# FIRSTPRINT.net
KiCad netlist of a schematic drawn in EAGLE
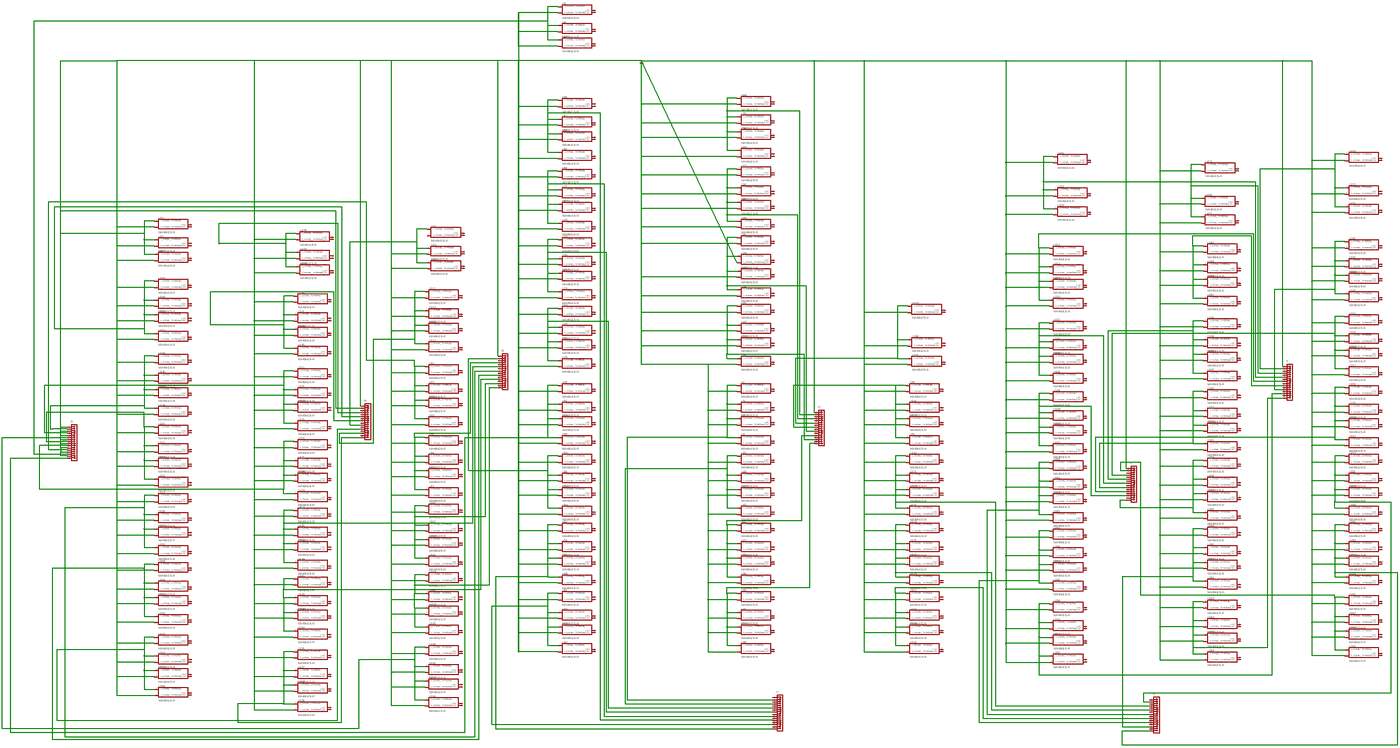
[diagram p0: schematic, sheet 1, overview]
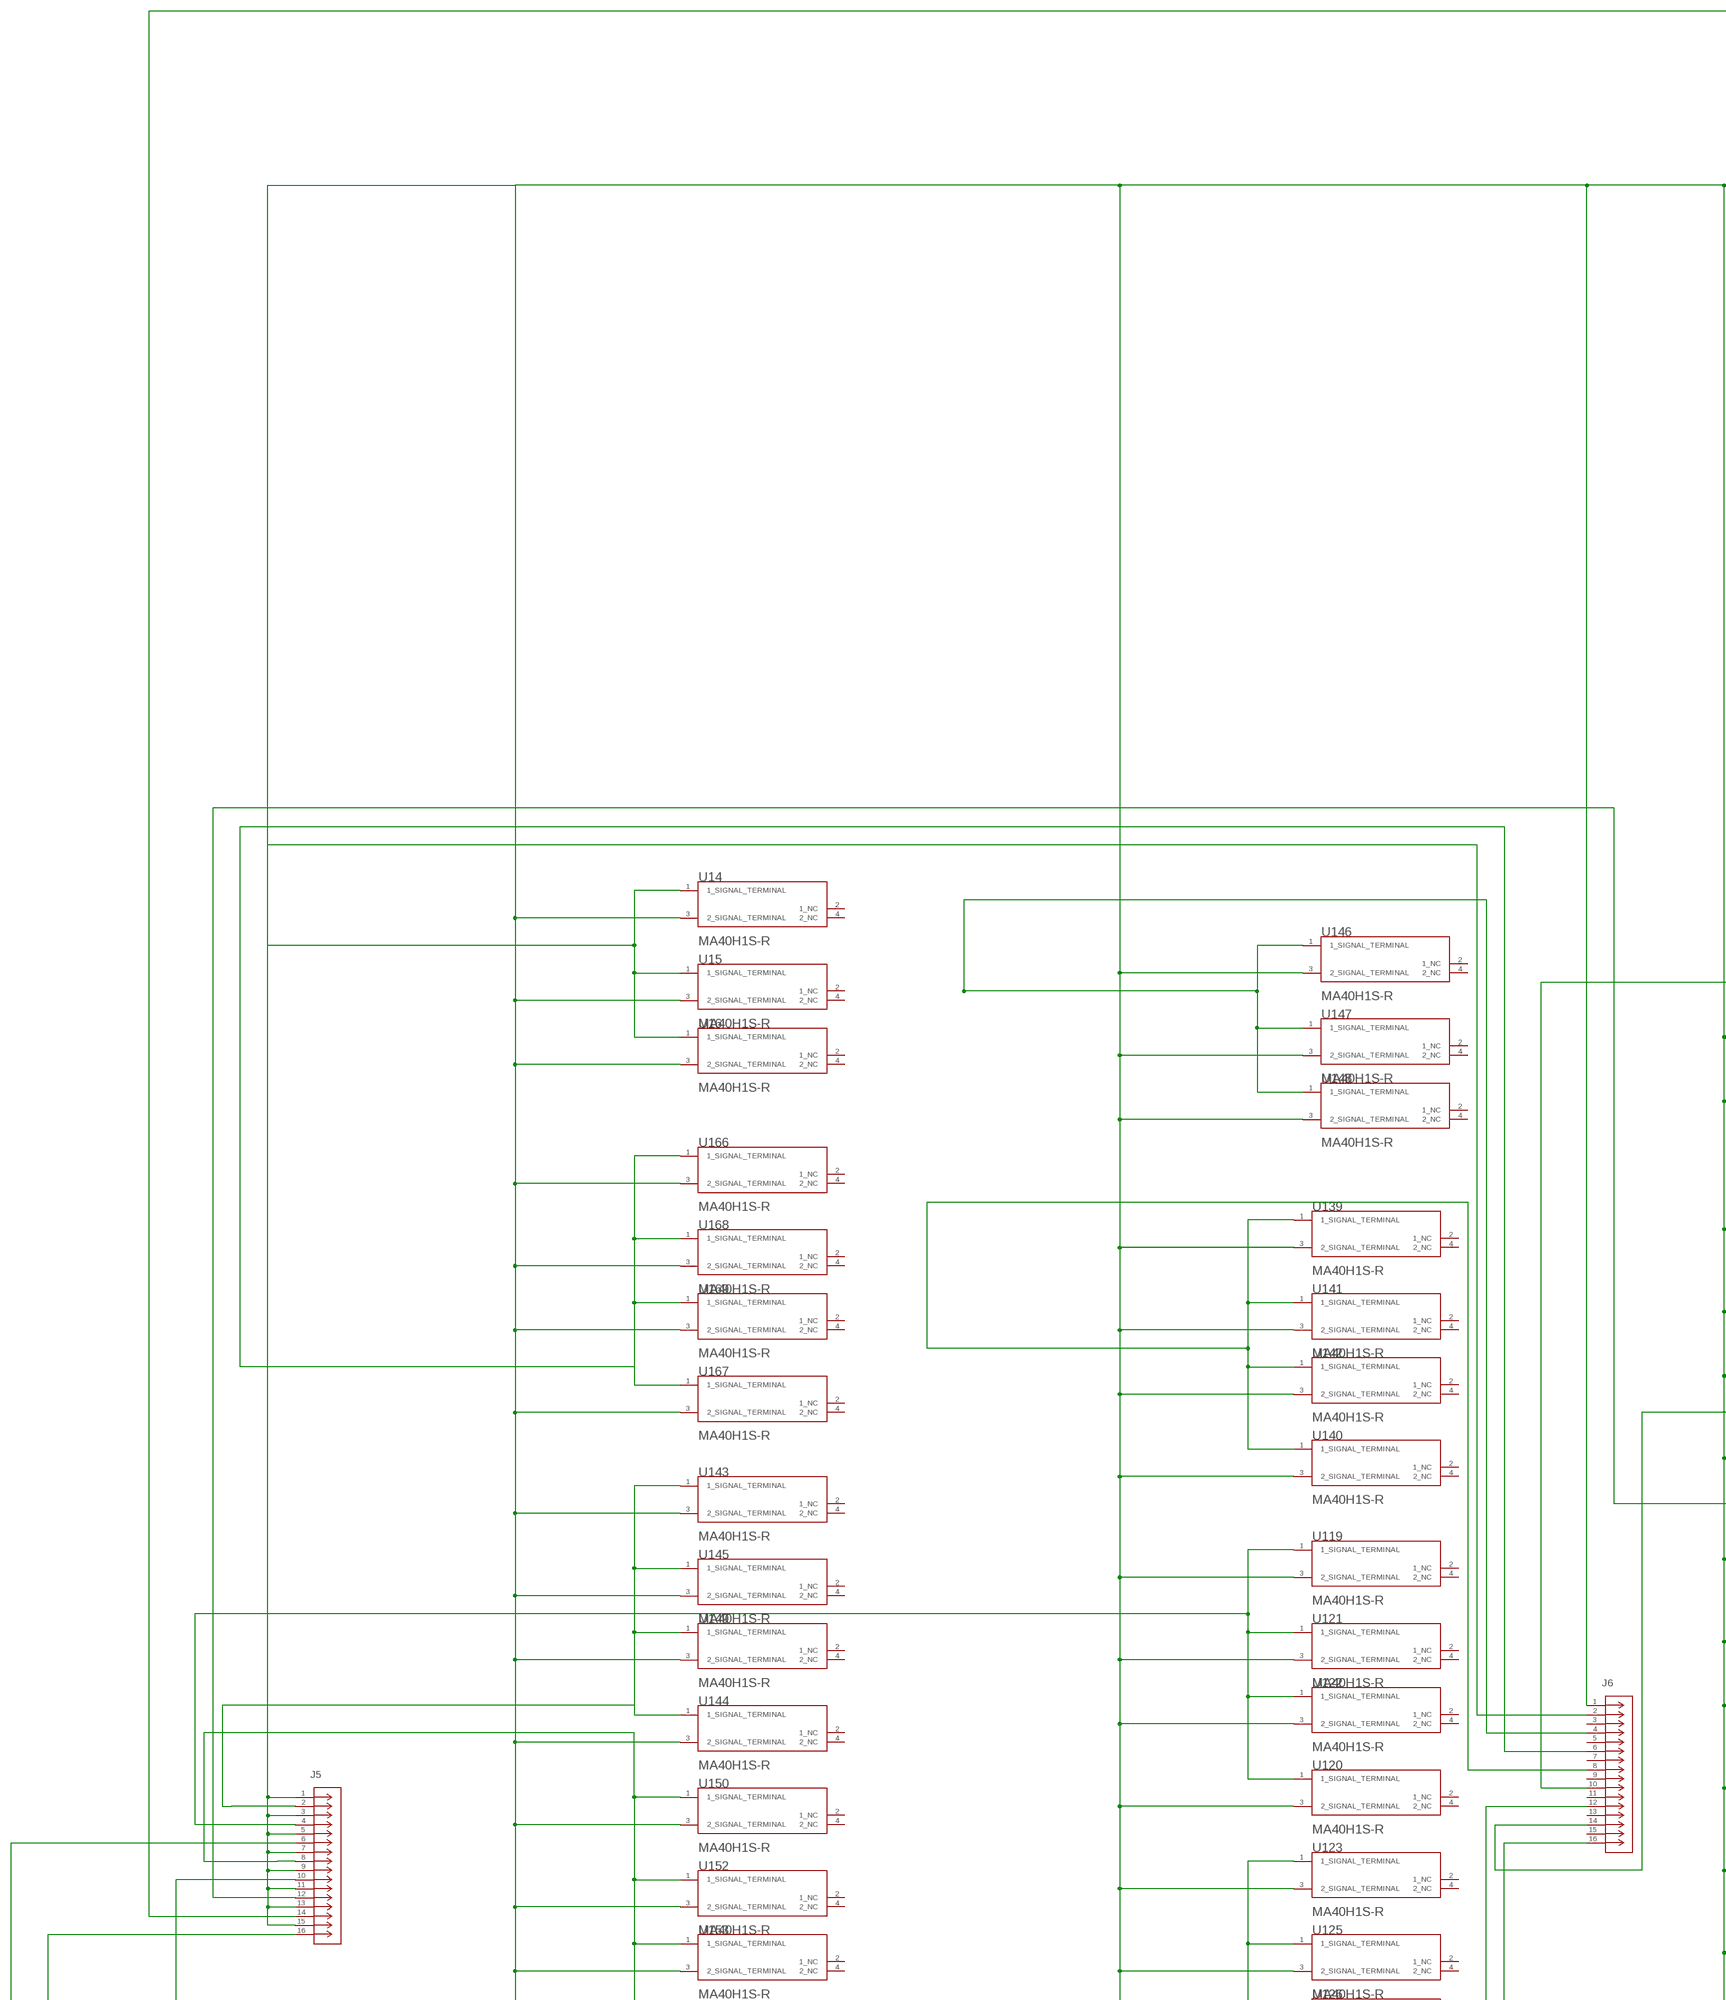
[diagram p1: schematic, sheet 1, part 1 of 8]
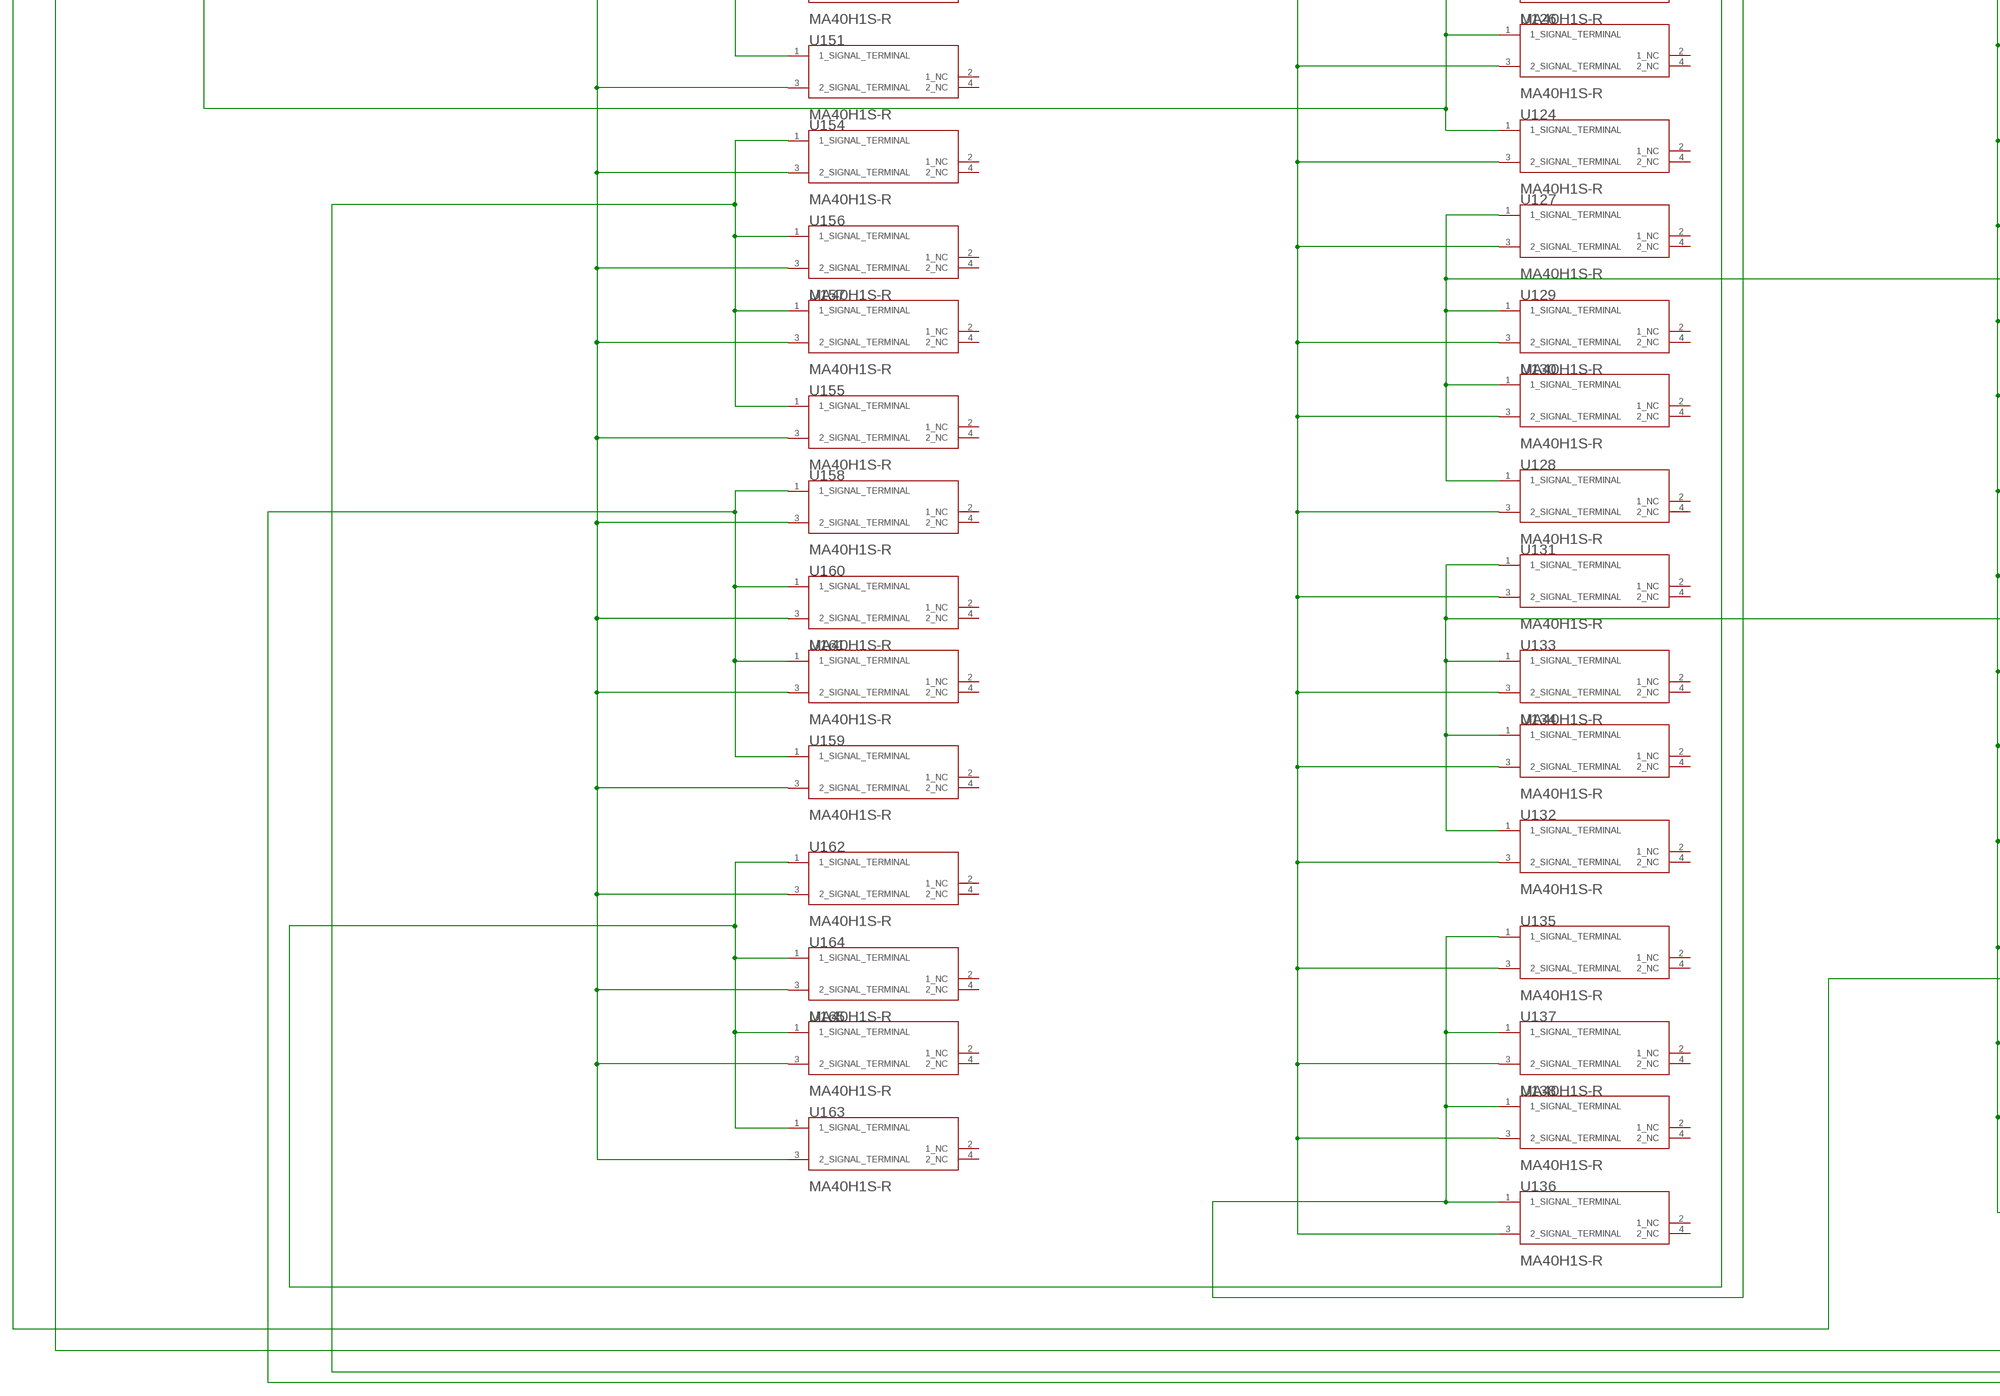
[diagram p2: schematic, sheet 1, part 2 of 8]
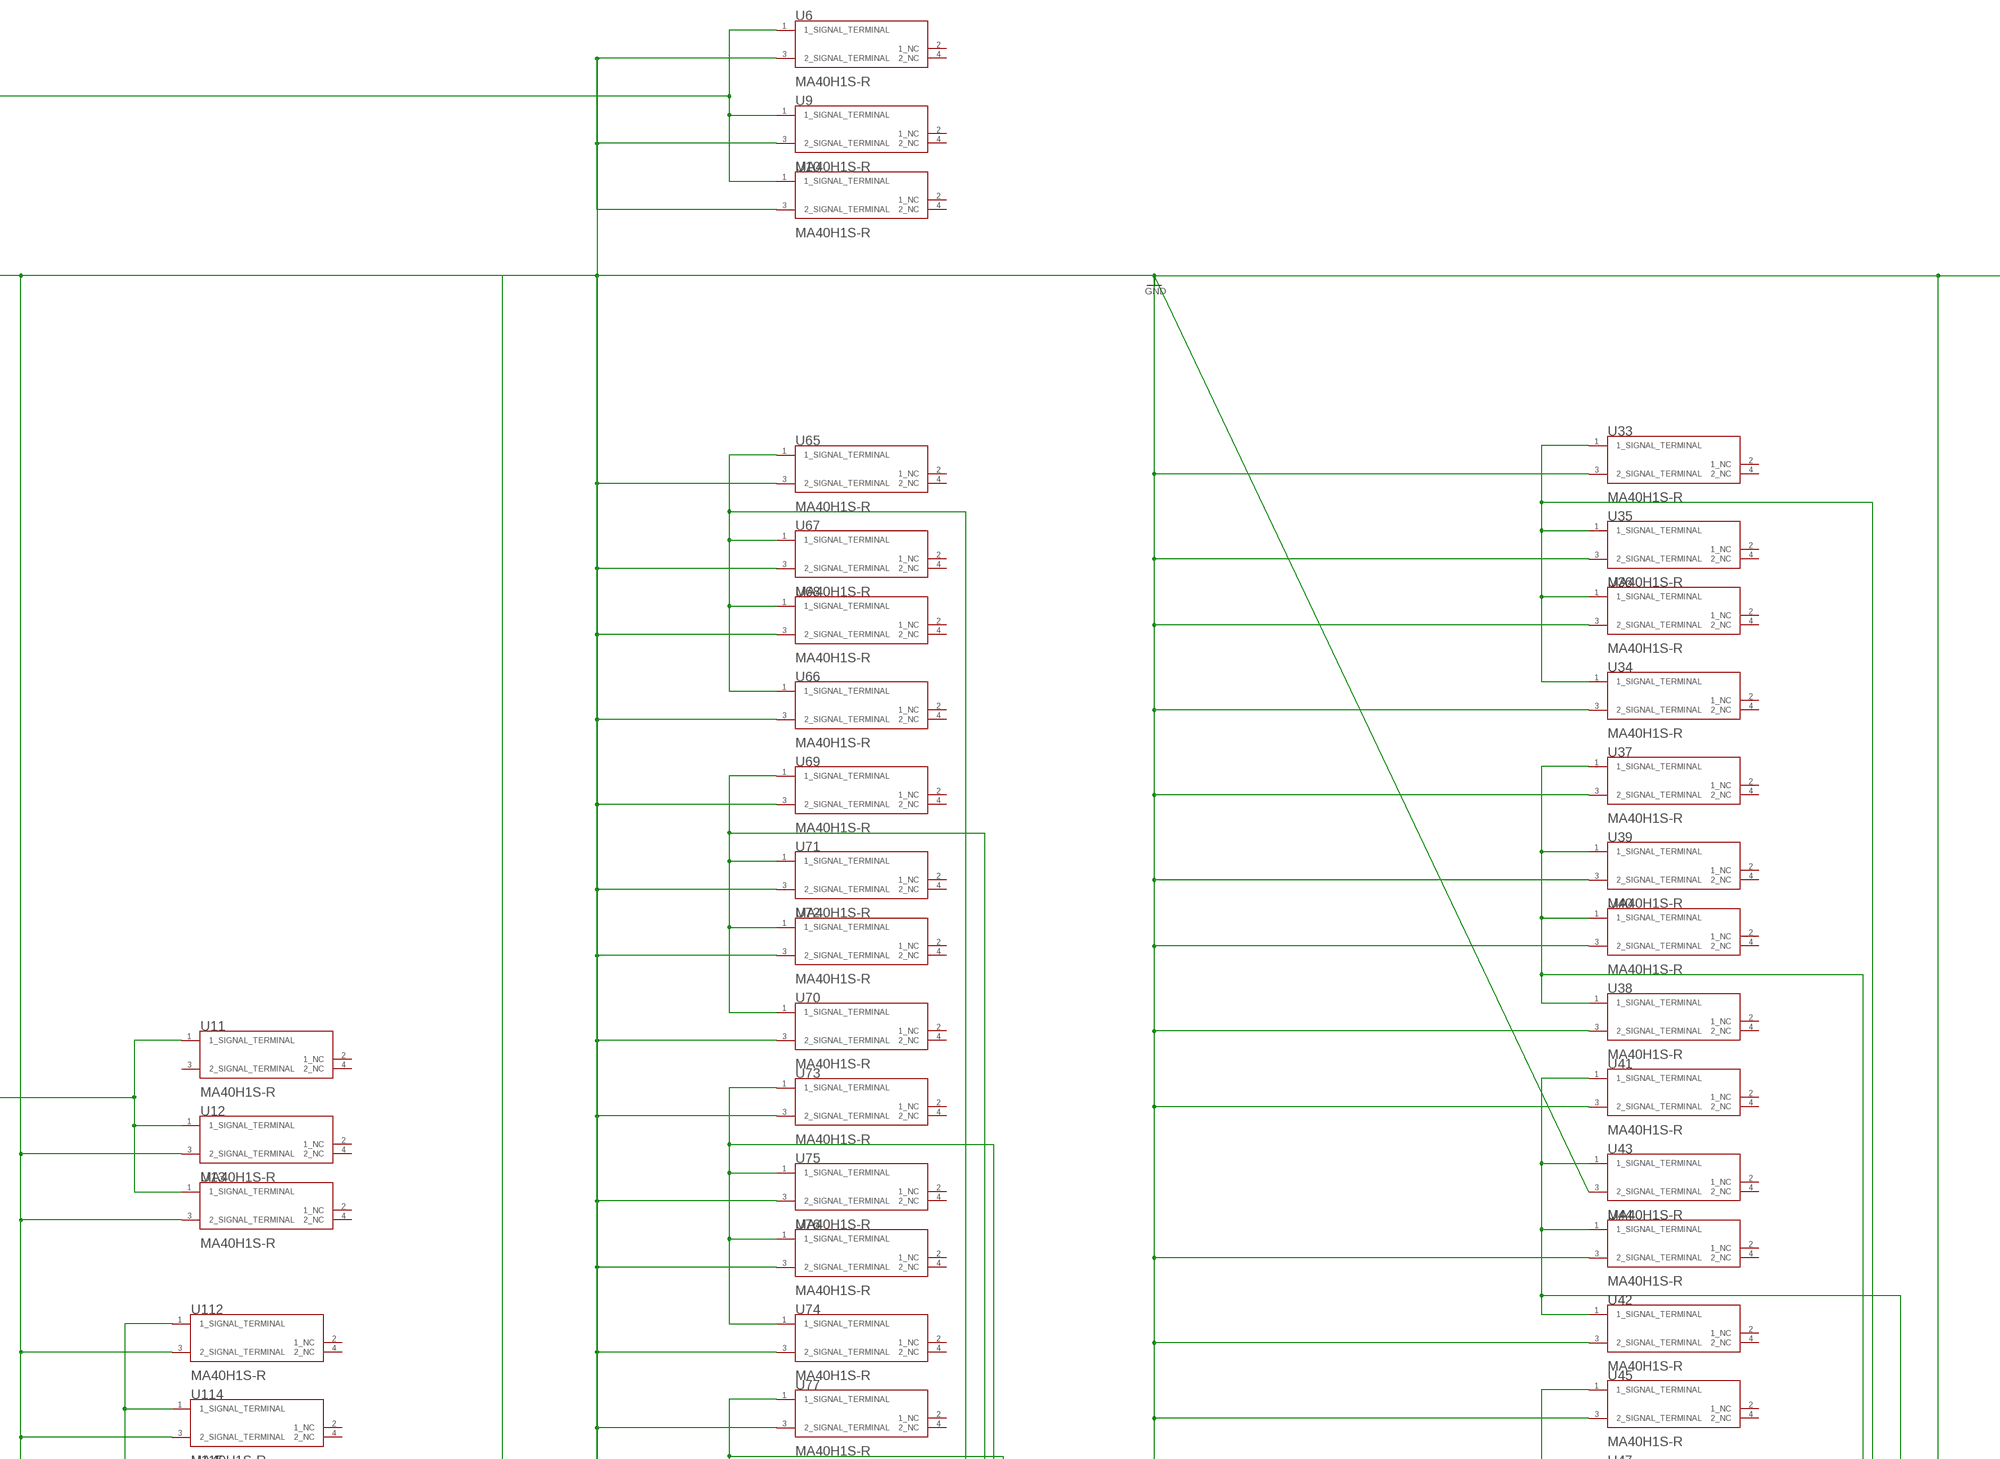
[diagram p3: schematic, sheet 1, part 3 of 8]
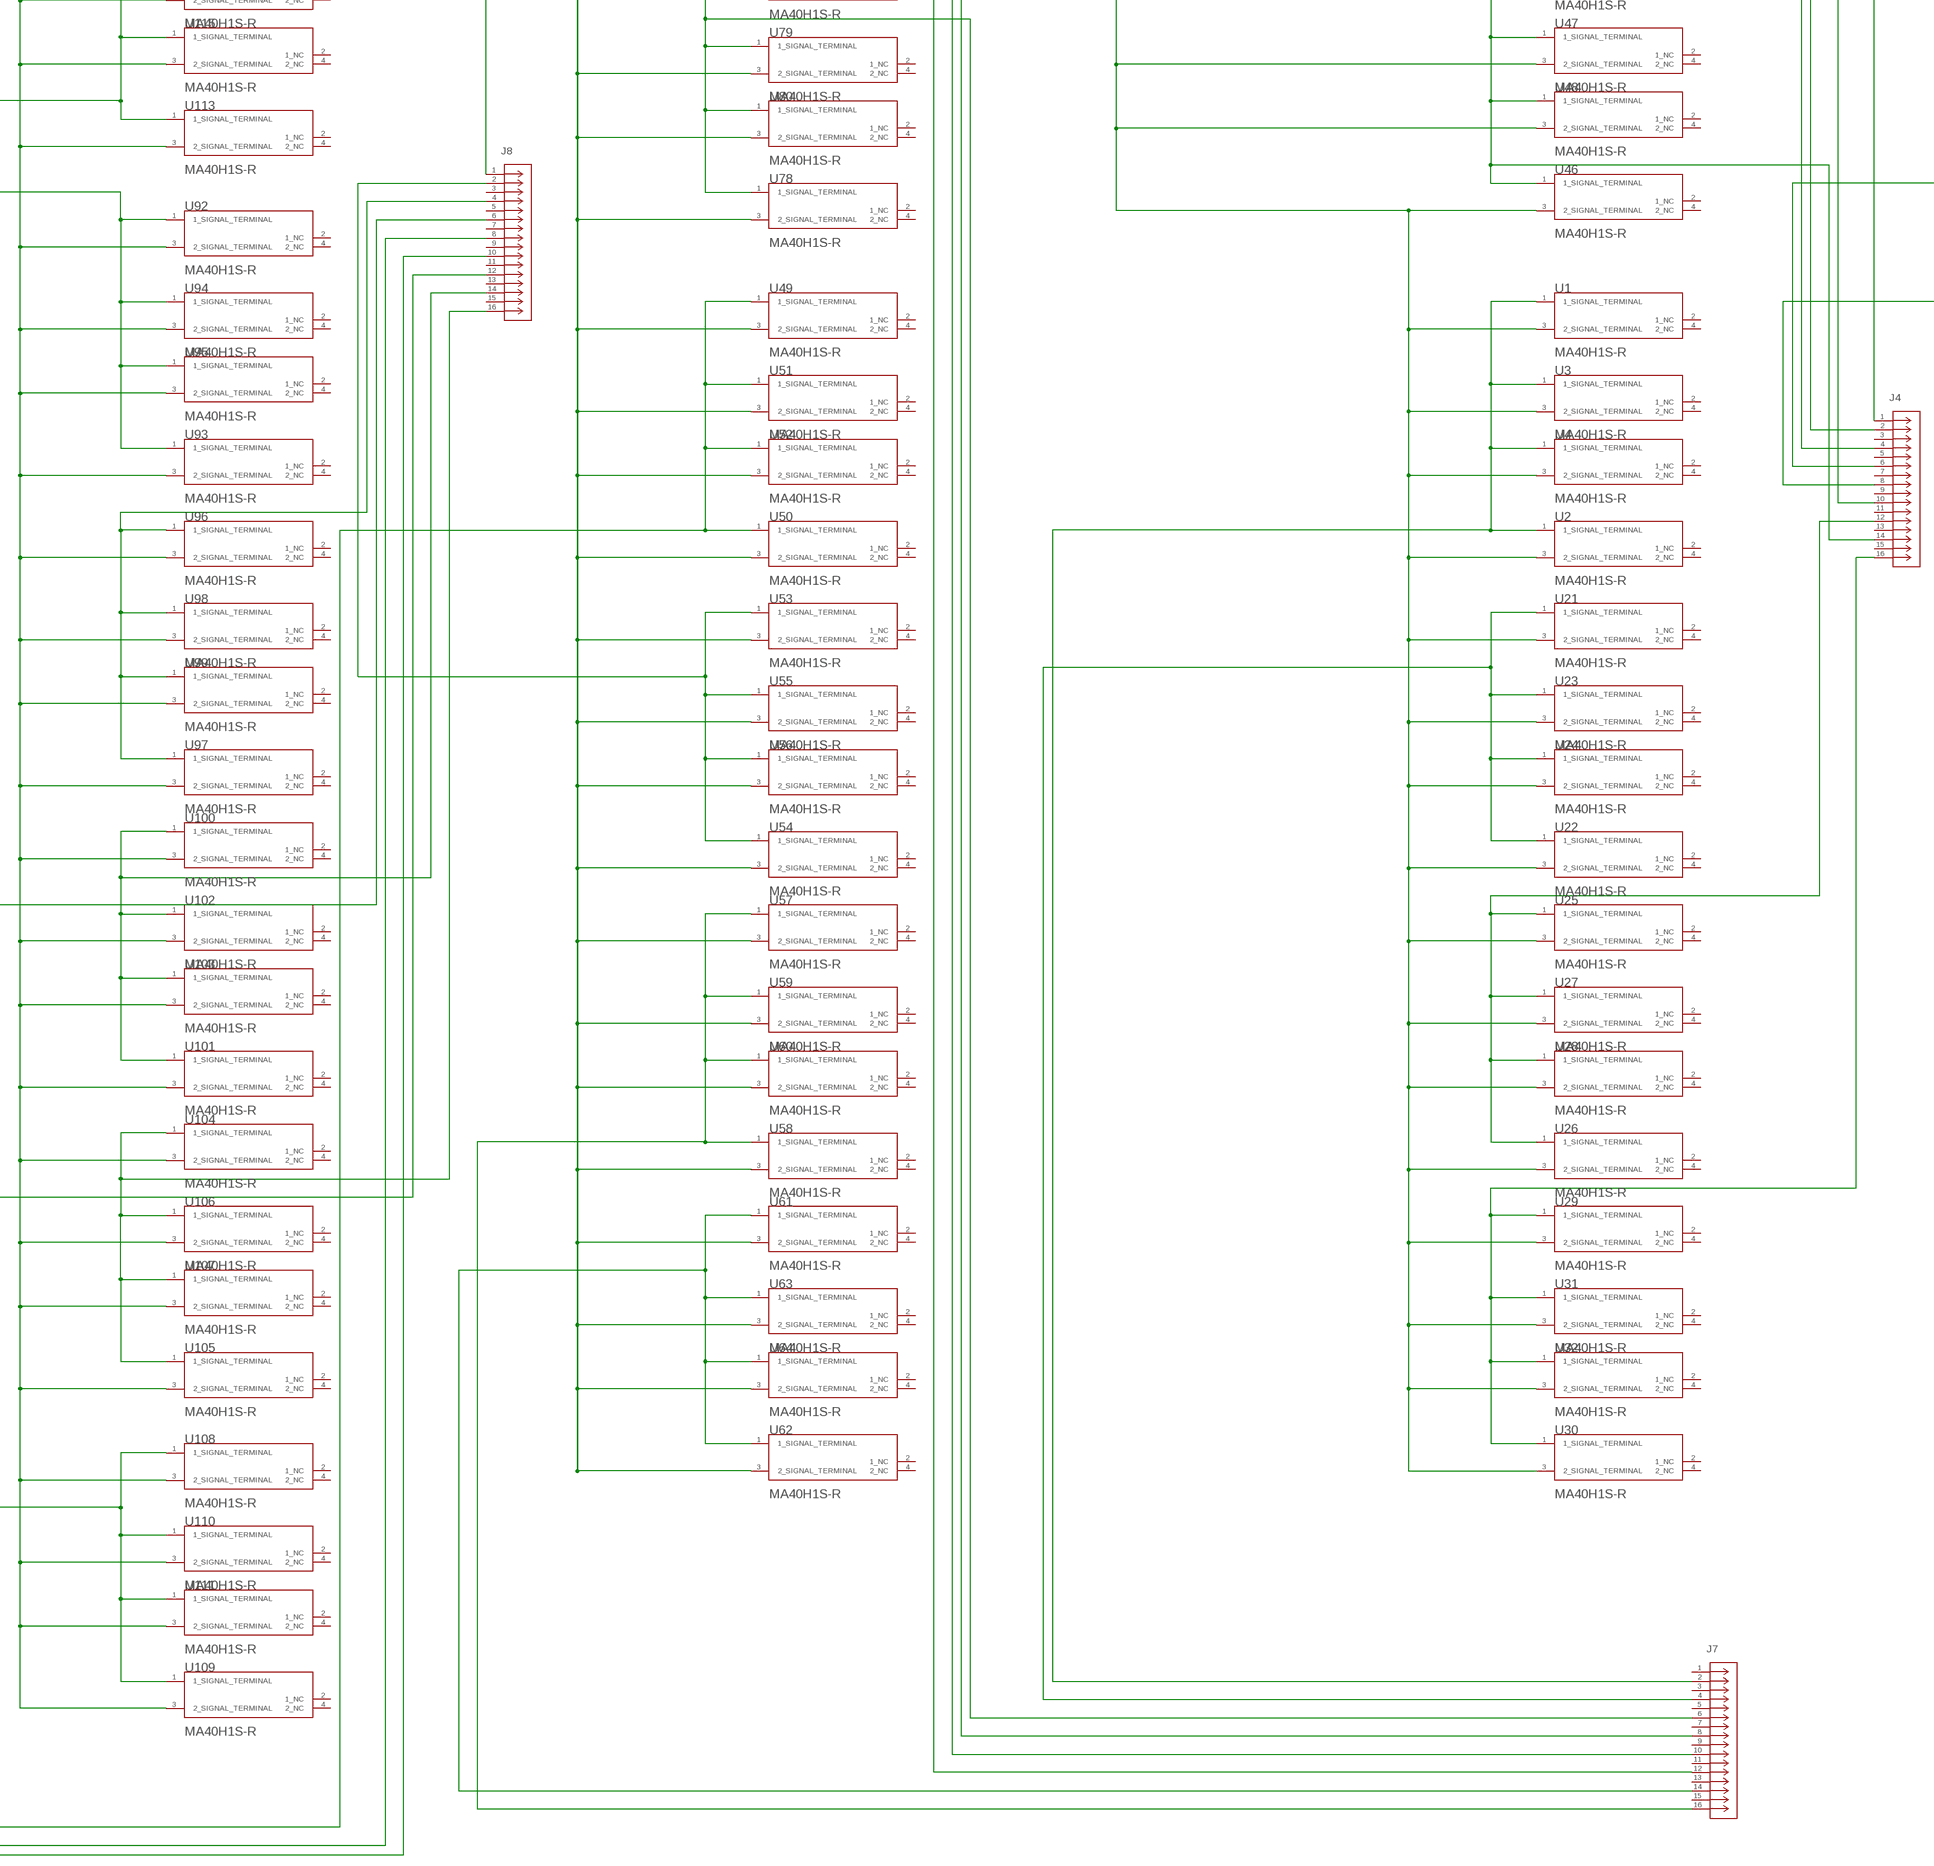
[diagram p4: schematic, sheet 1, part 4 of 8]
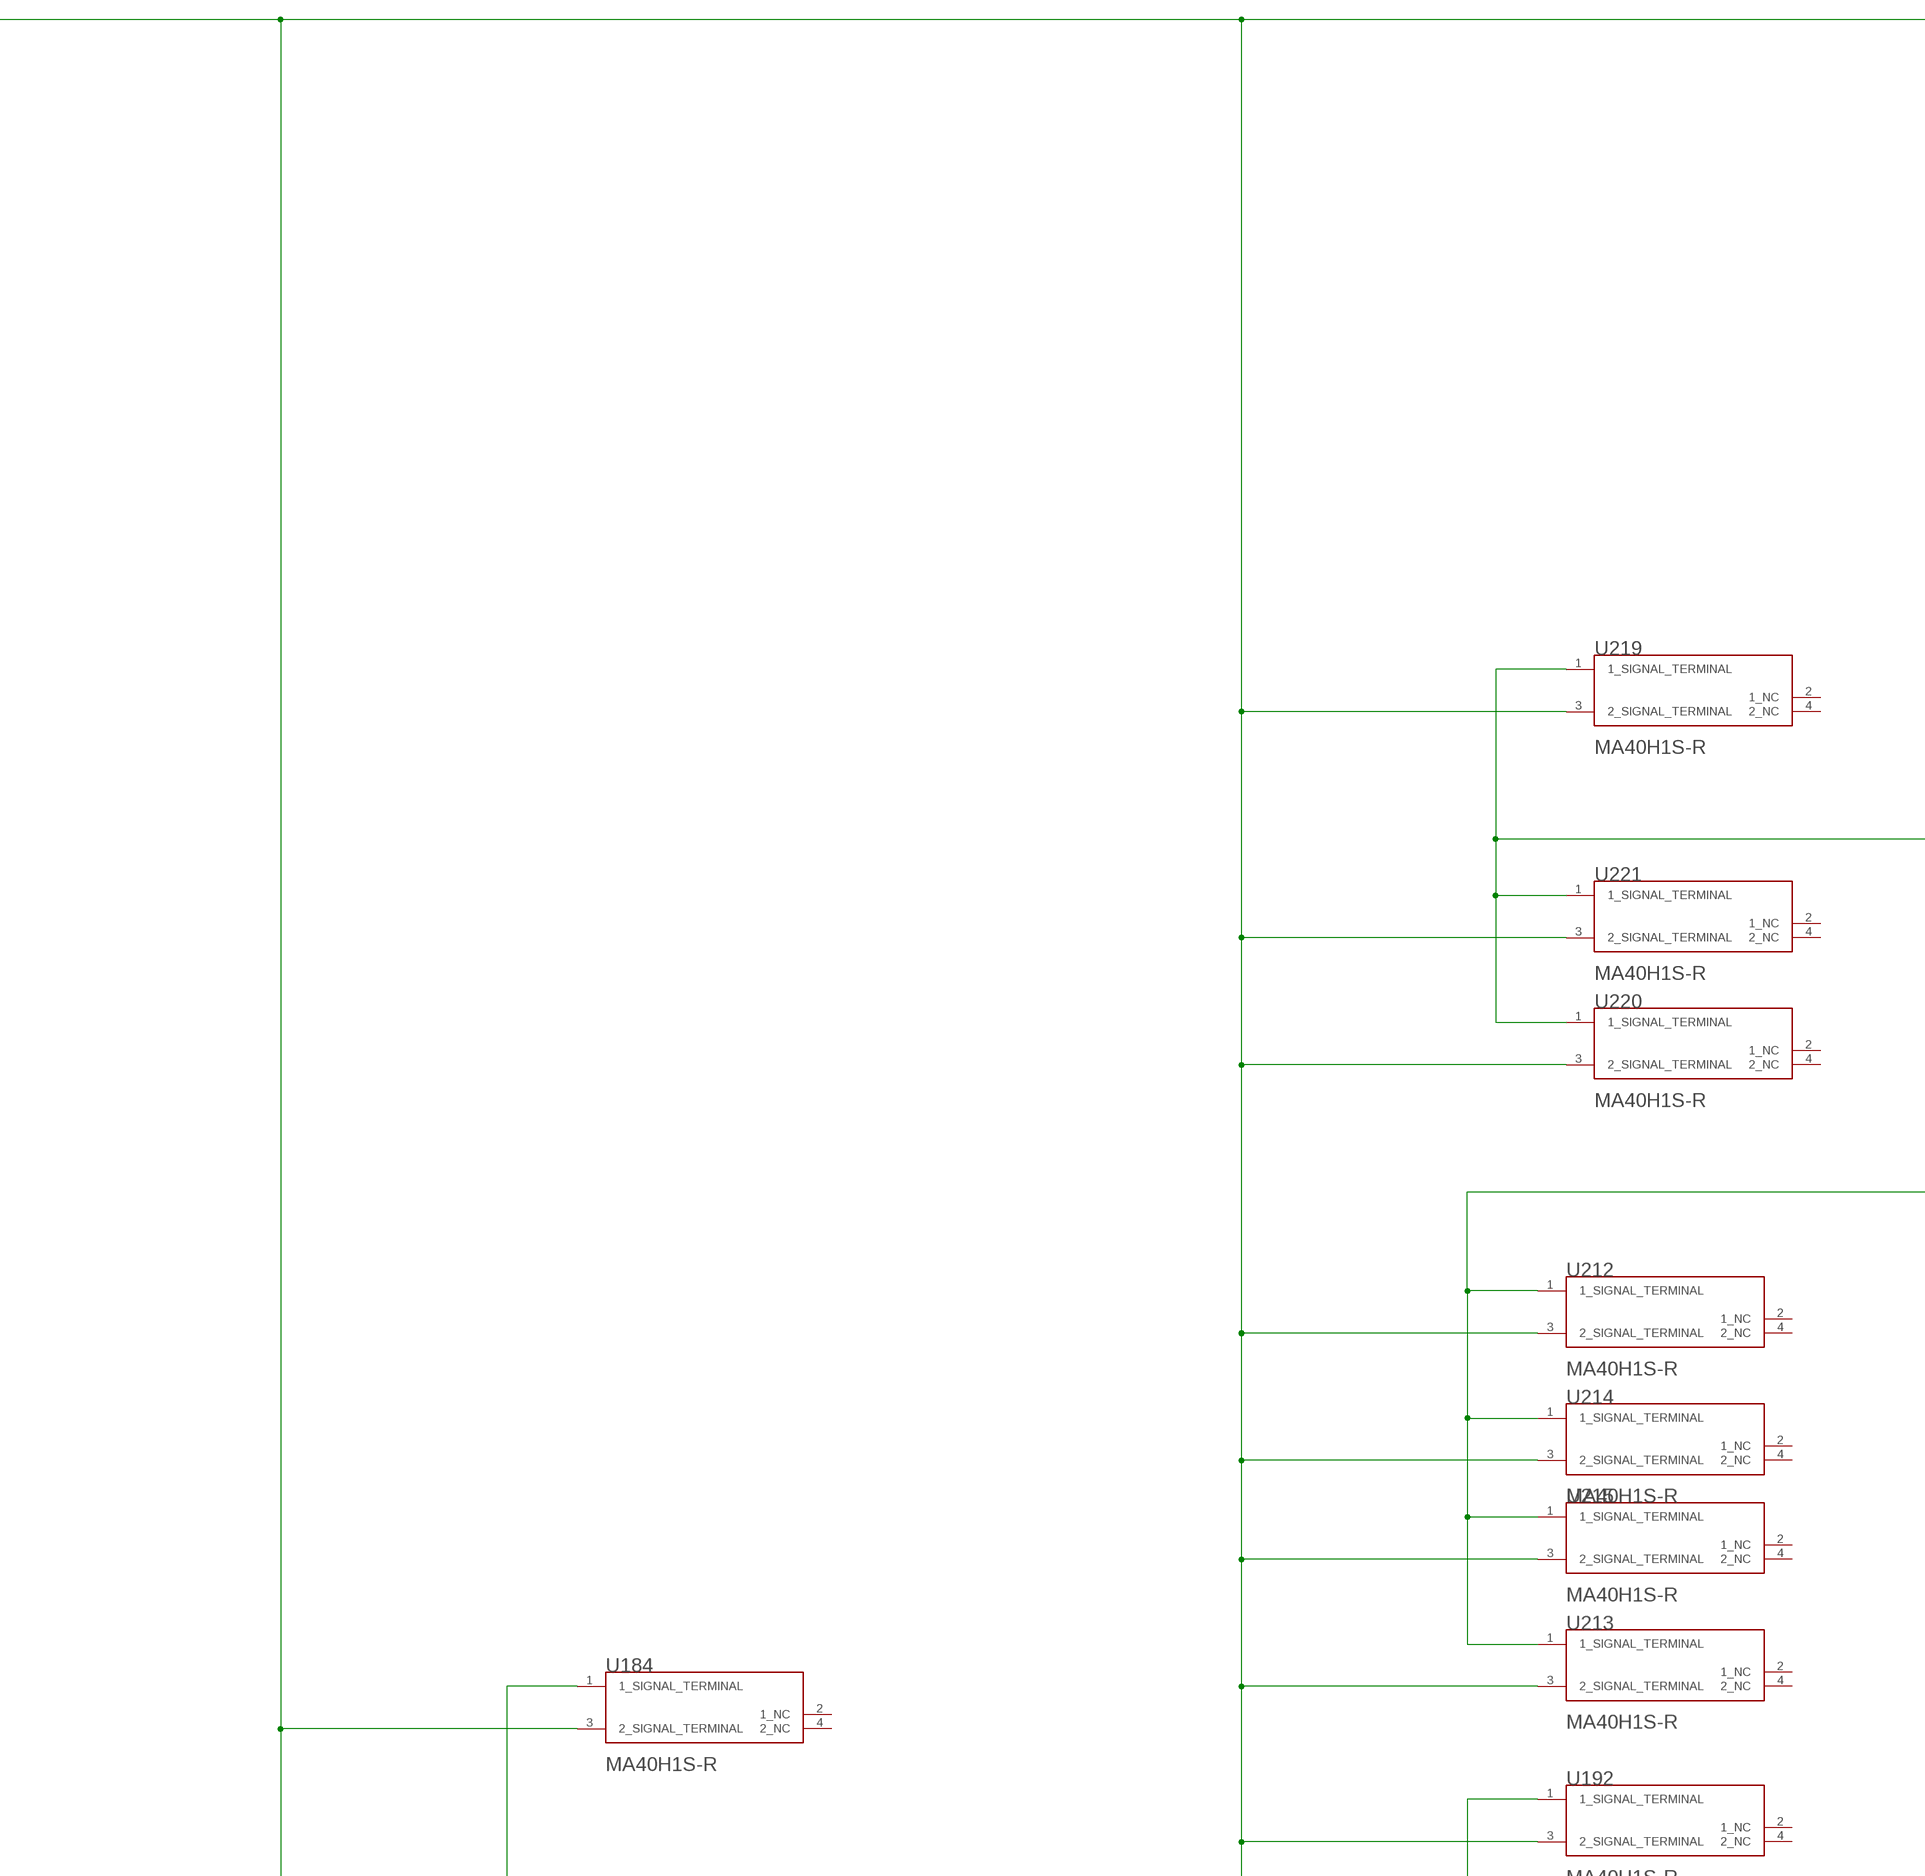
[diagram p5: schematic, sheet 1, part 5 of 8]
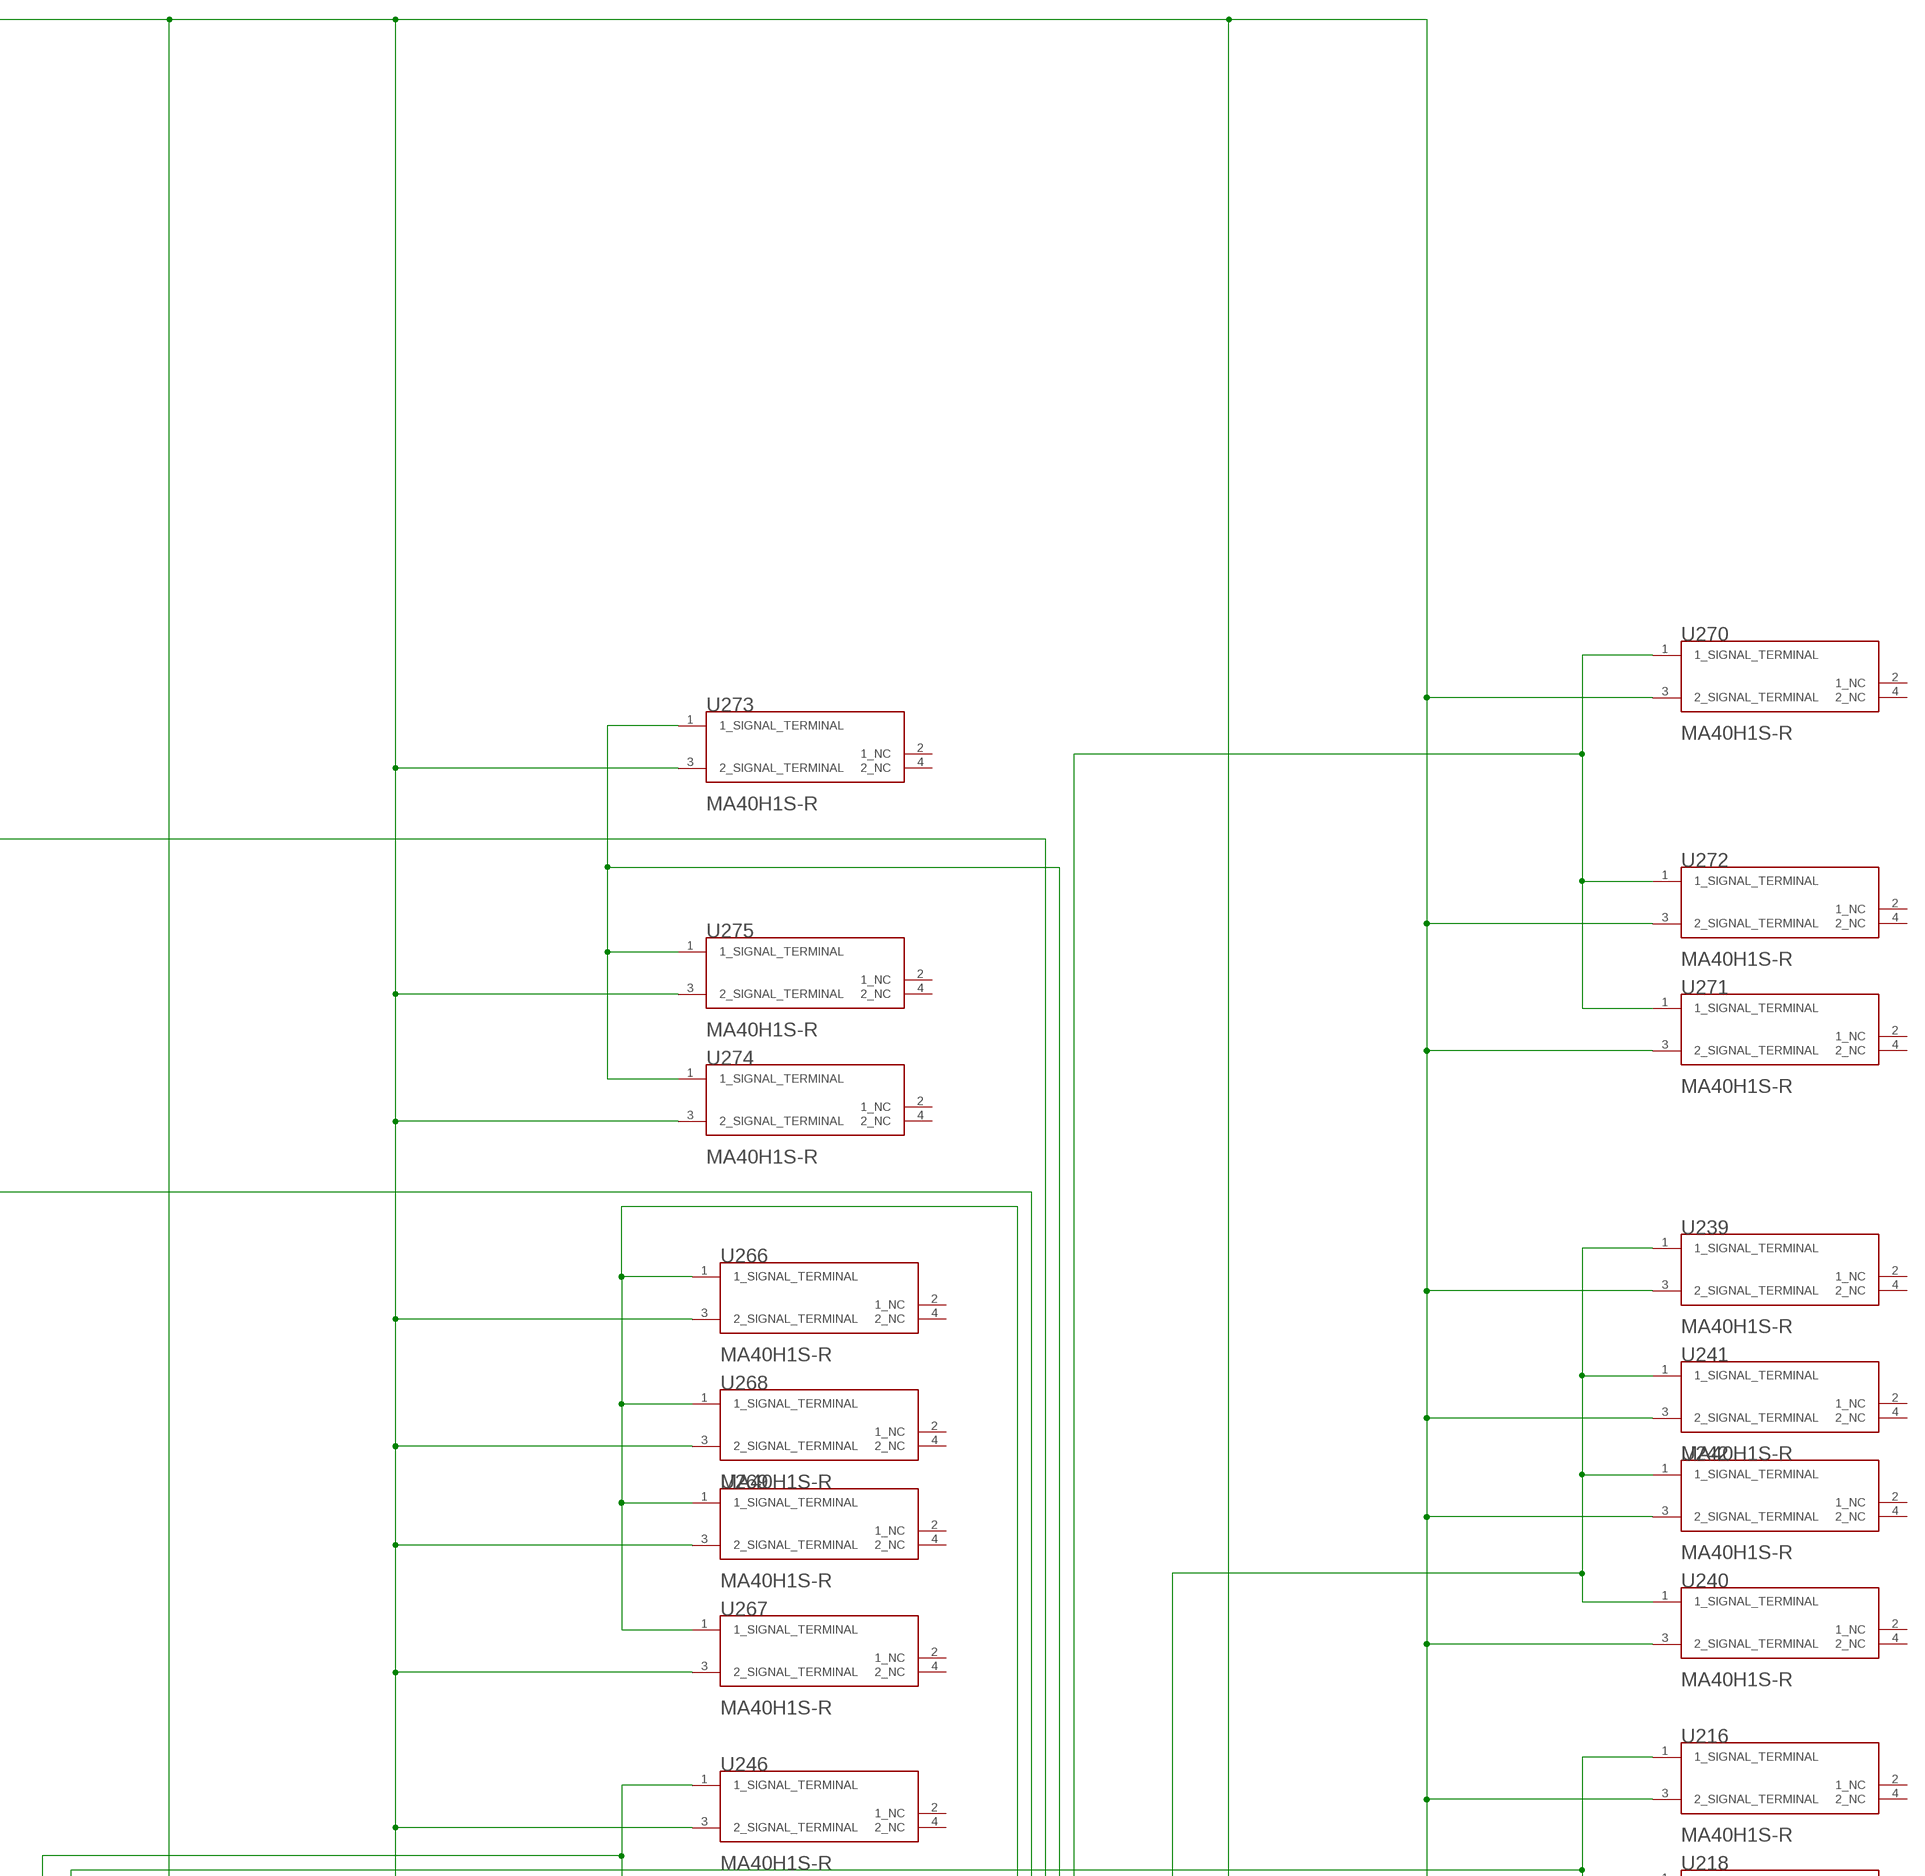
[diagram p6: schematic, sheet 1, part 6 of 8]
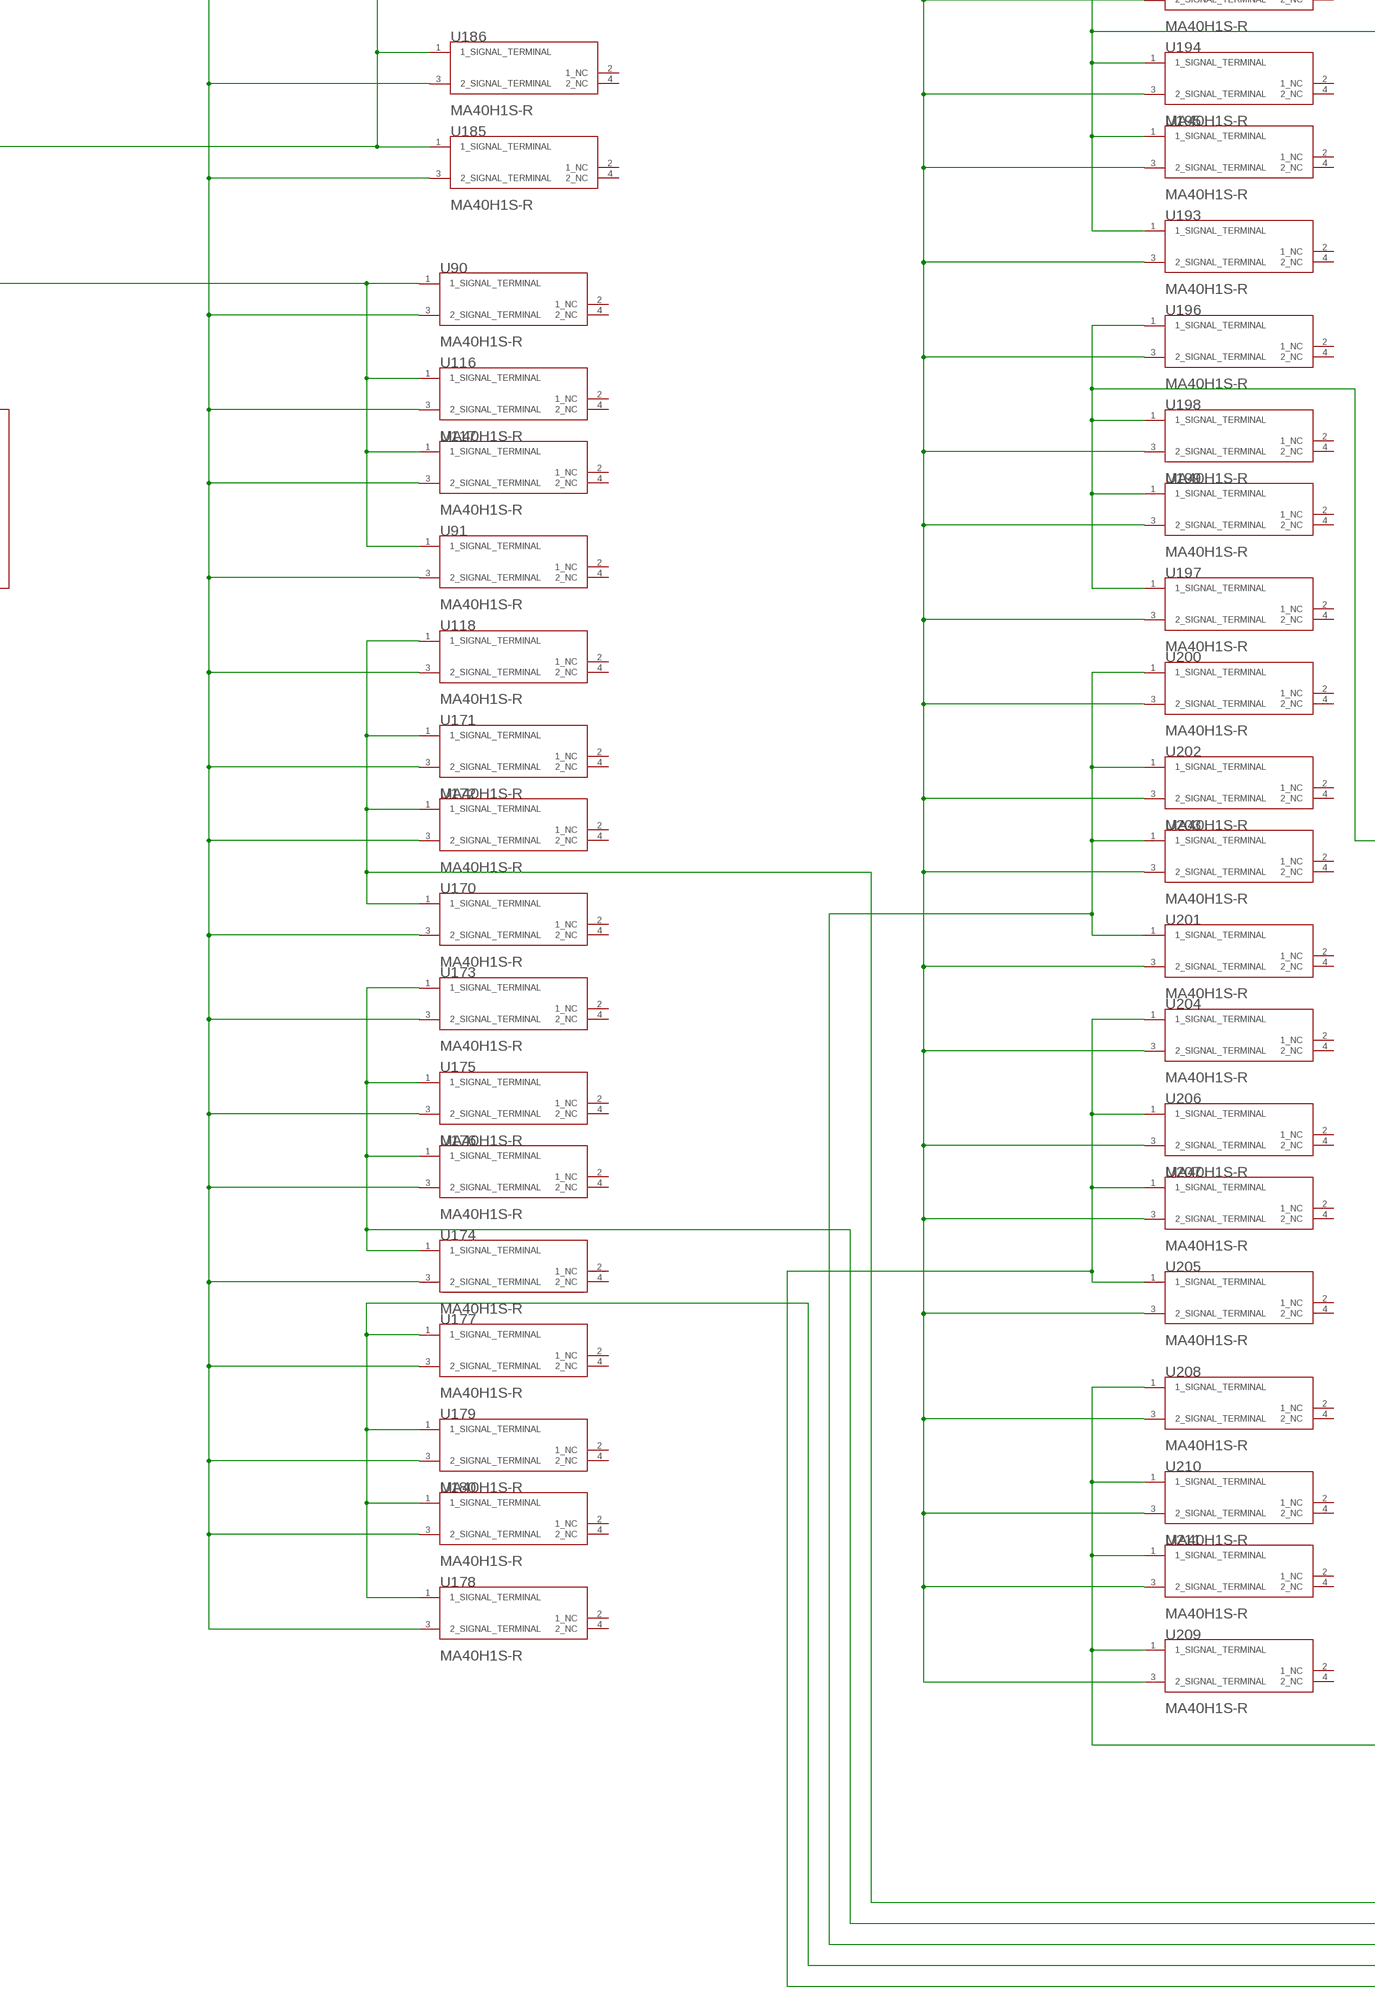
[diagram p7: schematic, sheet 1, part 7 of 8]
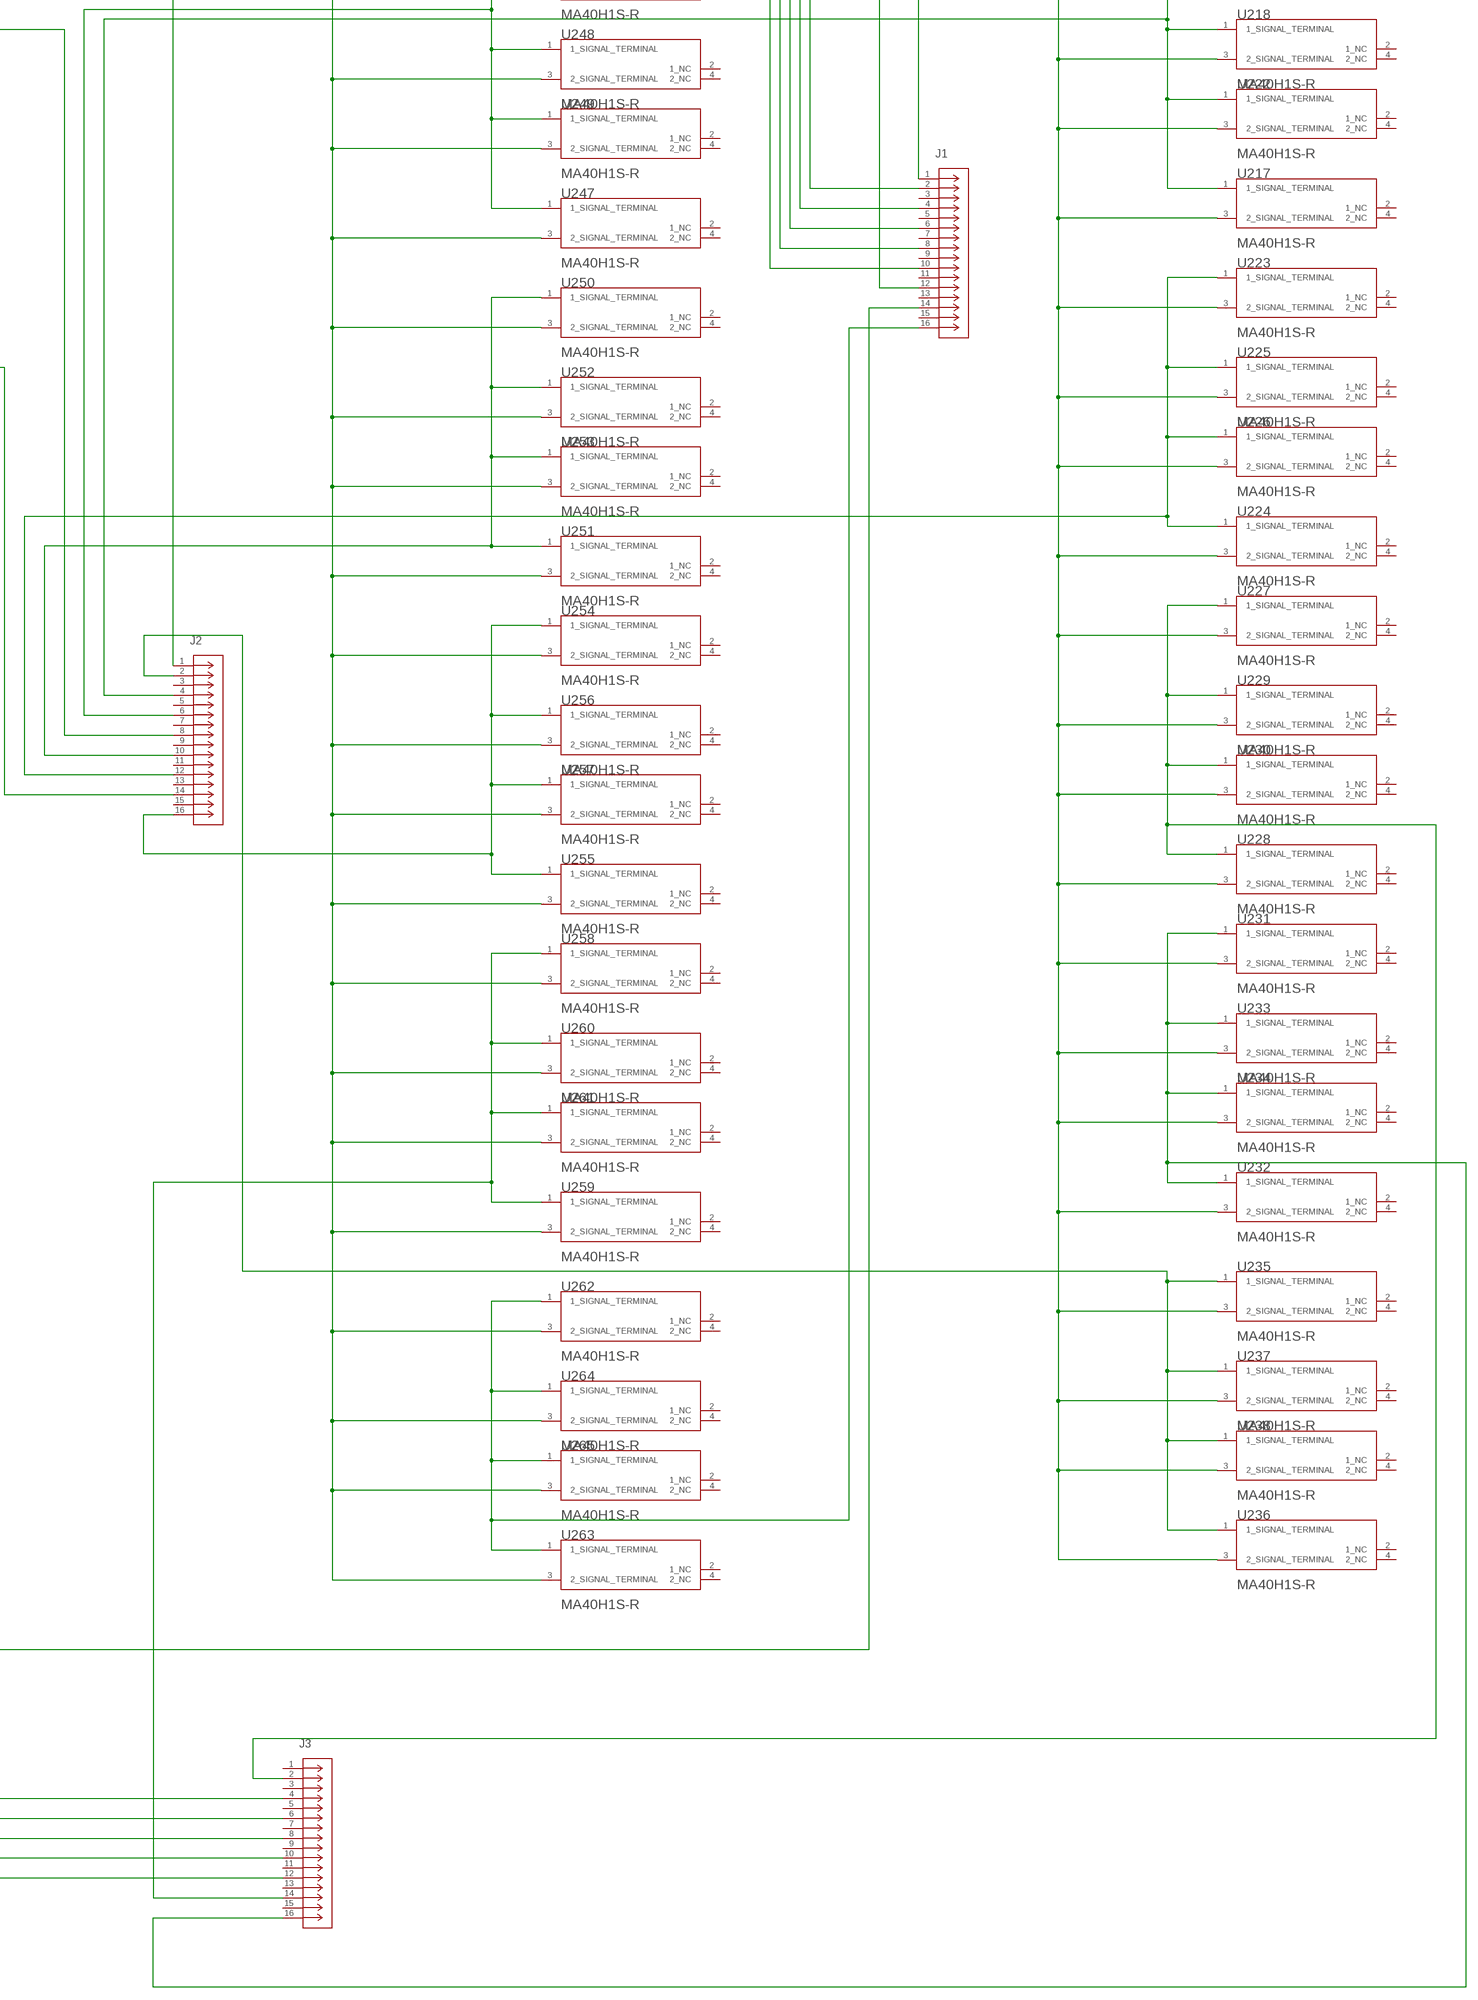
[diagram p8: schematic, sheet 1, part 8 of 8]

(export (version "E")
  (design (tool "Eeschema 10.0.6"))
  (components
    (comp (ref "J1")
      (value "70246-1201")
      (footprint "eagle-import:CONN_70246-1201_MOL")
      (fields (field (name "COPYRIGHT") "Copyright (C) 2018 Accelerated Designs. All rights reserved"))
      (libsource (lib "eagle-import") (part "70246-1201"))
    )
    (comp (ref "J2")
      (value "70246-1201")
      (footprint "eagle-import:CONN_70246-1201_MOL")
      (fields (field (name "COPYRIGHT") "Copyright (C) 2018 Accelerated Designs. All rights reserved"))
      (libsource (lib "eagle-import") (part "70246-1201"))
    )
    (comp (ref "J3")
      (value "70246-1201")
      (footprint "eagle-import:CONN_70246-1201_MOL")
      (fields (field (name "COPYRIGHT") "Copyright (C) 2018 Accelerated Designs. All rights reserved"))
      (libsource (lib "eagle-import") (part "70246-1201"))
    )
    (comp (ref "J4")
      (value "70246-1201")
      (footprint "eagle-import:CONN_70246-1201_MOL")
      (fields (field (name "COPYRIGHT") "Copyright (C) 2018 Accelerated Designs. All rights reserved"))
      (libsource (lib "eagle-import") (part "70246-1201"))
    )
    (comp (ref "J5")
      (value "70246-1201")
      (footprint "eagle-import:CONN_70246-1201_MOL")
      (fields (field (name "COPYRIGHT") "Copyright (C) 2018 Accelerated Designs. All rights reserved"))
      (libsource (lib "eagle-import") (part "70246-1201"))
    )
    (comp (ref "J6")
      (value "70246-1201")
      (footprint "eagle-import:CONN_70246-1201_MOL")
      (fields (field (name "COPYRIGHT") "Copyright (C) 2018 Accelerated Designs. All rights reserved"))
      (libsource (lib "eagle-import") (part "70246-1201"))
    )
    (comp (ref "J7")
      (value "70246-1201")
      (footprint "eagle-import:CONN_70246-1201_MOL")
      (fields (field (name "COPYRIGHT") "Copyright (C) 2018 Accelerated Designs. All rights reserved"))
      (libsource (lib "eagle-import") (part "70246-1201"))
    )
    (comp (ref "J8")
      (value "70246-1201")
      (footprint "eagle-import:CONN_70246-1201_MOL")
      (fields (field (name "COPYRIGHT") "Copyright (C) 2018 Accelerated Designs. All rights reserved"))
      (libsource (lib "eagle-import") (part "70246-1201"))
    )
    (comp (ref "U1")
      (value "MURATA_MA40H1S-RMURATA_MA40H1S-R_0_0")
      (footprint "eagle-import:MURATA_MA40H1S-R_0")
      (fields
        (field (name "DIGIKEY_PART_NUMBER") "490-MA40H1S-RCT-ND")
        (field (name "MF") "Murata")
        (field (name "MOUSER_PART_NUMBER") "81-MA40H1S-R")
      )
      (libsource (lib "eagle-import") (part "MURATA_MA40H1S-RMURATA_MA40H1S-R_0_0"))
    )
    (comp (ref "U2")
      (value "MURATA_MA40H1S-RMURATA_MA40H1S-R_0_0")
      (footprint "eagle-import:MURATA_MA40H1S-R_0")
      (fields
        (field (name "DIGIKEY_PART_NUMBER") "490-MA40H1S-RCT-ND")
        (field (name "MF") "Murata")
        (field (name "MOUSER_PART_NUMBER") "81-MA40H1S-R")
      )
      (libsource (lib "eagle-import") (part "MURATA_MA40H1S-RMURATA_MA40H1S-R_0_0"))
    )
    (comp (ref "U3")
      (value "MURATA_MA40H1S-RMURATA_MA40H1S-R_0_0")
      (footprint "eagle-import:MURATA_MA40H1S-R_0")
      (fields
        (field (name "DIGIKEY_PART_NUMBER") "490-MA40H1S-RCT-ND")
        (field (name "MF") "Murata")
        (field (name "MOUSER_PART_NUMBER") "81-MA40H1S-R")
      )
      (libsource (lib "eagle-import") (part "MURATA_MA40H1S-RMURATA_MA40H1S-R_0_0"))
    )
    (comp (ref "U4")
      (value "MURATA_MA40H1S-RMURATA_MA40H1S-R_0_0")
      (footprint "eagle-import:MURATA_MA40H1S-R_0")
      (fields
        (field (name "DIGIKEY_PART_NUMBER") "490-MA40H1S-RCT-ND")
        (field (name "MF") "Murata")
        (field (name "MOUSER_PART_NUMBER") "81-MA40H1S-R")
      )
      (libsource (lib "eagle-import") (part "MURATA_MA40H1S-RMURATA_MA40H1S-R_0_0"))
    )
    (comp (ref "U6")
      (value "MURATA_MA40H1S-RMURATA_MA40H1S-R_0_0")
      (footprint "eagle-import:MURATA_MA40H1S-R_0")
      (fields
        (field (name "DIGIKEY_PART_NUMBER") "490-MA40H1S-RCT-ND")
        (field (name "MF") "Murata")
        (field (name "MOUSER_PART_NUMBER") "81-MA40H1S-R")
      )
      (libsource (lib "eagle-import") (part "MURATA_MA40H1S-RMURATA_MA40H1S-R_0_0"))
    )
    (comp (ref "U9")
      (value "MURATA_MA40H1S-RMURATA_MA40H1S-R_0_0")
      (footprint "eagle-import:MURATA_MA40H1S-R_0")
      (fields
        (field (name "DIGIKEY_PART_NUMBER") "490-MA40H1S-RCT-ND")
        (field (name "MF") "Murata")
        (field (name "MOUSER_PART_NUMBER") "81-MA40H1S-R")
      )
      (libsource (lib "eagle-import") (part "MURATA_MA40H1S-RMURATA_MA40H1S-R_0_0"))
    )
    (comp (ref "U10")
      (value "MURATA_MA40H1S-RMURATA_MA40H1S-R_0_0")
      (footprint "eagle-import:MURATA_MA40H1S-R_0")
      (fields
        (field (name "DIGIKEY_PART_NUMBER") "490-MA40H1S-RCT-ND")
        (field (name "MF") "Murata")
        (field (name "MOUSER_PART_NUMBER") "81-MA40H1S-R")
      )
      (libsource (lib "eagle-import") (part "MURATA_MA40H1S-RMURATA_MA40H1S-R_0_0"))
    )
    (comp (ref "U11")
      (value "MURATA_MA40H1S-RMURATA_MA40H1S-R_0_0")
      (footprint "eagle-import:MURATA_MA40H1S-R_0")
      (fields
        (field (name "DIGIKEY_PART_NUMBER") "490-MA40H1S-RCT-ND")
        (field (name "MF") "Murata")
        (field (name "MOUSER_PART_NUMBER") "81-MA40H1S-R")
      )
      (libsource (lib "eagle-import") (part "MURATA_MA40H1S-RMURATA_MA40H1S-R_0_0"))
    )
    (comp (ref "U12")
      (value "MURATA_MA40H1S-RMURATA_MA40H1S-R_0_0")
      (footprint "eagle-import:MURATA_MA40H1S-R_0")
      (fields
        (field (name "DIGIKEY_PART_NUMBER") "490-MA40H1S-RCT-ND")
        (field (name "MF") "Murata")
        (field (name "MOUSER_PART_NUMBER") "81-MA40H1S-R")
      )
      (libsource (lib "eagle-import") (part "MURATA_MA40H1S-RMURATA_MA40H1S-R_0_0"))
    )
    (comp (ref "U13")
      (value "MURATA_MA40H1S-RMURATA_MA40H1S-R_0_0")
      (footprint "eagle-import:MURATA_MA40H1S-R_0")
      (fields
        (field (name "DIGIKEY_PART_NUMBER") "490-MA40H1S-RCT-ND")
        (field (name "MF") "Murata")
        (field (name "MOUSER_PART_NUMBER") "81-MA40H1S-R")
      )
      (libsource (lib "eagle-import") (part "MURATA_MA40H1S-RMURATA_MA40H1S-R_0_0"))
    )
    (comp (ref "U14")
      (value "MURATA_MA40H1S-RMURATA_MA40H1S-R_0_0")
      (footprint "eagle-import:MURATA_MA40H1S-R_0")
      (fields
        (field (name "DIGIKEY_PART_NUMBER") "490-MA40H1S-RCT-ND")
        (field (name "MF") "Murata")
        (field (name "MOUSER_PART_NUMBER") "81-MA40H1S-R")
      )
      (libsource (lib "eagle-import") (part "MURATA_MA40H1S-RMURATA_MA40H1S-R_0_0"))
    )
    (comp (ref "U15")
      (value "MURATA_MA40H1S-RMURATA_MA40H1S-R_0_0")
      (footprint "eagle-import:MURATA_MA40H1S-R_0")
      (fields
        (field (name "DIGIKEY_PART_NUMBER") "490-MA40H1S-RCT-ND")
        (field (name "MF") "Murata")
        (field (name "MOUSER_PART_NUMBER") "81-MA40H1S-R")
      )
      (libsource (lib "eagle-import") (part "MURATA_MA40H1S-RMURATA_MA40H1S-R_0_0"))
    )
    (comp (ref "U16")
      (value "MURATA_MA40H1S-RMURATA_MA40H1S-R_0_0")
      (footprint "eagle-import:MURATA_MA40H1S-R_0")
      (fields
        (field (name "DIGIKEY_PART_NUMBER") "490-MA40H1S-RCT-ND")
        (field (name "MF") "Murata")
        (field (name "MOUSER_PART_NUMBER") "81-MA40H1S-R")
      )
      (libsource (lib "eagle-import") (part "MURATA_MA40H1S-RMURATA_MA40H1S-R_0_0"))
    )
    (comp (ref "U21")
      (value "MURATA_MA40H1S-RMURATA_MA40H1S-R_0_0")
      (footprint "eagle-import:MURATA_MA40H1S-R_0")
      (fields
        (field (name "DIGIKEY_PART_NUMBER") "490-MA40H1S-RCT-ND")
        (field (name "MF") "Murata")
        (field (name "MOUSER_PART_NUMBER") "81-MA40H1S-R")
      )
      (libsource (lib "eagle-import") (part "MURATA_MA40H1S-RMURATA_MA40H1S-R_0_0"))
    )
    (comp (ref "U22")
      (value "MURATA_MA40H1S-RMURATA_MA40H1S-R_0_0")
      (footprint "eagle-import:MURATA_MA40H1S-R_0")
      (fields
        (field (name "DIGIKEY_PART_NUMBER") "490-MA40H1S-RCT-ND")
        (field (name "MF") "Murata")
        (field (name "MOUSER_PART_NUMBER") "81-MA40H1S-R")
      )
      (libsource (lib "eagle-import") (part "MURATA_MA40H1S-RMURATA_MA40H1S-R_0_0"))
    )
    (comp (ref "U23")
      (value "MURATA_MA40H1S-RMURATA_MA40H1S-R_0_0")
      (footprint "eagle-import:MURATA_MA40H1S-R_0")
      (fields
        (field (name "DIGIKEY_PART_NUMBER") "490-MA40H1S-RCT-ND")
        (field (name "MF") "Murata")
        (field (name "MOUSER_PART_NUMBER") "81-MA40H1S-R")
      )
      (libsource (lib "eagle-import") (part "MURATA_MA40H1S-RMURATA_MA40H1S-R_0_0"))
    )
    (comp (ref "U24")
      (value "MURATA_MA40H1S-RMURATA_MA40H1S-R_0_0")
      (footprint "eagle-import:MURATA_MA40H1S-R_0")
      (fields
        (field (name "DIGIKEY_PART_NUMBER") "490-MA40H1S-RCT-ND")
        (field (name "MF") "Murata")
        (field (name "MOUSER_PART_NUMBER") "81-MA40H1S-R")
      )
      (libsource (lib "eagle-import") (part "MURATA_MA40H1S-RMURATA_MA40H1S-R_0_0"))
    )
    (comp (ref "U25")
      (value "MURATA_MA40H1S-RMURATA_MA40H1S-R_0_0")
      (footprint "eagle-import:MURATA_MA40H1S-R_0")
      (fields
        (field (name "DIGIKEY_PART_NUMBER") "490-MA40H1S-RCT-ND")
        (field (name "MF") "Murata")
        (field (name "MOUSER_PART_NUMBER") "81-MA40H1S-R")
      )
      (libsource (lib "eagle-import") (part "MURATA_MA40H1S-RMURATA_MA40H1S-R_0_0"))
    )
    (comp (ref "U26")
      (value "MURATA_MA40H1S-RMURATA_MA40H1S-R_0_0")
      (footprint "eagle-import:MURATA_MA40H1S-R_0")
      (fields
        (field (name "DIGIKEY_PART_NUMBER") "490-MA40H1S-RCT-ND")
        (field (name "MF") "Murata")
        (field (name "MOUSER_PART_NUMBER") "81-MA40H1S-R")
      )
      (libsource (lib "eagle-import") (part "MURATA_MA40H1S-RMURATA_MA40H1S-R_0_0"))
    )
    (comp (ref "U27")
      (value "MURATA_MA40H1S-RMURATA_MA40H1S-R_0_0")
      (footprint "eagle-import:MURATA_MA40H1S-R_0")
      (fields
        (field (name "DIGIKEY_PART_NUMBER") "490-MA40H1S-RCT-ND")
        (field (name "MF") "Murata")
        (field (name "MOUSER_PART_NUMBER") "81-MA40H1S-R")
      )
      (libsource (lib "eagle-import") (part "MURATA_MA40H1S-RMURATA_MA40H1S-R_0_0"))
    )
    (comp (ref "U28")
      (value "MURATA_MA40H1S-RMURATA_MA40H1S-R_0_0")
      (footprint "eagle-import:MURATA_MA40H1S-R_0")
      (fields
        (field (name "DIGIKEY_PART_NUMBER") "490-MA40H1S-RCT-ND")
        (field (name "MF") "Murata")
        (field (name "MOUSER_PART_NUMBER") "81-MA40H1S-R")
      )
      (libsource (lib "eagle-import") (part "MURATA_MA40H1S-RMURATA_MA40H1S-R_0_0"))
    )
    (comp (ref "U29")
      (value "MURATA_MA40H1S-RMURATA_MA40H1S-R_0_0")
      (footprint "eagle-import:MURATA_MA40H1S-R_0")
      (fields
        (field (name "DIGIKEY_PART_NUMBER") "490-MA40H1S-RCT-ND")
        (field (name "MF") "Murata")
        (field (name "MOUSER_PART_NUMBER") "81-MA40H1S-R")
      )
      (libsource (lib "eagle-import") (part "MURATA_MA40H1S-RMURATA_MA40H1S-R_0_0"))
    )
    (comp (ref "U30")
      (value "MURATA_MA40H1S-RMURATA_MA40H1S-R_0_0")
      (footprint "eagle-import:MURATA_MA40H1S-R_0")
      (fields
        (field (name "DIGIKEY_PART_NUMBER") "490-MA40H1S-RCT-ND")
        (field (name "MF") "Murata")
        (field (name "MOUSER_PART_NUMBER") "81-MA40H1S-R")
      )
      (libsource (lib "eagle-import") (part "MURATA_MA40H1S-RMURATA_MA40H1S-R_0_0"))
    )
    (comp (ref "U31")
      (value "MURATA_MA40H1S-RMURATA_MA40H1S-R_0_0")
      (footprint "eagle-import:MURATA_MA40H1S-R_0")
      (fields
        (field (name "DIGIKEY_PART_NUMBER") "490-MA40H1S-RCT-ND")
        (field (name "MF") "Murata")
        (field (name "MOUSER_PART_NUMBER") "81-MA40H1S-R")
      )
      (libsource (lib "eagle-import") (part "MURATA_MA40H1S-RMURATA_MA40H1S-R_0_0"))
    )
    (comp (ref "U32")
      (value "MURATA_MA40H1S-RMURATA_MA40H1S-R_0_0")
      (footprint "eagle-import:MURATA_MA40H1S-R_0")
      (fields
        (field (name "DIGIKEY_PART_NUMBER") "490-MA40H1S-RCT-ND")
        (field (name "MF") "Murata")
        (field (name "MOUSER_PART_NUMBER") "81-MA40H1S-R")
      )
      (libsource (lib "eagle-import") (part "MURATA_MA40H1S-RMURATA_MA40H1S-R_0_0"))
    )
    (comp (ref "U33")
      (value "MURATA_MA40H1S-RMURATA_MA40H1S-R_0_0")
      (footprint "eagle-import:MURATA_MA40H1S-R_0")
      (fields
        (field (name "DIGIKEY_PART_NUMBER") "490-MA40H1S-RCT-ND")
        (field (name "MF") "Murata")
        (field (name "MOUSER_PART_NUMBER") "81-MA40H1S-R")
      )
      (libsource (lib "eagle-import") (part "MURATA_MA40H1S-RMURATA_MA40H1S-R_0_0"))
    )
    (comp (ref "U34")
      (value "MURATA_MA40H1S-RMURATA_MA40H1S-R_0_0")
      (footprint "eagle-import:MURATA_MA40H1S-R_0")
      (fields
        (field (name "DIGIKEY_PART_NUMBER") "490-MA40H1S-RCT-ND")
        (field (name "MF") "Murata")
        (field (name "MOUSER_PART_NUMBER") "81-MA40H1S-R")
      )
      (libsource (lib "eagle-import") (part "MURATA_MA40H1S-RMURATA_MA40H1S-R_0_0"))
    )
    (comp (ref "U35")
      (value "MURATA_MA40H1S-RMURATA_MA40H1S-R_0_0")
      (footprint "eagle-import:MURATA_MA40H1S-R_0")
      (fields
        (field (name "DIGIKEY_PART_NUMBER") "490-MA40H1S-RCT-ND")
        (field (name "MF") "Murata")
        (field (name "MOUSER_PART_NUMBER") "81-MA40H1S-R")
      )
      (libsource (lib "eagle-import") (part "MURATA_MA40H1S-RMURATA_MA40H1S-R_0_0"))
    )
    (comp (ref "U36")
      (value "MURATA_MA40H1S-RMURATA_MA40H1S-R_0_0")
      (footprint "eagle-import:MURATA_MA40H1S-R_0")
      (fields
        (field (name "DIGIKEY_PART_NUMBER") "490-MA40H1S-RCT-ND")
        (field (name "MF") "Murata")
        (field (name "MOUSER_PART_NUMBER") "81-MA40H1S-R")
      )
      (libsource (lib "eagle-import") (part "MURATA_MA40H1S-RMURATA_MA40H1S-R_0_0"))
    )
    (comp (ref "U37")
      (value "MURATA_MA40H1S-RMURATA_MA40H1S-R_0_0")
      (footprint "eagle-import:MURATA_MA40H1S-R_0")
      (fields
        (field (name "DIGIKEY_PART_NUMBER") "490-MA40H1S-RCT-ND")
        (field (name "MF") "Murata")
        (field (name "MOUSER_PART_NUMBER") "81-MA40H1S-R")
      )
      (libsource (lib "eagle-import") (part "MURATA_MA40H1S-RMURATA_MA40H1S-R_0_0"))
    )
    (comp (ref "U38")
      (value "MURATA_MA40H1S-RMURATA_MA40H1S-R_0_0")
      (footprint "eagle-import:MURATA_MA40H1S-R_0")
      (fields
        (field (name "DIGIKEY_PART_NUMBER") "490-MA40H1S-RCT-ND")
        (field (name "MF") "Murata")
        (field (name "MOUSER_PART_NUMBER") "81-MA40H1S-R")
      )
      (libsource (lib "eagle-import") (part "MURATA_MA40H1S-RMURATA_MA40H1S-R_0_0"))
    )
    (comp (ref "U39")
      (value "MURATA_MA40H1S-RMURATA_MA40H1S-R_0_0")
      (footprint "eagle-import:MURATA_MA40H1S-R_0")
      (fields
        (field (name "DIGIKEY_PART_NUMBER") "490-MA40H1S-RCT-ND")
        (field (name "MF") "Murata")
        (field (name "MOUSER_PART_NUMBER") "81-MA40H1S-R")
      )
      (libsource (lib "eagle-import") (part "MURATA_MA40H1S-RMURATA_MA40H1S-R_0_0"))
    )
    (comp (ref "U40")
      (value "MURATA_MA40H1S-RMURATA_MA40H1S-R_0_0")
      (footprint "eagle-import:MURATA_MA40H1S-R_0")
      (fields
        (field (name "DIGIKEY_PART_NUMBER") "490-MA40H1S-RCT-ND")
        (field (name "MF") "Murata")
        (field (name "MOUSER_PART_NUMBER") "81-MA40H1S-R")
      )
      (libsource (lib "eagle-import") (part "MURATA_MA40H1S-RMURATA_MA40H1S-R_0_0"))
    )
    (comp (ref "U41")
      (value "MURATA_MA40H1S-RMURATA_MA40H1S-R_0_0")
      (footprint "eagle-import:MURATA_MA40H1S-R_0")
      (fields
        (field (name "DIGIKEY_PART_NUMBER") "490-MA40H1S-RCT-ND")
        (field (name "MF") "Murata")
        (field (name "MOUSER_PART_NUMBER") "81-MA40H1S-R")
      )
      (libsource (lib "eagle-import") (part "MURATA_MA40H1S-RMURATA_MA40H1S-R_0_0"))
    )
    (comp (ref "U42")
      (value "MURATA_MA40H1S-RMURATA_MA40H1S-R_0_0")
      (footprint "eagle-import:MURATA_MA40H1S-R_0")
      (fields
        (field (name "DIGIKEY_PART_NUMBER") "490-MA40H1S-RCT-ND")
        (field (name "MF") "Murata")
        (field (name "MOUSER_PART_NUMBER") "81-MA40H1S-R")
      )
      (libsource (lib "eagle-import") (part "MURATA_MA40H1S-RMURATA_MA40H1S-R_0_0"))
    )
    (comp (ref "U43")
      (value "MURATA_MA40H1S-RMURATA_MA40H1S-R_0_0")
      (footprint "eagle-import:MURATA_MA40H1S-R_0")
      (fields
        (field (name "DIGIKEY_PART_NUMBER") "490-MA40H1S-RCT-ND")
        (field (name "MF") "Murata")
        (field (name "MOUSER_PART_NUMBER") "81-MA40H1S-R")
      )
      (libsource (lib "eagle-import") (part "MURATA_MA40H1S-RMURATA_MA40H1S-R_0_0"))
    )
    (comp (ref "U44")
      (value "MURATA_MA40H1S-RMURATA_MA40H1S-R_0_0")
      (footprint "eagle-import:MURATA_MA40H1S-R_0")
      (fields
        (field (name "DIGIKEY_PART_NUMBER") "490-MA40H1S-RCT-ND")
        (field (name "MF") "Murata")
        (field (name "MOUSER_PART_NUMBER") "81-MA40H1S-R")
      )
      (libsource (lib "eagle-import") (part "MURATA_MA40H1S-RMURATA_MA40H1S-R_0_0"))
    )
    (comp (ref "U45")
      (value "MURATA_MA40H1S-RMURATA_MA40H1S-R_0_0")
      (footprint "eagle-import:MURATA_MA40H1S-R_0")
      (fields
        (field (name "DIGIKEY_PART_NUMBER") "490-MA40H1S-RCT-ND")
        (field (name "MF") "Murata")
        (field (name "MOUSER_PART_NUMBER") "81-MA40H1S-R")
      )
      (libsource (lib "eagle-import") (part "MURATA_MA40H1S-RMURATA_MA40H1S-R_0_0"))
    )
    (comp (ref "U46")
      (value "MURATA_MA40H1S-RMURATA_MA40H1S-R_0_0")
      (footprint "eagle-import:MURATA_MA40H1S-R_0")
      (fields
        (field (name "DIGIKEY_PART_NUMBER") "490-MA40H1S-RCT-ND")
        (field (name "MF") "Murata")
        (field (name "MOUSER_PART_NUMBER") "81-MA40H1S-R")
      )
      (libsource (lib "eagle-import") (part "MURATA_MA40H1S-RMURATA_MA40H1S-R_0_0"))
    )
    (comp (ref "U47")
      (value "MURATA_MA40H1S-RMURATA_MA40H1S-R_0_0")
      (footprint "eagle-import:MURATA_MA40H1S-R_0")
      (fields
        (field (name "DIGIKEY_PART_NUMBER") "490-MA40H1S-RCT-ND")
        (field (name "MF") "Murata")
        (field (name "MOUSER_PART_NUMBER") "81-MA40H1S-R")
      )
      (libsource (lib "eagle-import") (part "MURATA_MA40H1S-RMURATA_MA40H1S-R_0_0"))
    )
    (comp (ref "U48")
      (value "MURATA_MA40H1S-RMURATA_MA40H1S-R_0_0")
      (footprint "eagle-import:MURATA_MA40H1S-R_0")
      (fields
        (field (name "DIGIKEY_PART_NUMBER") "490-MA40H1S-RCT-ND")
        (field (name "MF") "Murata")
        (field (name "MOUSER_PART_NUMBER") "81-MA40H1S-R")
      )
      (libsource (lib "eagle-import") (part "MURATA_MA40H1S-RMURATA_MA40H1S-R_0_0"))
    )
    (comp (ref "U49")
      (value "MURATA_MA40H1S-RMURATA_MA40H1S-R_0_0")
      (footprint "eagle-import:MURATA_MA40H1S-R_0")
      (fields
        (field (name "DIGIKEY_PART_NUMBER") "490-MA40H1S-RCT-ND")
        (field (name "MF") "Murata")
        (field (name "MOUSER_PART_NUMBER") "81-MA40H1S-R")
      )
      (libsource (lib "eagle-import") (part "MURATA_MA40H1S-RMURATA_MA40H1S-R_0_0"))
    )
    (comp (ref "U50")
      (value "MURATA_MA40H1S-RMURATA_MA40H1S-R_0_0")
      (footprint "eagle-import:MURATA_MA40H1S-R_0")
      (fields
        (field (name "DIGIKEY_PART_NUMBER") "490-MA40H1S-RCT-ND")
        (field (name "MF") "Murata")
        (field (name "MOUSER_PART_NUMBER") "81-MA40H1S-R")
      )
      (libsource (lib "eagle-import") (part "MURATA_MA40H1S-RMURATA_MA40H1S-R_0_0"))
    )
    (comp (ref "U51")
      (value "MURATA_MA40H1S-RMURATA_MA40H1S-R_0_0")
      (footprint "eagle-import:MURATA_MA40H1S-R_0")
      (fields
        (field (name "DIGIKEY_PART_NUMBER") "490-MA40H1S-RCT-ND")
        (field (name "MF") "Murata")
        (field (name "MOUSER_PART_NUMBER") "81-MA40H1S-R")
      )
      (libsource (lib "eagle-import") (part "MURATA_MA40H1S-RMURATA_MA40H1S-R_0_0"))
    )
    (comp (ref "U52")
      (value "MURATA_MA40H1S-RMURATA_MA40H1S-R_0_0")
      (footprint "eagle-import:MURATA_MA40H1S-R_0")
      (fields
        (field (name "DIGIKEY_PART_NUMBER") "490-MA40H1S-RCT-ND")
        (field (name "MF") "Murata")
        (field (name "MOUSER_PART_NUMBER") "81-MA40H1S-R")
      )
      (libsource (lib "eagle-import") (part "MURATA_MA40H1S-RMURATA_MA40H1S-R_0_0"))
    )
    (comp (ref "U53")
      (value "MURATA_MA40H1S-RMURATA_MA40H1S-R_0_0")
      (footprint "eagle-import:MURATA_MA40H1S-R_0")
      (fields
        (field (name "DIGIKEY_PART_NUMBER") "490-MA40H1S-RCT-ND")
        (field (name "MF") "Murata")
        (field (name "MOUSER_PART_NUMBER") "81-MA40H1S-R")
      )
      (libsource (lib "eagle-import") (part "MURATA_MA40H1S-RMURATA_MA40H1S-R_0_0"))
    )
    (comp (ref "U54")
      (value "MURATA_MA40H1S-RMURATA_MA40H1S-R_0_0")
      (footprint "eagle-import:MURATA_MA40H1S-R_0")
      (fields
        (field (name "DIGIKEY_PART_NUMBER") "490-MA40H1S-RCT-ND")
        (field (name "MF") "Murata")
        (field (name "MOUSER_PART_NUMBER") "81-MA40H1S-R")
      )
      (libsource (lib "eagle-import") (part "MURATA_MA40H1S-RMURATA_MA40H1S-R_0_0"))
    )
    (comp (ref "U55")
      (value "MURATA_MA40H1S-RMURATA_MA40H1S-R_0_0")
      (footprint "eagle-import:MURATA_MA40H1S-R_0")
      (fields
        (field (name "DIGIKEY_PART_NUMBER") "490-MA40H1S-RCT-ND")
        (field (name "MF") "Murata")
        (field (name "MOUSER_PART_NUMBER") "81-MA40H1S-R")
      )
      (libsource (lib "eagle-import") (part "MURATA_MA40H1S-RMURATA_MA40H1S-R_0_0"))
    )
    (comp (ref "U56")
      (value "MURATA_MA40H1S-RMURATA_MA40H1S-R_0_0")
      (footprint "eagle-import:MURATA_MA40H1S-R_0")
      (fields
        (field (name "DIGIKEY_PART_NUMBER") "490-MA40H1S-RCT-ND")
        (field (name "MF") "Murata")
        (field (name "MOUSER_PART_NUMBER") "81-MA40H1S-R")
      )
      (libsource (lib "eagle-import") (part "MURATA_MA40H1S-RMURATA_MA40H1S-R_0_0"))
    )
    (comp (ref "U57")
      (value "MURATA_MA40H1S-RMURATA_MA40H1S-R_0_0")
      (footprint "eagle-import:MURATA_MA40H1S-R_0")
      (fields
        (field (name "DIGIKEY_PART_NUMBER") "490-MA40H1S-RCT-ND")
        (field (name "MF") "Murata")
        (field (name "MOUSER_PART_NUMBER") "81-MA40H1S-R")
      )
      (libsource (lib "eagle-import") (part "MURATA_MA40H1S-RMURATA_MA40H1S-R_0_0"))
    )
    (comp (ref "U58")
      (value "MURATA_MA40H1S-RMURATA_MA40H1S-R_0_0")
      (footprint "eagle-import:MURATA_MA40H1S-R_0")
      (fields
        (field (name "DIGIKEY_PART_NUMBER") "490-MA40H1S-RCT-ND")
        (field (name "MF") "Murata")
        (field (name "MOUSER_PART_NUMBER") "81-MA40H1S-R")
      )
      (libsource (lib "eagle-import") (part "MURATA_MA40H1S-RMURATA_MA40H1S-R_0_0"))
    )
    (comp (ref "U59")
      (value "MURATA_MA40H1S-RMURATA_MA40H1S-R_0_0")
      (footprint "eagle-import:MURATA_MA40H1S-R_0")
      (fields
        (field (name "DIGIKEY_PART_NUMBER") "490-MA40H1S-RCT-ND")
        (field (name "MF") "Murata")
        (field (name "MOUSER_PART_NUMBER") "81-MA40H1S-R")
      )
      (libsource (lib "eagle-import") (part "MURATA_MA40H1S-RMURATA_MA40H1S-R_0_0"))
    )
    (comp (ref "U60")
      (value "MURATA_MA40H1S-RMURATA_MA40H1S-R_0_0")
      (footprint "eagle-import:MURATA_MA40H1S-R_0")
      (fields
        (field (name "DIGIKEY_PART_NUMBER") "490-MA40H1S-RCT-ND")
        (field (name "MF") "Murata")
        (field (name "MOUSER_PART_NUMBER") "81-MA40H1S-R")
      )
      (libsource (lib "eagle-import") (part "MURATA_MA40H1S-RMURATA_MA40H1S-R_0_0"))
    )
    (comp (ref "U61")
      (value "MURATA_MA40H1S-RMURATA_MA40H1S-R_0_0")
      (footprint "eagle-import:MURATA_MA40H1S-R_0")
      (fields
        (field (name "DIGIKEY_PART_NUMBER") "490-MA40H1S-RCT-ND")
        (field (name "MF") "Murata")
        (field (name "MOUSER_PART_NUMBER") "81-MA40H1S-R")
      )
      (libsource (lib "eagle-import") (part "MURATA_MA40H1S-RMURATA_MA40H1S-R_0_0"))
    )
    (comp (ref "U62")
      (value "MURATA_MA40H1S-RMURATA_MA40H1S-R_0_0")
      (footprint "eagle-import:MURATA_MA40H1S-R_0")
      (fields
        (field (name "DIGIKEY_PART_NUMBER") "490-MA40H1S-RCT-ND")
        (field (name "MF") "Murata")
        (field (name "MOUSER_PART_NUMBER") "81-MA40H1S-R")
      )
      (libsource (lib "eagle-import") (part "MURATA_MA40H1S-RMURATA_MA40H1S-R_0_0"))
    )
    (comp (ref "U63")
      (value "MURATA_MA40H1S-RMURATA_MA40H1S-R_0_0")
      (footprint "eagle-import:MURATA_MA40H1S-R_0")
      (fields
        (field (name "DIGIKEY_PART_NUMBER") "490-MA40H1S-RCT-ND")
        (field (name "MF") "Murata")
        (field (name "MOUSER_PART_NUMBER") "81-MA40H1S-R")
      )
      (libsource (lib "eagle-import") (part "MURATA_MA40H1S-RMURATA_MA40H1S-R_0_0"))
    )
    (comp (ref "U64")
      (value "MURATA_MA40H1S-RMURATA_MA40H1S-R_0_0")
      (footprint "eagle-import:MURATA_MA40H1S-R_0")
      (fields
        (field (name "DIGIKEY_PART_NUMBER") "490-MA40H1S-RCT-ND")
        (field (name "MF") "Murata")
        (field (name "MOUSER_PART_NUMBER") "81-MA40H1S-R")
      )
      (libsource (lib "eagle-import") (part "MURATA_MA40H1S-RMURATA_MA40H1S-R_0_0"))
    )
    (comp (ref "U65")
      (value "MURATA_MA40H1S-RMURATA_MA40H1S-R_0_0")
      (footprint "eagle-import:MURATA_MA40H1S-R_0")
      (fields
        (field (name "DIGIKEY_PART_NUMBER") "490-MA40H1S-RCT-ND")
        (field (name "MF") "Murata")
        (field (name "MOUSER_PART_NUMBER") "81-MA40H1S-R")
      )
      (libsource (lib "eagle-import") (part "MURATA_MA40H1S-RMURATA_MA40H1S-R_0_0"))
    )
    (comp (ref "U66")
      (value "MURATA_MA40H1S-RMURATA_MA40H1S-R_0_0")
      (footprint "eagle-import:MURATA_MA40H1S-R_0")
      (fields
        (field (name "DIGIKEY_PART_NUMBER") "490-MA40H1S-RCT-ND")
        (field (name "MF") "Murata")
        (field (name "MOUSER_PART_NUMBER") "81-MA40H1S-R")
      )
      (libsource (lib "eagle-import") (part "MURATA_MA40H1S-RMURATA_MA40H1S-R_0_0"))
    )
    (comp (ref "U67")
      (value "MURATA_MA40H1S-RMURATA_MA40H1S-R_0_0")
      (footprint "eagle-import:MURATA_MA40H1S-R_0")
      (fields
        (field (name "DIGIKEY_PART_NUMBER") "490-MA40H1S-RCT-ND")
        (field (name "MF") "Murata")
        (field (name "MOUSER_PART_NUMBER") "81-MA40H1S-R")
      )
      (libsource (lib "eagle-import") (part "MURATA_MA40H1S-RMURATA_MA40H1S-R_0_0"))
    )
    (comp (ref "U68")
      (value "MURATA_MA40H1S-RMURATA_MA40H1S-R_0_0")
      (footprint "eagle-import:MURATA_MA40H1S-R_0")
      (fields
        (field (name "DIGIKEY_PART_NUMBER") "490-MA40H1S-RCT-ND")
        (field (name "MF") "Murata")
        (field (name "MOUSER_PART_NUMBER") "81-MA40H1S-R")
      )
      (libsource (lib "eagle-import") (part "MURATA_MA40H1S-RMURATA_MA40H1S-R_0_0"))
    )
    (comp (ref "U69")
      (value "MURATA_MA40H1S-RMURATA_MA40H1S-R_0_0")
      (footprint "eagle-import:MURATA_MA40H1S-R_0")
      (fields
        (field (name "DIGIKEY_PART_NUMBER") "490-MA40H1S-RCT-ND")
        (field (name "MF") "Murata")
        (field (name "MOUSER_PART_NUMBER") "81-MA40H1S-R")
      )
      (libsource (lib "eagle-import") (part "MURATA_MA40H1S-RMURATA_MA40H1S-R_0_0"))
    )
    (comp (ref "U70")
      (value "MURATA_MA40H1S-RMURATA_MA40H1S-R_0_0")
      (footprint "eagle-import:MURATA_MA40H1S-R_0")
      (fields
        (field (name "DIGIKEY_PART_NUMBER") "490-MA40H1S-RCT-ND")
        (field (name "MF") "Murata")
        (field (name "MOUSER_PART_NUMBER") "81-MA40H1S-R")
      )
      (libsource (lib "eagle-import") (part "MURATA_MA40H1S-RMURATA_MA40H1S-R_0_0"))
    )
    (comp (ref "U71")
      (value "MURATA_MA40H1S-RMURATA_MA40H1S-R_0_0")
      (footprint "eagle-import:MURATA_MA40H1S-R_0")
      (fields
        (field (name "DIGIKEY_PART_NUMBER") "490-MA40H1S-RCT-ND")
        (field (name "MF") "Murata")
        (field (name "MOUSER_PART_NUMBER") "81-MA40H1S-R")
      )
      (libsource (lib "eagle-import") (part "MURATA_MA40H1S-RMURATA_MA40H1S-R_0_0"))
    )
    (comp (ref "U72")
      (value "MURATA_MA40H1S-RMURATA_MA40H1S-R_0_0")
      (footprint "eagle-import:MURATA_MA40H1S-R_0")
      (fields
        (field (name "DIGIKEY_PART_NUMBER") "490-MA40H1S-RCT-ND")
        (field (name "MF") "Murata")
        (field (name "MOUSER_PART_NUMBER") "81-MA40H1S-R")
      )
      (libsource (lib "eagle-import") (part "MURATA_MA40H1S-RMURATA_MA40H1S-R_0_0"))
    )
    (comp (ref "U73")
      (value "MURATA_MA40H1S-RMURATA_MA40H1S-R_0_0")
      (footprint "eagle-import:MURATA_MA40H1S-R_0")
      (fields
        (field (name "DIGIKEY_PART_NUMBER") "490-MA40H1S-RCT-ND")
        (field (name "MF") "Murata")
        (field (name "MOUSER_PART_NUMBER") "81-MA40H1S-R")
      )
      (libsource (lib "eagle-import") (part "MURATA_MA40H1S-RMURATA_MA40H1S-R_0_0"))
    )
    (comp (ref "U74")
      (value "MURATA_MA40H1S-RMURATA_MA40H1S-R_0_0")
      (footprint "eagle-import:MURATA_MA40H1S-R_0")
      (fields
        (field (name "DIGIKEY_PART_NUMBER") "490-MA40H1S-RCT-ND")
        (field (name "MF") "Murata")
        (field (name "MOUSER_PART_NUMBER") "81-MA40H1S-R")
      )
      (libsource (lib "eagle-import") (part "MURATA_MA40H1S-RMURATA_MA40H1S-R_0_0"))
    )
    (comp (ref "U75")
      (value "MURATA_MA40H1S-RMURATA_MA40H1S-R_0_0")
      (footprint "eagle-import:MURATA_MA40H1S-R_0")
      (fields
        (field (name "DIGIKEY_PART_NUMBER") "490-MA40H1S-RCT-ND")
        (field (name "MF") "Murata")
        (field (name "MOUSER_PART_NUMBER") "81-MA40H1S-R")
      )
      (libsource (lib "eagle-import") (part "MURATA_MA40H1S-RMURATA_MA40H1S-R_0_0"))
    )
    (comp (ref "U76")
      (value "MURATA_MA40H1S-RMURATA_MA40H1S-R_0_0")
      (footprint "eagle-import:MURATA_MA40H1S-R_0")
      (fields
        (field (name "DIGIKEY_PART_NUMBER") "490-MA40H1S-RCT-ND")
        (field (name "MF") "Murata")
        (field (name "MOUSER_PART_NUMBER") "81-MA40H1S-R")
      )
      (libsource (lib "eagle-import") (part "MURATA_MA40H1S-RMURATA_MA40H1S-R_0_0"))
    )
    (comp (ref "U77")
      (value "MURATA_MA40H1S-RMURATA_MA40H1S-R_0_0")
      (footprint "eagle-import:MURATA_MA40H1S-R_0")
      (fields
        (field (name "DIGIKEY_PART_NUMBER") "490-MA40H1S-RCT-ND")
        (field (name "MF") "Murata")
        (field (name "MOUSER_PART_NUMBER") "81-MA40H1S-R")
      )
      (libsource (lib "eagle-import") (part "MURATA_MA40H1S-RMURATA_MA40H1S-R_0_0"))
    )
    (comp (ref "U78")
      (value "MURATA_MA40H1S-RMURATA_MA40H1S-R_0_0")
      (footprint "eagle-import:MURATA_MA40H1S-R_0")
      (fields
        (field (name "DIGIKEY_PART_NUMBER") "490-MA40H1S-RCT-ND")
        (field (name "MF") "Murata")
        (field (name "MOUSER_PART_NUMBER") "81-MA40H1S-R")
      )
      (libsource (lib "eagle-import") (part "MURATA_MA40H1S-RMURATA_MA40H1S-R_0_0"))
    )
    (comp (ref "U79")
      (value "MURATA_MA40H1S-RMURATA_MA40H1S-R_0_0")
      (footprint "eagle-import:MURATA_MA40H1S-R_0")
      (fields
        (field (name "DIGIKEY_PART_NUMBER") "490-MA40H1S-RCT-ND")
        (field (name "MF") "Murata")
        (field (name "MOUSER_PART_NUMBER") "81-MA40H1S-R")
      )
      (libsource (lib "eagle-import") (part "MURATA_MA40H1S-RMURATA_MA40H1S-R_0_0"))
    )
    (comp (ref "U80")
      (value "MURATA_MA40H1S-RMURATA_MA40H1S-R_0_0")
      (footprint "eagle-import:MURATA_MA40H1S-R_0")
      (fields
        (field (name "DIGIKEY_PART_NUMBER") "490-MA40H1S-RCT-ND")
        (field (name "MF") "Murata")
        (field (name "MOUSER_PART_NUMBER") "81-MA40H1S-R")
      )
      (libsource (lib "eagle-import") (part "MURATA_MA40H1S-RMURATA_MA40H1S-R_0_0"))
    )
    (comp (ref "U90")
      (value "MURATA_MA40H1S-RMURATA_MA40H1S-R_0_0")
      (footprint "eagle-import:MURATA_MA40H1S-R_0")
      (fields
        (field (name "DIGIKEY_PART_NUMBER") "490-MA40H1S-RCT-ND")
        (field (name "MF") "Murata")
        (field (name "MOUSER_PART_NUMBER") "81-MA40H1S-R")
      )
      (libsource (lib "eagle-import") (part "MURATA_MA40H1S-RMURATA_MA40H1S-R_0_0"))
    )
    (comp (ref "U91")
      (value "MURATA_MA40H1S-RMURATA_MA40H1S-R_0_0")
      (footprint "eagle-import:MURATA_MA40H1S-R_0")
      (fields
        (field (name "DIGIKEY_PART_NUMBER") "490-MA40H1S-RCT-ND")
        (field (name "MF") "Murata")
        (field (name "MOUSER_PART_NUMBER") "81-MA40H1S-R")
      )
      (libsource (lib "eagle-import") (part "MURATA_MA40H1S-RMURATA_MA40H1S-R_0_0"))
    )
    (comp (ref "U92")
      (value "MURATA_MA40H1S-RMURATA_MA40H1S-R_0_0")
      (footprint "eagle-import:MURATA_MA40H1S-R_0")
      (fields
        (field (name "DIGIKEY_PART_NUMBER") "490-MA40H1S-RCT-ND")
        (field (name "MF") "Murata")
        (field (name "MOUSER_PART_NUMBER") "81-MA40H1S-R")
      )
      (libsource (lib "eagle-import") (part "MURATA_MA40H1S-RMURATA_MA40H1S-R_0_0"))
    )
    (comp (ref "U93")
      (value "MURATA_MA40H1S-RMURATA_MA40H1S-R_0_0")
      (footprint "eagle-import:MURATA_MA40H1S-R_0")
      (fields
        (field (name "DIGIKEY_PART_NUMBER") "490-MA40H1S-RCT-ND")
        (field (name "MF") "Murata")
        (field (name "MOUSER_PART_NUMBER") "81-MA40H1S-R")
      )
      (libsource (lib "eagle-import") (part "MURATA_MA40H1S-RMURATA_MA40H1S-R_0_0"))
    )
    (comp (ref "U94")
      (value "MURATA_MA40H1S-RMURATA_MA40H1S-R_0_0")
      (footprint "eagle-import:MURATA_MA40H1S-R_0")
      (fields
        (field (name "DIGIKEY_PART_NUMBER") "490-MA40H1S-RCT-ND")
        (field (name "MF") "Murata")
        (field (name "MOUSER_PART_NUMBER") "81-MA40H1S-R")
      )
      (libsource (lib "eagle-import") (part "MURATA_MA40H1S-RMURATA_MA40H1S-R_0_0"))
    )
    (comp (ref "U95")
      (value "MURATA_MA40H1S-RMURATA_MA40H1S-R_0_0")
      (footprint "eagle-import:MURATA_MA40H1S-R_0")
      (fields
        (field (name "DIGIKEY_PART_NUMBER") "490-MA40H1S-RCT-ND")
        (field (name "MF") "Murata")
        (field (name "MOUSER_PART_NUMBER") "81-MA40H1S-R")
      )
      (libsource (lib "eagle-import") (part "MURATA_MA40H1S-RMURATA_MA40H1S-R_0_0"))
    )
    (comp (ref "U96")
      (value "MURATA_MA40H1S-RMURATA_MA40H1S-R_0_0")
      (footprint "eagle-import:MURATA_MA40H1S-R_0")
      (fields
        (field (name "DIGIKEY_PART_NUMBER") "490-MA40H1S-RCT-ND")
        (field (name "MF") "Murata")
        (field (name "MOUSER_PART_NUMBER") "81-MA40H1S-R")
      )
      (libsource (lib "eagle-import") (part "MURATA_MA40H1S-RMURATA_MA40H1S-R_0_0"))
    )
    (comp (ref "U97")
      (value "MURATA_MA40H1S-RMURATA_MA40H1S-R_0_0")
      (footprint "eagle-import:MURATA_MA40H1S-R_0")
      (fields
        (field (name "DIGIKEY_PART_NUMBER") "490-MA40H1S-RCT-ND")
        (field (name "MF") "Murata")
        (field (name "MOUSER_PART_NUMBER") "81-MA40H1S-R")
      )
      (libsource (lib "eagle-import") (part "MURATA_MA40H1S-RMURATA_MA40H1S-R_0_0"))
    )
    (comp (ref "U98")
      (value "MURATA_MA40H1S-RMURATA_MA40H1S-R_0_0")
      (footprint "eagle-import:MURATA_MA40H1S-R_0")
      (fields
        (field (name "DIGIKEY_PART_NUMBER") "490-MA40H1S-RCT-ND")
        (field (name "MF") "Murata")
        (field (name "MOUSER_PART_NUMBER") "81-MA40H1S-R")
      )
      (libsource (lib "eagle-import") (part "MURATA_MA40H1S-RMURATA_MA40H1S-R_0_0"))
    )
    (comp (ref "U99")
      (value "MURATA_MA40H1S-RMURATA_MA40H1S-R_0_0")
      (footprint "eagle-import:MURATA_MA40H1S-R_0")
      (fields
        (field (name "DIGIKEY_PART_NUMBER") "490-MA40H1S-RCT-ND")
        (field (name "MF") "Murata")
        (field (name "MOUSER_PART_NUMBER") "81-MA40H1S-R")
      )
      (libsource (lib "eagle-import") (part "MURATA_MA40H1S-RMURATA_MA40H1S-R_0_0"))
    )
    (comp (ref "U100")
      (value "MURATA_MA40H1S-RMURATA_MA40H1S-R_0_0")
      (footprint "eagle-import:MURATA_MA40H1S-R_0")
      (fields
        (field (name "DIGIKEY_PART_NUMBER") "490-MA40H1S-RCT-ND")
        (field (name "MF") "Murata")
        (field (name "MOUSER_PART_NUMBER") "81-MA40H1S-R")
      )
      (libsource (lib "eagle-import") (part "MURATA_MA40H1S-RMURATA_MA40H1S-R_0_0"))
    )
    (comp (ref "U101")
      (value "MURATA_MA40H1S-RMURATA_MA40H1S-R_0_0")
      (footprint "eagle-import:MURATA_MA40H1S-R_0")
      (fields
        (field (name "DIGIKEY_PART_NUMBER") "490-MA40H1S-RCT-ND")
        (field (name "MF") "Murata")
        (field (name "MOUSER_PART_NUMBER") "81-MA40H1S-R")
      )
      (libsource (lib "eagle-import") (part "MURATA_MA40H1S-RMURATA_MA40H1S-R_0_0"))
    )
    (comp (ref "U102")
      (value "MURATA_MA40H1S-RMURATA_MA40H1S-R_0_0")
      (footprint "eagle-import:MURATA_MA40H1S-R_0")
      (fields
        (field (name "DIGIKEY_PART_NUMBER") "490-MA40H1S-RCT-ND")
        (field (name "MF") "Murata")
        (field (name "MOUSER_PART_NUMBER") "81-MA40H1S-R")
      )
      (libsource (lib "eagle-import") (part "MURATA_MA40H1S-RMURATA_MA40H1S-R_0_0"))
    )
    (comp (ref "U103")
      (value "MURATA_MA40H1S-RMURATA_MA40H1S-R_0_0")
      (footprint "eagle-import:MURATA_MA40H1S-R_0")
      (fields
        (field (name "DIGIKEY_PART_NUMBER") "490-MA40H1S-RCT-ND")
        (field (name "MF") "Murata")
        (field (name "MOUSER_PART_NUMBER") "81-MA40H1S-R")
      )
      (libsource (lib "eagle-import") (part "MURATA_MA40H1S-RMURATA_MA40H1S-R_0_0"))
    )
    (comp (ref "U104")
      (value "MURATA_MA40H1S-RMURATA_MA40H1S-R_0_0")
      (footprint "eagle-import:MURATA_MA40H1S-R_0")
      (fields
        (field (name "DIGIKEY_PART_NUMBER") "490-MA40H1S-RCT-ND")
        (field (name "MF") "Murata")
        (field (name "MOUSER_PART_NUMBER") "81-MA40H1S-R")
      )
      (libsource (lib "eagle-import") (part "MURATA_MA40H1S-RMURATA_MA40H1S-R_0_0"))
    )
    (comp (ref "U105")
      (value "MURATA_MA40H1S-RMURATA_MA40H1S-R_0_0")
      (footprint "eagle-import:MURATA_MA40H1S-R_0")
      (fields
        (field (name "DIGIKEY_PART_NUMBER") "490-MA40H1S-RCT-ND")
        (field (name "MF") "Murata")
        (field (name "MOUSER_PART_NUMBER") "81-MA40H1S-R")
      )
      (libsource (lib "eagle-import") (part "MURATA_MA40H1S-RMURATA_MA40H1S-R_0_0"))
    )
    (comp (ref "U106")
      (value "MURATA_MA40H1S-RMURATA_MA40H1S-R_0_0")
      (footprint "eagle-import:MURATA_MA40H1S-R_0")
      (fields
        (field (name "DIGIKEY_PART_NUMBER") "490-MA40H1S-RCT-ND")
        (field (name "MF") "Murata")
        (field (name "MOUSER_PART_NUMBER") "81-MA40H1S-R")
      )
      (libsource (lib "eagle-import") (part "MURATA_MA40H1S-RMURATA_MA40H1S-R_0_0"))
    )
    (comp (ref "U107")
      (value "MURATA_MA40H1S-RMURATA_MA40H1S-R_0_0")
      (footprint "eagle-import:MURATA_MA40H1S-R_0")
      (fields
        (field (name "DIGIKEY_PART_NUMBER") "490-MA40H1S-RCT-ND")
        (field (name "MF") "Murata")
        (field (name "MOUSER_PART_NUMBER") "81-MA40H1S-R")
      )
      (libsource (lib "eagle-import") (part "MURATA_MA40H1S-RMURATA_MA40H1S-R_0_0"))
    )
    (comp (ref "U108")
      (value "MURATA_MA40H1S-RMURATA_MA40H1S-R_0_0")
      (footprint "eagle-import:MURATA_MA40H1S-R_0")
      (fields
        (field (name "DIGIKEY_PART_NUMBER") "490-MA40H1S-RCT-ND")
        (field (name "MF") "Murata")
        (field (name "MOUSER_PART_NUMBER") "81-MA40H1S-R")
      )
      (libsource (lib "eagle-import") (part "MURATA_MA40H1S-RMURATA_MA40H1S-R_0_0"))
    )
    (comp (ref "U109")
      (value "MURATA_MA40H1S-RMURATA_MA40H1S-R_0_0")
      (footprint "eagle-import:MURATA_MA40H1S-R_0")
      (fields
        (field (name "DIGIKEY_PART_NUMBER") "490-MA40H1S-RCT-ND")
        (field (name "MF") "Murata")
        (field (name "MOUSER_PART_NUMBER") "81-MA40H1S-R")
      )
      (libsource (lib "eagle-import") (part "MURATA_MA40H1S-RMURATA_MA40H1S-R_0_0"))
    )
    (comp (ref "U110")
      (value "MURATA_MA40H1S-RMURATA_MA40H1S-R_0_0")
      (footprint "eagle-import:MURATA_MA40H1S-R_0")
      (fields
        (field (name "DIGIKEY_PART_NUMBER") "490-MA40H1S-RCT-ND")
        (field (name "MF") "Murata")
        (field (name "MOUSER_PART_NUMBER") "81-MA40H1S-R")
      )
      (libsource (lib "eagle-import") (part "MURATA_MA40H1S-RMURATA_MA40H1S-R_0_0"))
    )
    (comp (ref "U111")
      (value "MURATA_MA40H1S-RMURATA_MA40H1S-R_0_0")
      (footprint "eagle-import:MURATA_MA40H1S-R_0")
      (fields
        (field (name "DIGIKEY_PART_NUMBER") "490-MA40H1S-RCT-ND")
        (field (name "MF") "Murata")
        (field (name "MOUSER_PART_NUMBER") "81-MA40H1S-R")
      )
      (libsource (lib "eagle-import") (part "MURATA_MA40H1S-RMURATA_MA40H1S-R_0_0"))
    )
    (comp (ref "U112")
      (value "MURATA_MA40H1S-RMURATA_MA40H1S-R_0_0")
      (footprint "eagle-import:MURATA_MA40H1S-R_0")
      (fields
        (field (name "DIGIKEY_PART_NUMBER") "490-MA40H1S-RCT-ND")
        (field (name "MF") "Murata")
        (field (name "MOUSER_PART_NUMBER") "81-MA40H1S-R")
      )
      (libsource (lib "eagle-import") (part "MURATA_MA40H1S-RMURATA_MA40H1S-R_0_0"))
    )
    (comp (ref "U113")
      (value "MURATA_MA40H1S-RMURATA_MA40H1S-R_0_0")
      (footprint "eagle-import:MURATA_MA40H1S-R_0")
      (fields
        (field (name "DIGIKEY_PART_NUMBER") "490-MA40H1S-RCT-ND")
        (field (name "MF") "Murata")
        (field (name "MOUSER_PART_NUMBER") "81-MA40H1S-R")
      )
      (libsource (lib "eagle-import") (part "MURATA_MA40H1S-RMURATA_MA40H1S-R_0_0"))
    )
    (comp (ref "U114")
      (value "MURATA_MA40H1S-RMURATA_MA40H1S-R_0_0")
      (footprint "eagle-import:MURATA_MA40H1S-R_0")
      (fields
        (field (name "DIGIKEY_PART_NUMBER") "490-MA40H1S-RCT-ND")
        (field (name "MF") "Murata")
        (field (name "MOUSER_PART_NUMBER") "81-MA40H1S-R")
      )
      (libsource (lib "eagle-import") (part "MURATA_MA40H1S-RMURATA_MA40H1S-R_0_0"))
    )
    (comp (ref "U115")
      (value "MURATA_MA40H1S-RMURATA_MA40H1S-R_0_0")
      (footprint "eagle-import:MURATA_MA40H1S-R_0")
      (fields
        (field (name "DIGIKEY_PART_NUMBER") "490-MA40H1S-RCT-ND")
        (field (name "MF") "Murata")
        (field (name "MOUSER_PART_NUMBER") "81-MA40H1S-R")
      )
      (libsource (lib "eagle-import") (part "MURATA_MA40H1S-RMURATA_MA40H1S-R_0_0"))
    )
    (comp (ref "U116")
      (value "MURATA_MA40H1S-RMURATA_MA40H1S-R_0_0")
      (footprint "eagle-import:MURATA_MA40H1S-R_0")
      (fields
        (field (name "DIGIKEY_PART_NUMBER") "490-MA40H1S-RCT-ND")
        (field (name "MF") "Murata")
        (field (name "MOUSER_PART_NUMBER") "81-MA40H1S-R")
      )
      (libsource (lib "eagle-import") (part "MURATA_MA40H1S-RMURATA_MA40H1S-R_0_0"))
    )
    (comp (ref "U117")
      (value "MURATA_MA40H1S-RMURATA_MA40H1S-R_0_0")
      (footprint "eagle-import:MURATA_MA40H1S-R_0")
      (fields
        (field (name "DIGIKEY_PART_NUMBER") "490-MA40H1S-RCT-ND")
        (field (name "MF") "Murata")
        (field (name "MOUSER_PART_NUMBER") "81-MA40H1S-R")
      )
      (libsource (lib "eagle-import") (part "MURATA_MA40H1S-RMURATA_MA40H1S-R_0_0"))
    )
    (comp (ref "U118")
      (value "MURATA_MA40H1S-RMURATA_MA40H1S-R_0_0")
      (footprint "eagle-import:MURATA_MA40H1S-R_0")
      (fields
        (field (name "DIGIKEY_PART_NUMBER") "490-MA40H1S-RCT-ND")
        (field (name "MF") "Murata")
        (field (name "MOUSER_PART_NUMBER") "81-MA40H1S-R")
      )
      (libsource (lib "eagle-import") (part "MURATA_MA40H1S-RMURATA_MA40H1S-R_0_0"))
    )
    (comp (ref "U119")
      (value "MURATA_MA40H1S-RMURATA_MA40H1S-R_0_0")
      (footprint "eagle-import:MURATA_MA40H1S-R_0")
      (fields
        (field (name "DIGIKEY_PART_NUMBER") "490-MA40H1S-RCT-ND")
        (field (name "MF") "Murata")
        (field (name "MOUSER_PART_NUMBER") "81-MA40H1S-R")
      )
      (libsource (lib "eagle-import") (part "MURATA_MA40H1S-RMURATA_MA40H1S-R_0_0"))
    )
    (comp (ref "U120")
      (value "MURATA_MA40H1S-RMURATA_MA40H1S-R_0_0")
      (footprint "eagle-import:MURATA_MA40H1S-R_0")
      (fields
        (field (name "DIGIKEY_PART_NUMBER") "490-MA40H1S-RCT-ND")
        (field (name "MF") "Murata")
        (field (name "MOUSER_PART_NUMBER") "81-MA40H1S-R")
      )
      (libsource (lib "eagle-import") (part "MURATA_MA40H1S-RMURATA_MA40H1S-R_0_0"))
    )
    (comp (ref "U121")
      (value "MURATA_MA40H1S-RMURATA_MA40H1S-R_0_0")
      (footprint "eagle-import:MURATA_MA40H1S-R_0")
      (fields
        (field (name "DIGIKEY_PART_NUMBER") "490-MA40H1S-RCT-ND")
        (field (name "MF") "Murata")
        (field (name "MOUSER_PART_NUMBER") "81-MA40H1S-R")
      )
      (libsource (lib "eagle-import") (part "MURATA_MA40H1S-RMURATA_MA40H1S-R_0_0"))
    )
    (comp (ref "U122")
      (value "MURATA_MA40H1S-RMURATA_MA40H1S-R_0_0")
      (footprint "eagle-import:MURATA_MA40H1S-R_0")
      (fields
        (field (name "DIGIKEY_PART_NUMBER") "490-MA40H1S-RCT-ND")
        (field (name "MF") "Murata")
        (field (name "MOUSER_PART_NUMBER") "81-MA40H1S-R")
      )
      (libsource (lib "eagle-import") (part "MURATA_MA40H1S-RMURATA_MA40H1S-R_0_0"))
    )
    (comp (ref "U123")
      (value "MURATA_MA40H1S-RMURATA_MA40H1S-R_0_0")
      (footprint "eagle-import:MURATA_MA40H1S-R_0")
      (fields
        (field (name "DIGIKEY_PART_NUMBER") "490-MA40H1S-RCT-ND")
        (field (name "MF") "Murata")
        (field (name "MOUSER_PART_NUMBER") "81-MA40H1S-R")
      )
      (libsource (lib "eagle-import") (part "MURATA_MA40H1S-RMURATA_MA40H1S-R_0_0"))
    )
    (comp (ref "U124")
      (value "MURATA_MA40H1S-RMURATA_MA40H1S-R_0_0")
      (footprint "eagle-import:MURATA_MA40H1S-R_0")
      (fields
        (field (name "DIGIKEY_PART_NUMBER") "490-MA40H1S-RCT-ND")
        (field (name "MF") "Murata")
        (field (name "MOUSER_PART_NUMBER") "81-MA40H1S-R")
      )
      (libsource (lib "eagle-import") (part "MURATA_MA40H1S-RMURATA_MA40H1S-R_0_0"))
    )
    (comp (ref "U125")
      (value "MURATA_MA40H1S-RMURATA_MA40H1S-R_0_0")
      (footprint "eagle-import:MURATA_MA40H1S-R_0")
      (fields
        (field (name "DIGIKEY_PART_NUMBER") "490-MA40H1S-RCT-ND")
        (field (name "MF") "Murata")
        (field (name "MOUSER_PART_NUMBER") "81-MA40H1S-R")
      )
      (libsource (lib "eagle-import") (part "MURATA_MA40H1S-RMURATA_MA40H1S-R_0_0"))
    )
    (comp (ref "U126")
      (value "MURATA_MA40H1S-RMURATA_MA40H1S-R_0_0")
      (footprint "eagle-import:MURATA_MA40H1S-R_0")
      (fields
        (field (name "DIGIKEY_PART_NUMBER") "490-MA40H1S-RCT-ND")
        (field (name "MF") "Murata")
        (field (name "MOUSER_PART_NUMBER") "81-MA40H1S-R")
      )
      (libsource (lib "eagle-import") (part "MURATA_MA40H1S-RMURATA_MA40H1S-R_0_0"))
    )
    (comp (ref "U127")
      (value "MURATA_MA40H1S-RMURATA_MA40H1S-R_0_0")
      (footprint "eagle-import:MURATA_MA40H1S-R_0")
      (fields
        (field (name "DIGIKEY_PART_NUMBER") "490-MA40H1S-RCT-ND")
        (field (name "MF") "Murata")
        (field (name "MOUSER_PART_NUMBER") "81-MA40H1S-R")
      )
      (libsource (lib "eagle-import") (part "MURATA_MA40H1S-RMURATA_MA40H1S-R_0_0"))
    )
    (comp (ref "U128")
      (value "MURATA_MA40H1S-RMURATA_MA40H1S-R_0_0")
      (footprint "eagle-import:MURATA_MA40H1S-R_0")
      (fields
        (field (name "DIGIKEY_PART_NUMBER") "490-MA40H1S-RCT-ND")
        (field (name "MF") "Murata")
        (field (name "MOUSER_PART_NUMBER") "81-MA40H1S-R")
      )
      (libsource (lib "eagle-import") (part "MURATA_MA40H1S-RMURATA_MA40H1S-R_0_0"))
    )
    (comp (ref "U129")
      (value "MURATA_MA40H1S-RMURATA_MA40H1S-R_0_0")
      (footprint "eagle-import:MURATA_MA40H1S-R_0")
      (fields
        (field (name "DIGIKEY_PART_NUMBER") "490-MA40H1S-RCT-ND")
        (field (name "MF") "Murata")
        (field (name "MOUSER_PART_NUMBER") "81-MA40H1S-R")
      )
      (libsource (lib "eagle-import") (part "MURATA_MA40H1S-RMURATA_MA40H1S-R_0_0"))
    )
    (comp (ref "U130")
      (value "MURATA_MA40H1S-RMURATA_MA40H1S-R_0_0")
      (footprint "eagle-import:MURATA_MA40H1S-R_0")
      (fields
        (field (name "DIGIKEY_PART_NUMBER") "490-MA40H1S-RCT-ND")
        (field (name "MF") "Murata")
        (field (name "MOUSER_PART_NUMBER") "81-MA40H1S-R")
      )
      (libsource (lib "eagle-import") (part "MURATA_MA40H1S-RMURATA_MA40H1S-R_0_0"))
    )
    (comp (ref "U131")
      (value "MURATA_MA40H1S-RMURATA_MA40H1S-R_0_0")
      (footprint "eagle-import:MURATA_MA40H1S-R_0")
      (fields
        (field (name "DIGIKEY_PART_NUMBER") "490-MA40H1S-RCT-ND")
        (field (name "MF") "Murata")
        (field (name "MOUSER_PART_NUMBER") "81-MA40H1S-R")
      )
      (libsource (lib "eagle-import") (part "MURATA_MA40H1S-RMURATA_MA40H1S-R_0_0"))
    )
    (comp (ref "U132")
      (value "MURATA_MA40H1S-RMURATA_MA40H1S-R_0_0")
      (footprint "eagle-import:MURATA_MA40H1S-R_0")
      (fields
        (field (name "DIGIKEY_PART_NUMBER") "490-MA40H1S-RCT-ND")
        (field (name "MF") "Murata")
        (field (name "MOUSER_PART_NUMBER") "81-MA40H1S-R")
      )
      (libsource (lib "eagle-import") (part "MURATA_MA40H1S-RMURATA_MA40H1S-R_0_0"))
    )
    (comp (ref "U133")
      (value "MURATA_MA40H1S-RMURATA_MA40H1S-R_0_0")
      (footprint "eagle-import:MURATA_MA40H1S-R_0")
      (fields
        (field (name "DIGIKEY_PART_NUMBER") "490-MA40H1S-RCT-ND")
        (field (name "MF") "Murata")
        (field (name "MOUSER_PART_NUMBER") "81-MA40H1S-R")
      )
      (libsource (lib "eagle-import") (part "MURATA_MA40H1S-RMURATA_MA40H1S-R_0_0"))
    )
    (comp (ref "U134")
      (value "MURATA_MA40H1S-RMURATA_MA40H1S-R_0_0")
      (footprint "eagle-import:MURATA_MA40H1S-R_0")
      (fields
        (field (name "DIGIKEY_PART_NUMBER") "490-MA40H1S-RCT-ND")
        (field (name "MF") "Murata")
        (field (name "MOUSER_PART_NUMBER") "81-MA40H1S-R")
      )
      (libsource (lib "eagle-import") (part "MURATA_MA40H1S-RMURATA_MA40H1S-R_0_0"))
    )
    (comp (ref "U135")
      (value "MURATA_MA40H1S-RMURATA_MA40H1S-R_0_0")
      (footprint "eagle-import:MURATA_MA40H1S-R_0")
      (fields
        (field (name "DIGIKEY_PART_NUMBER") "490-MA40H1S-RCT-ND")
        (field (name "MF") "Murata")
        (field (name "MOUSER_PART_NUMBER") "81-MA40H1S-R")
      )
      (libsource (lib "eagle-import") (part "MURATA_MA40H1S-RMURATA_MA40H1S-R_0_0"))
    )
    (comp (ref "U136")
      (value "MURATA_MA40H1S-RMURATA_MA40H1S-R_0_0")
      (footprint "eagle-import:MURATA_MA40H1S-R_0")
      (fields
        (field (name "DIGIKEY_PART_NUMBER") "490-MA40H1S-RCT-ND")
        (field (name "MF") "Murata")
        (field (name "MOUSER_PART_NUMBER") "81-MA40H1S-R")
      )
      (libsource (lib "eagle-import") (part "MURATA_MA40H1S-RMURATA_MA40H1S-R_0_0"))
    )
    (comp (ref "U137")
      (value "MURATA_MA40H1S-RMURATA_MA40H1S-R_0_0")
      (footprint "eagle-import:MURATA_MA40H1S-R_0")
      (fields
        (field (name "DIGIKEY_PART_NUMBER") "490-MA40H1S-RCT-ND")
        (field (name "MF") "Murata")
        (field (name "MOUSER_PART_NUMBER") "81-MA40H1S-R")
      )
      (libsource (lib "eagle-import") (part "MURATA_MA40H1S-RMURATA_MA40H1S-R_0_0"))
    )
    (comp (ref "U138")
      (value "MURATA_MA40H1S-RMURATA_MA40H1S-R_0_0")
      (footprint "eagle-import:MURATA_MA40H1S-R_0")
      (fields
        (field (name "DIGIKEY_PART_NUMBER") "490-MA40H1S-RCT-ND")
        (field (name "MF") "Murata")
        (field (name "MOUSER_PART_NUMBER") "81-MA40H1S-R")
      )
      (libsource (lib "eagle-import") (part "MURATA_MA40H1S-RMURATA_MA40H1S-R_0_0"))
    )
    (comp (ref "U139")
      (value "MURATA_MA40H1S-RMURATA_MA40H1S-R_0_0")
      (footprint "eagle-import:MURATA_MA40H1S-R_0")
      (fields
        (field (name "DIGIKEY_PART_NUMBER") "490-MA40H1S-RCT-ND")
        (field (name "MF") "Murata")
        (field (name "MOUSER_PART_NUMBER") "81-MA40H1S-R")
      )
      (libsource (lib "eagle-import") (part "MURATA_MA40H1S-RMURATA_MA40H1S-R_0_0"))
    )
    (comp (ref "U140")
      (value "MURATA_MA40H1S-RMURATA_MA40H1S-R_0_0")
      (footprint "eagle-import:MURATA_MA40H1S-R_0")
      (fields
        (field (name "DIGIKEY_PART_NUMBER") "490-MA40H1S-RCT-ND")
        (field (name "MF") "Murata")
        (field (name "MOUSER_PART_NUMBER") "81-MA40H1S-R")
      )
      (libsource (lib "eagle-import") (part "MURATA_MA40H1S-RMURATA_MA40H1S-R_0_0"))
    )
    (comp (ref "U141")
      (value "MURATA_MA40H1S-RMURATA_MA40H1S-R_0_0")
      (footprint "eagle-import:MURATA_MA40H1S-R_0")
      (fields
        (field (name "DIGIKEY_PART_NUMBER") "490-MA40H1S-RCT-ND")
        (field (name "MF") "Murata")
        (field (name "MOUSER_PART_NUMBER") "81-MA40H1S-R")
      )
      (libsource (lib "eagle-import") (part "MURATA_MA40H1S-RMURATA_MA40H1S-R_0_0"))
    )
    (comp (ref "U142")
      (value "MURATA_MA40H1S-RMURATA_MA40H1S-R_0_0")
      (footprint "eagle-import:MURATA_MA40H1S-R_0")
      (fields
        (field (name "DIGIKEY_PART_NUMBER") "490-MA40H1S-RCT-ND")
        (field (name "MF") "Murata")
        (field (name "MOUSER_PART_NUMBER") "81-MA40H1S-R")
      )
      (libsource (lib "eagle-import") (part "MURATA_MA40H1S-RMURATA_MA40H1S-R_0_0"))
    )
    (comp (ref "U143")
      (value "MURATA_MA40H1S-RMURATA_MA40H1S-R_0_0")
      (footprint "eagle-import:MURATA_MA40H1S-R_0")
      (fields
        (field (name "DIGIKEY_PART_NUMBER") "490-MA40H1S-RCT-ND")
        (field (name "MF") "Murata")
        (field (name "MOUSER_PART_NUMBER") "81-MA40H1S-R")
      )
      (libsource (lib "eagle-import") (part "MURATA_MA40H1S-RMURATA_MA40H1S-R_0_0"))
    )
    (comp (ref "U144")
      (value "MURATA_MA40H1S-RMURATA_MA40H1S-R_0_0")
      (footprint "eagle-import:MURATA_MA40H1S-R_0")
      (fields
        (field (name "DIGIKEY_PART_NUMBER") "490-MA40H1S-RCT-ND")
        (field (name "MF") "Murata")
        (field (name "MOUSER_PART_NUMBER") "81-MA40H1S-R")
      )
      (libsource (lib "eagle-import") (part "MURATA_MA40H1S-RMURATA_MA40H1S-R_0_0"))
    )
    (comp (ref "U145")
      (value "MURATA_MA40H1S-RMURATA_MA40H1S-R_0_0")
      (footprint "eagle-import:MURATA_MA40H1S-R_0")
      (fields
        (field (name "DIGIKEY_PART_NUMBER") "490-MA40H1S-RCT-ND")
        (field (name "MF") "Murata")
        (field (name "MOUSER_PART_NUMBER") "81-MA40H1S-R")
      )
      (libsource (lib "eagle-import") (part "MURATA_MA40H1S-RMURATA_MA40H1S-R_0_0"))
    )
    (comp (ref "U146")
      (value "MURATA_MA40H1S-RMURATA_MA40H1S-R_0_0")
      (footprint "eagle-import:MURATA_MA40H1S-R_0")
      (fields
        (field (name "DIGIKEY_PART_NUMBER") "490-MA40H1S-RCT-ND")
        (field (name "MF") "Murata")
        (field (name "MOUSER_PART_NUMBER") "81-MA40H1S-R")
      )
      (libsource (lib "eagle-import") (part "MURATA_MA40H1S-RMURATA_MA40H1S-R_0_0"))
    )
    (comp (ref "U147")
      (value "MURATA_MA40H1S-RMURATA_MA40H1S-R_0_0")
      (footprint "eagle-import:MURATA_MA40H1S-R_0")
      (fields
        (field (name "DIGIKEY_PART_NUMBER") "490-MA40H1S-RCT-ND")
        (field (name "MF") "Murata")
        (field (name "MOUSER_PART_NUMBER") "81-MA40H1S-R")
      )
      (libsource (lib "eagle-import") (part "MURATA_MA40H1S-RMURATA_MA40H1S-R_0_0"))
    )
    (comp (ref "U148")
      (value "MURATA_MA40H1S-RMURATA_MA40H1S-R_0_0")
      (footprint "eagle-import:MURATA_MA40H1S-R_0")
      (fields
        (field (name "DIGIKEY_PART_NUMBER") "490-MA40H1S-RCT-ND")
        (field (name "MF") "Murata")
        (field (name "MOUSER_PART_NUMBER") "81-MA40H1S-R")
      )
      (libsource (lib "eagle-import") (part "MURATA_MA40H1S-RMURATA_MA40H1S-R_0_0"))
    )
    (comp (ref "U149")
      (value "MURATA_MA40H1S-RMURATA_MA40H1S-R_0_0")
      (footprint "eagle-import:MURATA_MA40H1S-R_0")
      (fields
        (field (name "DIGIKEY_PART_NUMBER") "490-MA40H1S-RCT-ND")
        (field (name "MF") "Murata")
        (field (name "MOUSER_PART_NUMBER") "81-MA40H1S-R")
      )
      (libsource (lib "eagle-import") (part "MURATA_MA40H1S-RMURATA_MA40H1S-R_0_0"))
    )
    (comp (ref "U150")
      (value "MURATA_MA40H1S-RMURATA_MA40H1S-R_0_0")
      (footprint "eagle-import:MURATA_MA40H1S-R_0")
      (fields
        (field (name "DIGIKEY_PART_NUMBER") "490-MA40H1S-RCT-ND")
        (field (name "MF") "Murata")
        (field (name "MOUSER_PART_NUMBER") "81-MA40H1S-R")
      )
      (libsource (lib "eagle-import") (part "MURATA_MA40H1S-RMURATA_MA40H1S-R_0_0"))
    )
    (comp (ref "U151")
      (value "MURATA_MA40H1S-RMURATA_MA40H1S-R_0_0")
      (footprint "eagle-import:MURATA_MA40H1S-R_0")
      (fields
        (field (name "DIGIKEY_PART_NUMBER") "490-MA40H1S-RCT-ND")
        (field (name "MF") "Murata")
        (field (name "MOUSER_PART_NUMBER") "81-MA40H1S-R")
      )
      (libsource (lib "eagle-import") (part "MURATA_MA40H1S-RMURATA_MA40H1S-R_0_0"))
    )
    (comp (ref "U152")
      (value "MURATA_MA40H1S-RMURATA_MA40H1S-R_0_0")
      (footprint "eagle-import:MURATA_MA40H1S-R_0")
      (fields
        (field (name "DIGIKEY_PART_NUMBER") "490-MA40H1S-RCT-ND")
        (field (name "MF") "Murata")
        (field (name "MOUSER_PART_NUMBER") "81-MA40H1S-R")
      )
      (libsource (lib "eagle-import") (part "MURATA_MA40H1S-RMURATA_MA40H1S-R_0_0"))
    )
    (comp (ref "U153")
      (value "MURATA_MA40H1S-RMURATA_MA40H1S-R_0_0")
      (footprint "eagle-import:MURATA_MA40H1S-R_0")
      (fields
        (field (name "DIGIKEY_PART_NUMBER") "490-MA40H1S-RCT-ND")
        (field (name "MF") "Murata")
        (field (name "MOUSER_PART_NUMBER") "81-MA40H1S-R")
      )
      (libsource (lib "eagle-import") (part "MURATA_MA40H1S-RMURATA_MA40H1S-R_0_0"))
    )
    (comp (ref "U154")
      (value "MURATA_MA40H1S-RMURATA_MA40H1S-R_0_0")
      (footprint "eagle-import:MURATA_MA40H1S-R_0")
      (fields
        (field (name "DIGIKEY_PART_NUMBER") "490-MA40H1S-RCT-ND")
        (field (name "MF") "Murata")
        (field (name "MOUSER_PART_NUMBER") "81-MA40H1S-R")
      )
      (libsource (lib "eagle-import") (part "MURATA_MA40H1S-RMURATA_MA40H1S-R_0_0"))
    )
    (comp (ref "U155")
      (value "MURATA_MA40H1S-RMURATA_MA40H1S-R_0_0")
      (footprint "eagle-import:MURATA_MA40H1S-R_0")
      (fields
        (field (name "DIGIKEY_PART_NUMBER") "490-MA40H1S-RCT-ND")
        (field (name "MF") "Murata")
        (field (name "MOUSER_PART_NUMBER") "81-MA40H1S-R")
      )
      (libsource (lib "eagle-import") (part "MURATA_MA40H1S-RMURATA_MA40H1S-R_0_0"))
    )
    (comp (ref "U156")
      (value "MURATA_MA40H1S-RMURATA_MA40H1S-R_0_0")
      (footprint "eagle-import:MURATA_MA40H1S-R_0")
      (fields
        (field (name "DIGIKEY_PART_NUMBER") "490-MA40H1S-RCT-ND")
        (field (name "MF") "Murata")
        (field (name "MOUSER_PART_NUMBER") "81-MA40H1S-R")
      )
      (libsource (lib "eagle-import") (part "MURATA_MA40H1S-RMURATA_MA40H1S-R_0_0"))
    )
    (comp (ref "U157")
      (value "MURATA_MA40H1S-RMURATA_MA40H1S-R_0_0")
      (footprint "eagle-import:MURATA_MA40H1S-R_0")
      (fields
        (field (name "DIGIKEY_PART_NUMBER") "490-MA40H1S-RCT-ND")
        (field (name "MF") "Murata")
        (field (name "MOUSER_PART_NUMBER") "81-MA40H1S-R")
      )
      (libsource (lib "eagle-import") (part "MURATA_MA40H1S-RMURATA_MA40H1S-R_0_0"))
    )
    (comp (ref "U158")
      (value "MURATA_MA40H1S-RMURATA_MA40H1S-R_0_0")
      (footprint "eagle-import:MURATA_MA40H1S-R_0")
      (fields
        (field (name "DIGIKEY_PART_NUMBER") "490-MA40H1S-RCT-ND")
        (field (name "MF") "Murata")
        (field (name "MOUSER_PART_NUMBER") "81-MA40H1S-R")
      )
      (libsource (lib "eagle-import") (part "MURATA_MA40H1S-RMURATA_MA40H1S-R_0_0"))
    )
    (comp (ref "U159")
      (value "MURATA_MA40H1S-RMURATA_MA40H1S-R_0_0")
      (footprint "eagle-import:MURATA_MA40H1S-R_0")
      (fields
        (field (name "DIGIKEY_PART_NUMBER") "490-MA40H1S-RCT-ND")
        (field (name "MF") "Murata")
        (field (name "MOUSER_PART_NUMBER") "81-MA40H1S-R")
      )
      (libsource (lib "eagle-import") (part "MURATA_MA40H1S-RMURATA_MA40H1S-R_0_0"))
    )
    (comp (ref "U160")
      (value "MURATA_MA40H1S-RMURATA_MA40H1S-R_0_0")
      (footprint "eagle-import:MURATA_MA40H1S-R_0")
      (fields
        (field (name "DIGIKEY_PART_NUMBER") "490-MA40H1S-RCT-ND")
        (field (name "MF") "Murata")
        (field (name "MOUSER_PART_NUMBER") "81-MA40H1S-R")
      )
      (libsource (lib "eagle-import") (part "MURATA_MA40H1S-RMURATA_MA40H1S-R_0_0"))
    )
    (comp (ref "U161")
      (value "MURATA_MA40H1S-RMURATA_MA40H1S-R_0_0")
      (footprint "eagle-import:MURATA_MA40H1S-R_0")
      (fields
        (field (name "DIGIKEY_PART_NUMBER") "490-MA40H1S-RCT-ND")
        (field (name "MF") "Murata")
        (field (name "MOUSER_PART_NUMBER") "81-MA40H1S-R")
      )
      (libsource (lib "eagle-import") (part "MURATA_MA40H1S-RMURATA_MA40H1S-R_0_0"))
    )
    (comp (ref "U162")
      (value "MURATA_MA40H1S-RMURATA_MA40H1S-R_0_0")
      (footprint "eagle-import:MURATA_MA40H1S-R_0")
      (fields
        (field (name "DIGIKEY_PART_NUMBER") "490-MA40H1S-RCT-ND")
        (field (name "MF") "Murata")
        (field (name "MOUSER_PART_NUMBER") "81-MA40H1S-R")
      )
      (libsource (lib "eagle-import") (part "MURATA_MA40H1S-RMURATA_MA40H1S-R_0_0"))
    )
    (comp (ref "U163")
      (value "MURATA_MA40H1S-RMURATA_MA40H1S-R_0_0")
      (footprint "eagle-import:MURATA_MA40H1S-R_0")
      (fields
        (field (name "DIGIKEY_PART_NUMBER") "490-MA40H1S-RCT-ND")
        (field (name "MF") "Murata")
        (field (name "MOUSER_PART_NUMBER") "81-MA40H1S-R")
      )
      (libsource (lib "eagle-import") (part "MURATA_MA40H1S-RMURATA_MA40H1S-R_0_0"))
    )
    (comp (ref "U164")
      (value "MURATA_MA40H1S-RMURATA_MA40H1S-R_0_0")
      (footprint "eagle-import:MURATA_MA40H1S-R_0")
      (fields
        (field (name "DIGIKEY_PART_NUMBER") "490-MA40H1S-RCT-ND")
        (field (name "MF") "Murata")
        (field (name "MOUSER_PART_NUMBER") "81-MA40H1S-R")
      )
      (libsource (lib "eagle-import") (part "MURATA_MA40H1S-RMURATA_MA40H1S-R_0_0"))
    )
    (comp (ref "U165")
      (value "MURATA_MA40H1S-RMURATA_MA40H1S-R_0_0")
      (footprint "eagle-import:MURATA_MA40H1S-R_0")
      (fields
        (field (name "DIGIKEY_PART_NUMBER") "490-MA40H1S-RCT-ND")
        (field (name "MF") "Murata")
        (field (name "MOUSER_PART_NUMBER") "81-MA40H1S-R")
      )
      (libsource (lib "eagle-import") (part "MURATA_MA40H1S-RMURATA_MA40H1S-R_0_0"))
    )
    (comp (ref "U166")
      (value "MURATA_MA40H1S-RMURATA_MA40H1S-R_0_0")
      (footprint "eagle-import:MURATA_MA40H1S-R_0")
      (fields
        (field (name "DIGIKEY_PART_NUMBER") "490-MA40H1S-RCT-ND")
        (field (name "MF") "Murata")
        (field (name "MOUSER_PART_NUMBER") "81-MA40H1S-R")
      )
      (libsource (lib "eagle-import") (part "MURATA_MA40H1S-RMURATA_MA40H1S-R_0_0"))
    )
    (comp (ref "U167")
      (value "MURATA_MA40H1S-RMURATA_MA40H1S-R_0_0")
      (footprint "eagle-import:MURATA_MA40H1S-R_0")
      (fields
        (field (name "DIGIKEY_PART_NUMBER") "490-MA40H1S-RCT-ND")
        (field (name "MF") "Murata")
        (field (name "MOUSER_PART_NUMBER") "81-MA40H1S-R")
      )
      (libsource (lib "eagle-import") (part "MURATA_MA40H1S-RMURATA_MA40H1S-R_0_0"))
    )
    (comp (ref "U168")
      (value "MURATA_MA40H1S-RMURATA_MA40H1S-R_0_0")
      (footprint "eagle-import:MURATA_MA40H1S-R_0")
      (fields
        (field (name "DIGIKEY_PART_NUMBER") "490-MA40H1S-RCT-ND")
        (field (name "MF") "Murata")
        (field (name "MOUSER_PART_NUMBER") "81-MA40H1S-R")
      )
      (libsource (lib "eagle-import") (part "MURATA_MA40H1S-RMURATA_MA40H1S-R_0_0"))
    )
    (comp (ref "U169")
      (value "MURATA_MA40H1S-RMURATA_MA40H1S-R_0_0")
      (footprint "eagle-import:MURATA_MA40H1S-R_0")
      (fields
        (field (name "DIGIKEY_PART_NUMBER") "490-MA40H1S-RCT-ND")
        (field (name "MF") "Murata")
        (field (name "MOUSER_PART_NUMBER") "81-MA40H1S-R")
      )
      (libsource (lib "eagle-import") (part "MURATA_MA40H1S-RMURATA_MA40H1S-R_0_0"))
    )
    (comp (ref "U170")
      (value "MURATA_MA40H1S-RMURATA_MA40H1S-R_0_0")
      (footprint "eagle-import:MURATA_MA40H1S-R_0")
      (fields
        (field (name "DIGIKEY_PART_NUMBER") "490-MA40H1S-RCT-ND")
        (field (name "MF") "Murata")
        (field (name "MOUSER_PART_NUMBER") "81-MA40H1S-R")
      )
      (libsource (lib "eagle-import") (part "MURATA_MA40H1S-RMURATA_MA40H1S-R_0_0"))
    )
    (comp (ref "U171")
      (value "MURATA_MA40H1S-RMURATA_MA40H1S-R_0_0")
      (footprint "eagle-import:MURATA_MA40H1S-R_0")
      (fields
        (field (name "DIGIKEY_PART_NUMBER") "490-MA40H1S-RCT-ND")
        (field (name "MF") "Murata")
        (field (name "MOUSER_PART_NUMBER") "81-MA40H1S-R")
      )
      (libsource (lib "eagle-import") (part "MURATA_MA40H1S-RMURATA_MA40H1S-R_0_0"))
    )
    (comp (ref "U172")
      (value "MURATA_MA40H1S-RMURATA_MA40H1S-R_0_0")
      (footprint "eagle-import:MURATA_MA40H1S-R_0")
      (fields
        (field (name "DIGIKEY_PART_NUMBER") "490-MA40H1S-RCT-ND")
        (field (name "MF") "Murata")
        (field (name "MOUSER_PART_NUMBER") "81-MA40H1S-R")
      )
      (libsource (lib "eagle-import") (part "MURATA_MA40H1S-RMURATA_MA40H1S-R_0_0"))
    )
    (comp (ref "U173")
      (value "MURATA_MA40H1S-RMURATA_MA40H1S-R_0_0")
      (footprint "eagle-import:MURATA_MA40H1S-R_0")
      (fields
        (field (name "DIGIKEY_PART_NUMBER") "490-MA40H1S-RCT-ND")
        (field (name "MF") "Murata")
        (field (name "MOUSER_PART_NUMBER") "81-MA40H1S-R")
      )
      (libsource (lib "eagle-import") (part "MURATA_MA40H1S-RMURATA_MA40H1S-R_0_0"))
    )
    (comp (ref "U174")
      (value "MURATA_MA40H1S-RMURATA_MA40H1S-R_0_0")
      (footprint "eagle-import:MURATA_MA40H1S-R_0")
      (fields
        (field (name "DIGIKEY_PART_NUMBER") "490-MA40H1S-RCT-ND")
        (field (name "MF") "Murata")
        (field (name "MOUSER_PART_NUMBER") "81-MA40H1S-R")
      )
      (libsource (lib "eagle-import") (part "MURATA_MA40H1S-RMURATA_MA40H1S-R_0_0"))
    )
    (comp (ref "U175")
      (value "MURATA_MA40H1S-RMURATA_MA40H1S-R_0_0")
      (footprint "eagle-import:MURATA_MA40H1S-R_0")
      (fields
        (field (name "DIGIKEY_PART_NUMBER") "490-MA40H1S-RCT-ND")
        (field (name "MF") "Murata")
        (field (name "MOUSER_PART_NUMBER") "81-MA40H1S-R")
      )
      (libsource (lib "eagle-import") (part "MURATA_MA40H1S-RMURATA_MA40H1S-R_0_0"))
    )
    (comp (ref "U176")
      (value "MURATA_MA40H1S-RMURATA_MA40H1S-R_0_0")
      (footprint "eagle-import:MURATA_MA40H1S-R_0")
      (fields
        (field (name "DIGIKEY_PART_NUMBER") "490-MA40H1S-RCT-ND")
        (field (name "MF") "Murata")
        (field (name "MOUSER_PART_NUMBER") "81-MA40H1S-R")
      )
      (libsource (lib "eagle-import") (part "MURATA_MA40H1S-RMURATA_MA40H1S-R_0_0"))
    )
    (comp (ref "U177")
      (value "MURATA_MA40H1S-RMURATA_MA40H1S-R_0_0")
      (footprint "eagle-import:MURATA_MA40H1S-R_0")
      (fields
        (field (name "DIGIKEY_PART_NUMBER") "490-MA40H1S-RCT-ND")
        (field (name "MF") "Murata")
        (field (name "MOUSER_PART_NUMBER") "81-MA40H1S-R")
      )
      (libsource (lib "eagle-import") (part "MURATA_MA40H1S-RMURATA_MA40H1S-R_0_0"))
    )
    (comp (ref "U178")
      (value "MURATA_MA40H1S-RMURATA_MA40H1S-R_0_0")
      (footprint "eagle-import:MURATA_MA40H1S-R_0")
      (fields
        (field (name "DIGIKEY_PART_NUMBER") "490-MA40H1S-RCT-ND")
        (field (name "MF") "Murata")
        (field (name "MOUSER_PART_NUMBER") "81-MA40H1S-R")
      )
      (libsource (lib "eagle-import") (part "MURATA_MA40H1S-RMURATA_MA40H1S-R_0_0"))
    )
    (comp (ref "U179")
      (value "MURATA_MA40H1S-RMURATA_MA40H1S-R_0_0")
      (footprint "eagle-import:MURATA_MA40H1S-R_0")
      (fields
        (field (name "DIGIKEY_PART_NUMBER") "490-MA40H1S-RCT-ND")
        (field (name "MF") "Murata")
        (field (name "MOUSER_PART_NUMBER") "81-MA40H1S-R")
      )
      (libsource (lib "eagle-import") (part "MURATA_MA40H1S-RMURATA_MA40H1S-R_0_0"))
    )
    (comp (ref "U180")
      (value "MURATA_MA40H1S-RMURATA_MA40H1S-R_0_0")
      (footprint "eagle-import:MURATA_MA40H1S-R_0")
      (fields
        (field (name "DIGIKEY_PART_NUMBER") "490-MA40H1S-RCT-ND")
        (field (name "MF") "Murata")
        (field (name "MOUSER_PART_NUMBER") "81-MA40H1S-R")
      )
      (libsource (lib "eagle-import") (part "MURATA_MA40H1S-RMURATA_MA40H1S-R_0_0"))
    )
    (comp (ref "U184")
      (value "MURATA_MA40H1S-RMURATA_MA40H1S-R_0_0")
      (footprint "eagle-import:MURATA_MA40H1S-R_0")
      (fields
        (field (name "DIGIKEY_PART_NUMBER") "490-MA40H1S-RCT-ND")
        (field (name "MF") "Murata")
        (field (name "MOUSER_PART_NUMBER") "81-MA40H1S-R")
      )
      (libsource (lib "eagle-import") (part "MURATA_MA40H1S-RMURATA_MA40H1S-R_0_0"))
    )
    (comp (ref "U185")
      (value "MURATA_MA40H1S-RMURATA_MA40H1S-R_0_0")
      (footprint "eagle-import:MURATA_MA40H1S-R_0")
      (fields
        (field (name "DIGIKEY_PART_NUMBER") "490-MA40H1S-RCT-ND")
        (field (name "MF") "Murata")
        (field (name "MOUSER_PART_NUMBER") "81-MA40H1S-R")
      )
      (libsource (lib "eagle-import") (part "MURATA_MA40H1S-RMURATA_MA40H1S-R_0_0"))
    )
    (comp (ref "U186")
      (value "MURATA_MA40H1S-RMURATA_MA40H1S-R_0_0")
      (footprint "eagle-import:MURATA_MA40H1S-R_0")
      (fields
        (field (name "DIGIKEY_PART_NUMBER") "490-MA40H1S-RCT-ND")
        (field (name "MF") "Murata")
        (field (name "MOUSER_PART_NUMBER") "81-MA40H1S-R")
      )
      (libsource (lib "eagle-import") (part "MURATA_MA40H1S-RMURATA_MA40H1S-R_0_0"))
    )
    (comp (ref "U192")
      (value "MURATA_MA40H1S-RMURATA_MA40H1S-R_0_0")
      (footprint "eagle-import:MURATA_MA40H1S-R_0")
      (fields
        (field (name "DIGIKEY_PART_NUMBER") "490-MA40H1S-RCT-ND")
        (field (name "MF") "Murata")
        (field (name "MOUSER_PART_NUMBER") "81-MA40H1S-R")
      )
      (libsource (lib "eagle-import") (part "MURATA_MA40H1S-RMURATA_MA40H1S-R_0_0"))
    )
    (comp (ref "U193")
      (value "MURATA_MA40H1S-RMURATA_MA40H1S-R_0_0")
      (footprint "eagle-import:MURATA_MA40H1S-R_0")
      (fields
        (field (name "DIGIKEY_PART_NUMBER") "490-MA40H1S-RCT-ND")
        (field (name "MF") "Murata")
        (field (name "MOUSER_PART_NUMBER") "81-MA40H1S-R")
      )
      (libsource (lib "eagle-import") (part "MURATA_MA40H1S-RMURATA_MA40H1S-R_0_0"))
    )
    (comp (ref "U194")
      (value "MURATA_MA40H1S-RMURATA_MA40H1S-R_0_0")
      (footprint "eagle-import:MURATA_MA40H1S-R_0")
      (fields
        (field (name "DIGIKEY_PART_NUMBER") "490-MA40H1S-RCT-ND")
        (field (name "MF") "Murata")
        (field (name "MOUSER_PART_NUMBER") "81-MA40H1S-R")
      )
      (libsource (lib "eagle-import") (part "MURATA_MA40H1S-RMURATA_MA40H1S-R_0_0"))
    )
    (comp (ref "U195")
      (value "MURATA_MA40H1S-RMURATA_MA40H1S-R_0_0")
      (footprint "eagle-import:MURATA_MA40H1S-R_0")
      (fields
        (field (name "DIGIKEY_PART_NUMBER") "490-MA40H1S-RCT-ND")
        (field (name "MF") "Murata")
        (field (name "MOUSER_PART_NUMBER") "81-MA40H1S-R")
      )
      (libsource (lib "eagle-import") (part "MURATA_MA40H1S-RMURATA_MA40H1S-R_0_0"))
    )
    (comp (ref "U196")
      (value "MURATA_MA40H1S-RMURATA_MA40H1S-R_0_0")
      (footprint "eagle-import:MURATA_MA40H1S-R_0")
      (fields
        (field (name "DIGIKEY_PART_NUMBER") "490-MA40H1S-RCT-ND")
        (field (name "MF") "Murata")
        (field (name "MOUSER_PART_NUMBER") "81-MA40H1S-R")
      )
      (libsource (lib "eagle-import") (part "MURATA_MA40H1S-RMURATA_MA40H1S-R_0_0"))
    )
    (comp (ref "U197")
      (value "MURATA_MA40H1S-RMURATA_MA40H1S-R_0_0")
      (footprint "eagle-import:MURATA_MA40H1S-R_0")
      (fields
        (field (name "DIGIKEY_PART_NUMBER") "490-MA40H1S-RCT-ND")
        (field (name "MF") "Murata")
        (field (name "MOUSER_PART_NUMBER") "81-MA40H1S-R")
      )
      (libsource (lib "eagle-import") (part "MURATA_MA40H1S-RMURATA_MA40H1S-R_0_0"))
    )
    (comp (ref "U198")
      (value "MURATA_MA40H1S-RMURATA_MA40H1S-R_0_0")
      (footprint "eagle-import:MURATA_MA40H1S-R_0")
      (fields
        (field (name "DIGIKEY_PART_NUMBER") "490-MA40H1S-RCT-ND")
        (field (name "MF") "Murata")
        (field (name "MOUSER_PART_NUMBER") "81-MA40H1S-R")
      )
      (libsource (lib "eagle-import") (part "MURATA_MA40H1S-RMURATA_MA40H1S-R_0_0"))
    )
    (comp (ref "U199")
      (value "MURATA_MA40H1S-RMURATA_MA40H1S-R_0_0")
      (footprint "eagle-import:MURATA_MA40H1S-R_0")
      (fields
        (field (name "DIGIKEY_PART_NUMBER") "490-MA40H1S-RCT-ND")
        (field (name "MF") "Murata")
        (field (name "MOUSER_PART_NUMBER") "81-MA40H1S-R")
      )
      (libsource (lib "eagle-import") (part "MURATA_MA40H1S-RMURATA_MA40H1S-R_0_0"))
    )
    (comp (ref "U200")
      (value "MURATA_MA40H1S-RMURATA_MA40H1S-R_0_0")
      (footprint "eagle-import:MURATA_MA40H1S-R_0")
      (fields
        (field (name "DIGIKEY_PART_NUMBER") "490-MA40H1S-RCT-ND")
        (field (name "MF") "Murata")
        (field (name "MOUSER_PART_NUMBER") "81-MA40H1S-R")
      )
      (libsource (lib "eagle-import") (part "MURATA_MA40H1S-RMURATA_MA40H1S-R_0_0"))
    )
    (comp (ref "U201")
      (value "MURATA_MA40H1S-RMURATA_MA40H1S-R_0_0")
      (footprint "eagle-import:MURATA_MA40H1S-R_0")
      (fields
        (field (name "DIGIKEY_PART_NUMBER") "490-MA40H1S-RCT-ND")
        (field (name "MF") "Murata")
        (field (name "MOUSER_PART_NUMBER") "81-MA40H1S-R")
      )
      (libsource (lib "eagle-import") (part "MURATA_MA40H1S-RMURATA_MA40H1S-R_0_0"))
    )
    (comp (ref "U202")
      (value "MURATA_MA40H1S-RMURATA_MA40H1S-R_0_0")
      (footprint "eagle-import:MURATA_MA40H1S-R_0")
      (fields
        (field (name "DIGIKEY_PART_NUMBER") "490-MA40H1S-RCT-ND")
        (field (name "MF") "Murata")
        (field (name "MOUSER_PART_NUMBER") "81-MA40H1S-R")
      )
      (libsource (lib "eagle-import") (part "MURATA_MA40H1S-RMURATA_MA40H1S-R_0_0"))
    )
    (comp (ref "U203")
      (value "MURATA_MA40H1S-RMURATA_MA40H1S-R_0_0")
      (footprint "eagle-import:MURATA_MA40H1S-R_0")
      (fields
        (field (name "DIGIKEY_PART_NUMBER") "490-MA40H1S-RCT-ND")
        (field (name "MF") "Murata")
        (field (name "MOUSER_PART_NUMBER") "81-MA40H1S-R")
      )
      (libsource (lib "eagle-import") (part "MURATA_MA40H1S-RMURATA_MA40H1S-R_0_0"))
    )
    (comp (ref "U204")
      (value "MURATA_MA40H1S-RMURATA_MA40H1S-R_0_0")
      (footprint "eagle-import:MURATA_MA40H1S-R_0")
      (fields
        (field (name "DIGIKEY_PART_NUMBER") "490-MA40H1S-RCT-ND")
        (field (name "MF") "Murata")
        (field (name "MOUSER_PART_NUMBER") "81-MA40H1S-R")
      )
      (libsource (lib "eagle-import") (part "MURATA_MA40H1S-RMURATA_MA40H1S-R_0_0"))
    )
    (comp (ref "U205")
      (value "MURATA_MA40H1S-RMURATA_MA40H1S-R_0_0")
      (footprint "eagle-import:MURATA_MA40H1S-R_0")
      (fields
        (field (name "DIGIKEY_PART_NUMBER") "490-MA40H1S-RCT-ND")
        (field (name "MF") "Murata")
        (field (name "MOUSER_PART_NUMBER") "81-MA40H1S-R")
      )
      (libsource (lib "eagle-import") (part "MURATA_MA40H1S-RMURATA_MA40H1S-R_0_0"))
    )
    (comp (ref "U206")
      (value "MURATA_MA40H1S-RMURATA_MA40H1S-R_0_0")
      (footprint "eagle-import:MURATA_MA40H1S-R_0")
      (fields
        (field (name "DIGIKEY_PART_NUMBER") "490-MA40H1S-RCT-ND")
        (field (name "MF") "Murata")
        (field (name "MOUSER_PART_NUMBER") "81-MA40H1S-R")
      )
      (libsource (lib "eagle-import") (part "MURATA_MA40H1S-RMURATA_MA40H1S-R_0_0"))
    )
    (comp (ref "U207")
      (value "MURATA_MA40H1S-RMURATA_MA40H1S-R_0_0")
      (footprint "eagle-import:MURATA_MA40H1S-R_0")
      (fields
        (field (name "DIGIKEY_PART_NUMBER") "490-MA40H1S-RCT-ND")
        (field (name "MF") "Murata")
        (field (name "MOUSER_PART_NUMBER") "81-MA40H1S-R")
      )
      (libsource (lib "eagle-import") (part "MURATA_MA40H1S-RMURATA_MA40H1S-R_0_0"))
    )
    (comp (ref "U208")
      (value "MURATA_MA40H1S-RMURATA_MA40H1S-R_0_0")
      (footprint "eagle-import:MURATA_MA40H1S-R_0")
      (fields
        (field (name "DIGIKEY_PART_NUMBER") "490-MA40H1S-RCT-ND")
        (field (name "MF") "Murata")
        (field (name "MOUSER_PART_NUMBER") "81-MA40H1S-R")
      )
      (libsource (lib "eagle-import") (part "MURATA_MA40H1S-RMURATA_MA40H1S-R_0_0"))
    )
    (comp (ref "U209")
      (value "MURATA_MA40H1S-RMURATA_MA40H1S-R_0_0")
      (footprint "eagle-import:MURATA_MA40H1S-R_0")
      (fields
        (field (name "DIGIKEY_PART_NUMBER") "490-MA40H1S-RCT-ND")
        (field (name "MF") "Murata")
        (field (name "MOUSER_PART_NUMBER") "81-MA40H1S-R")
      )
      (libsource (lib "eagle-import") (part "MURATA_MA40H1S-RMURATA_MA40H1S-R_0_0"))
    )
    (comp (ref "U210")
      (value "MURATA_MA40H1S-RMURATA_MA40H1S-R_0_0")
      (footprint "eagle-import:MURATA_MA40H1S-R_0")
      (fields
        (field (name "DIGIKEY_PART_NUMBER") "490-MA40H1S-RCT-ND")
        (field (name "MF") "Murata")
        (field (name "MOUSER_PART_NUMBER") "81-MA40H1S-R")
      )
      (libsource (lib "eagle-import") (part "MURATA_MA40H1S-RMURATA_MA40H1S-R_0_0"))
    )
    (comp (ref "U211")
      (value "MURATA_MA40H1S-RMURATA_MA40H1S-R_0_0")
      (footprint "eagle-import:MURATA_MA40H1S-R_0")
      (fields
        (field (name "DIGIKEY_PART_NUMBER") "490-MA40H1S-RCT-ND")
        (field (name "MF") "Murata")
        (field (name "MOUSER_PART_NUMBER") "81-MA40H1S-R")
      )
      (libsource (lib "eagle-import") (part "MURATA_MA40H1S-RMURATA_MA40H1S-R_0_0"))
    )
    (comp (ref "U212")
      (value "MURATA_MA40H1S-RMURATA_MA40H1S-R_0_0")
      (footprint "eagle-import:MURATA_MA40H1S-R_0")
      (fields
        (field (name "DIGIKEY_PART_NUMBER") "490-MA40H1S-RCT-ND")
        (field (name "MF") "Murata")
        (field (name "MOUSER_PART_NUMBER") "81-MA40H1S-R")
      )
      (libsource (lib "eagle-import") (part "MURATA_MA40H1S-RMURATA_MA40H1S-R_0_0"))
    )
    (comp (ref "U213")
      (value "MURATA_MA40H1S-RMURATA_MA40H1S-R_0_0")
      (footprint "eagle-import:MURATA_MA40H1S-R_0")
      (fields
        (field (name "DIGIKEY_PART_NUMBER") "490-MA40H1S-RCT-ND")
        (field (name "MF") "Murata")
        (field (name "MOUSER_PART_NUMBER") "81-MA40H1S-R")
      )
      (libsource (lib "eagle-import") (part "MURATA_MA40H1S-RMURATA_MA40H1S-R_0_0"))
    )
    (comp (ref "U214")
      (value "MURATA_MA40H1S-RMURATA_MA40H1S-R_0_0")
      (footprint "eagle-import:MURATA_MA40H1S-R_0")
      (fields
        (field (name "DIGIKEY_PART_NUMBER") "490-MA40H1S-RCT-ND")
        (field (name "MF") "Murata")
        (field (name "MOUSER_PART_NUMBER") "81-MA40H1S-R")
      )
      (libsource (lib "eagle-import") (part "MURATA_MA40H1S-RMURATA_MA40H1S-R_0_0"))
    )
    (comp (ref "U215")
      (value "MURATA_MA40H1S-RMURATA_MA40H1S-R_0_0")
      (footprint "eagle-import:MURATA_MA40H1S-R_0")
      (fields
        (field (name "DIGIKEY_PART_NUMBER") "490-MA40H1S-RCT-ND")
        (field (name "MF") "Murata")
        (field (name "MOUSER_PART_NUMBER") "81-MA40H1S-R")
      )
      (libsource (lib "eagle-import") (part "MURATA_MA40H1S-RMURATA_MA40H1S-R_0_0"))
    )
    (comp (ref "U216")
      (value "MURATA_MA40H1S-RMURATA_MA40H1S-R_0_0")
      (footprint "eagle-import:MURATA_MA40H1S-R_0")
      (fields
        (field (name "DIGIKEY_PART_NUMBER") "490-MA40H1S-RCT-ND")
        (field (name "MF") "Murata")
        (field (name "MOUSER_PART_NUMBER") "81-MA40H1S-R")
      )
      (libsource (lib "eagle-import") (part "MURATA_MA40H1S-RMURATA_MA40H1S-R_0_0"))
    )
    (comp (ref "U217")
      (value "MURATA_MA40H1S-RMURATA_MA40H1S-R_0_0")
      (footprint "eagle-import:MURATA_MA40H1S-R_0")
      (fields
        (field (name "DIGIKEY_PART_NUMBER") "490-MA40H1S-RCT-ND")
        (field (name "MF") "Murata")
        (field (name "MOUSER_PART_NUMBER") "81-MA40H1S-R")
      )
      (libsource (lib "eagle-import") (part "MURATA_MA40H1S-RMURATA_MA40H1S-R_0_0"))
    )
    (comp (ref "U218")
      (value "MURATA_MA40H1S-RMURATA_MA40H1S-R_0_0")
      (footprint "eagle-import:MURATA_MA40H1S-R_0")
      (fields
        (field (name "DIGIKEY_PART_NUMBER") "490-MA40H1S-RCT-ND")
        (field (name "MF") "Murata")
        (field (name "MOUSER_PART_NUMBER") "81-MA40H1S-R")
      )
      (libsource (lib "eagle-import") (part "MURATA_MA40H1S-RMURATA_MA40H1S-R_0_0"))
    )
    (comp (ref "U219")
      (value "MURATA_MA40H1S-RMURATA_MA40H1S-R_0_0")
      (footprint "eagle-import:MURATA_MA40H1S-R_0")
      (fields
        (field (name "DIGIKEY_PART_NUMBER") "490-MA40H1S-RCT-ND")
        (field (name "MF") "Murata")
        (field (name "MOUSER_PART_NUMBER") "81-MA40H1S-R")
      )
      (libsource (lib "eagle-import") (part "MURATA_MA40H1S-RMURATA_MA40H1S-R_0_0"))
    )
    (comp (ref "U220")
      (value "MURATA_MA40H1S-RMURATA_MA40H1S-R_0_0")
      (footprint "eagle-import:MURATA_MA40H1S-R_0")
      (fields
        (field (name "DIGIKEY_PART_NUMBER") "490-MA40H1S-RCT-ND")
        (field (name "MF") "Murata")
        (field (name "MOUSER_PART_NUMBER") "81-MA40H1S-R")
      )
      (libsource (lib "eagle-import") (part "MURATA_MA40H1S-RMURATA_MA40H1S-R_0_0"))
    )
    (comp (ref "U221")
      (value "MURATA_MA40H1S-RMURATA_MA40H1S-R_0_0")
      (footprint "eagle-import:MURATA_MA40H1S-R_0")
      (fields
        (field (name "DIGIKEY_PART_NUMBER") "490-MA40H1S-RCT-ND")
        (field (name "MF") "Murata")
        (field (name "MOUSER_PART_NUMBER") "81-MA40H1S-R")
      )
      (libsource (lib "eagle-import") (part "MURATA_MA40H1S-RMURATA_MA40H1S-R_0_0"))
    )
    (comp (ref "U222")
      (value "MURATA_MA40H1S-RMURATA_MA40H1S-R_0_0")
      (footprint "eagle-import:MURATA_MA40H1S-R_0")
      (fields
        (field (name "DIGIKEY_PART_NUMBER") "490-MA40H1S-RCT-ND")
        (field (name "MF") "Murata")
        (field (name "MOUSER_PART_NUMBER") "81-MA40H1S-R")
      )
      (libsource (lib "eagle-import") (part "MURATA_MA40H1S-RMURATA_MA40H1S-R_0_0"))
    )
    (comp (ref "U223")
      (value "MURATA_MA40H1S-RMURATA_MA40H1S-R_0_0")
      (footprint "eagle-import:MURATA_MA40H1S-R_0")
      (fields
        (field (name "DIGIKEY_PART_NUMBER") "490-MA40H1S-RCT-ND")
        (field (name "MF") "Murata")
        (field (name "MOUSER_PART_NUMBER") "81-MA40H1S-R")
      )
      (libsource (lib "eagle-import") (part "MURATA_MA40H1S-RMURATA_MA40H1S-R_0_0"))
    )
    (comp (ref "U224")
      (value "MURATA_MA40H1S-RMURATA_MA40H1S-R_0_0")
      (footprint "eagle-import:MURATA_MA40H1S-R_0")
      (fields
        (field (name "DIGIKEY_PART_NUMBER") "490-MA40H1S-RCT-ND")
        (field (name "MF") "Murata")
        (field (name "MOUSER_PART_NUMBER") "81-MA40H1S-R")
      )
      (libsource (lib "eagle-import") (part "MURATA_MA40H1S-RMURATA_MA40H1S-R_0_0"))
    )
    (comp (ref "U225")
      (value "MURATA_MA40H1S-RMURATA_MA40H1S-R_0_0")
      (footprint "eagle-import:MURATA_MA40H1S-R_0")
      (fields
        (field (name "DIGIKEY_PART_NUMBER") "490-MA40H1S-RCT-ND")
        (field (name "MF") "Murata")
        (field (name "MOUSER_PART_NUMBER") "81-MA40H1S-R")
      )
      (libsource (lib "eagle-import") (part "MURATA_MA40H1S-RMURATA_MA40H1S-R_0_0"))
    )
    (comp (ref "U226")
      (value "MURATA_MA40H1S-RMURATA_MA40H1S-R_0_0")
      (footprint "eagle-import:MURATA_MA40H1S-R_0")
      (fields
        (field (name "DIGIKEY_PART_NUMBER") "490-MA40H1S-RCT-ND")
        (field (name "MF") "Murata")
        (field (name "MOUSER_PART_NUMBER") "81-MA40H1S-R")
      )
      (libsource (lib "eagle-import") (part "MURATA_MA40H1S-RMURATA_MA40H1S-R_0_0"))
    )
    (comp (ref "U227")
      (value "MURATA_MA40H1S-RMURATA_MA40H1S-R_0_0")
      (footprint "eagle-import:MURATA_MA40H1S-R_0")
      (fields
        (field (name "DIGIKEY_PART_NUMBER") "490-MA40H1S-RCT-ND")
        (field (name "MF") "Murata")
        (field (name "MOUSER_PART_NUMBER") "81-MA40H1S-R")
      )
      (libsource (lib "eagle-import") (part "MURATA_MA40H1S-RMURATA_MA40H1S-R_0_0"))
    )
    (comp (ref "U228")
      (value "MURATA_MA40H1S-RMURATA_MA40H1S-R_0_0")
      (footprint "eagle-import:MURATA_MA40H1S-R_0")
      (fields
        (field (name "DIGIKEY_PART_NUMBER") "490-MA40H1S-RCT-ND")
        (field (name "MF") "Murata")
        (field (name "MOUSER_PART_NUMBER") "81-MA40H1S-R")
      )
      (libsource (lib "eagle-import") (part "MURATA_MA40H1S-RMURATA_MA40H1S-R_0_0"))
    )
    (comp (ref "U229")
      (value "MURATA_MA40H1S-RMURATA_MA40H1S-R_0_0")
      (footprint "eagle-import:MURATA_MA40H1S-R_0")
      (fields
        (field (name "DIGIKEY_PART_NUMBER") "490-MA40H1S-RCT-ND")
        (field (name "MF") "Murata")
        (field (name "MOUSER_PART_NUMBER") "81-MA40H1S-R")
      )
      (libsource (lib "eagle-import") (part "MURATA_MA40H1S-RMURATA_MA40H1S-R_0_0"))
    )
    (comp (ref "U230")
      (value "MURATA_MA40H1S-RMURATA_MA40H1S-R_0_0")
      (footprint "eagle-import:MURATA_MA40H1S-R_0")
      (fields
        (field (name "DIGIKEY_PART_NUMBER") "490-MA40H1S-RCT-ND")
        (field (name "MF") "Murata")
        (field (name "MOUSER_PART_NUMBER") "81-MA40H1S-R")
      )
      (libsource (lib "eagle-import") (part "MURATA_MA40H1S-RMURATA_MA40H1S-R_0_0"))
    )
    (comp (ref "U231")
      (value "MURATA_MA40H1S-RMURATA_MA40H1S-R_0_0")
      (footprint "eagle-import:MURATA_MA40H1S-R_0")
      (fields
        (field (name "DIGIKEY_PART_NUMBER") "490-MA40H1S-RCT-ND")
        (field (name "MF") "Murata")
        (field (name "MOUSER_PART_NUMBER") "81-MA40H1S-R")
      )
      (libsource (lib "eagle-import") (part "MURATA_MA40H1S-RMURATA_MA40H1S-R_0_0"))
    )
    (comp (ref "U232")
      (value "MURATA_MA40H1S-RMURATA_MA40H1S-R_0_0")
      (footprint "eagle-import:MURATA_MA40H1S-R_0")
      (fields
        (field (name "DIGIKEY_PART_NUMBER") "490-MA40H1S-RCT-ND")
        (field (name "MF") "Murata")
        (field (name "MOUSER_PART_NUMBER") "81-MA40H1S-R")
      )
      (libsource (lib "eagle-import") (part "MURATA_MA40H1S-RMURATA_MA40H1S-R_0_0"))
    )
    (comp (ref "U233")
      (value "MURATA_MA40H1S-RMURATA_MA40H1S-R_0_0")
      (footprint "eagle-import:MURATA_MA40H1S-R_0")
      (fields
        (field (name "DIGIKEY_PART_NUMBER") "490-MA40H1S-RCT-ND")
        (field (name "MF") "Murata")
        (field (name "MOUSER_PART_NUMBER") "81-MA40H1S-R")
      )
      (libsource (lib "eagle-import") (part "MURATA_MA40H1S-RMURATA_MA40H1S-R_0_0"))
    )
    (comp (ref "U234")
      (value "MURATA_MA40H1S-RMURATA_MA40H1S-R_0_0")
      (footprint "eagle-import:MURATA_MA40H1S-R_0")
      (fields
        (field (name "DIGIKEY_PART_NUMBER") "490-MA40H1S-RCT-ND")
        (field (name "MF") "Murata")
        (field (name "MOUSER_PART_NUMBER") "81-MA40H1S-R")
      )
      (libsource (lib "eagle-import") (part "MURATA_MA40H1S-RMURATA_MA40H1S-R_0_0"))
    )
    (comp (ref "U235")
      (value "MURATA_MA40H1S-RMURATA_MA40H1S-R_0_0")
      (footprint "eagle-import:MURATA_MA40H1S-R_0")
      (fields
        (field (name "DIGIKEY_PART_NUMBER") "490-MA40H1S-RCT-ND")
        (field (name "MF") "Murata")
        (field (name "MOUSER_PART_NUMBER") "81-MA40H1S-R")
      )
      (libsource (lib "eagle-import") (part "MURATA_MA40H1S-RMURATA_MA40H1S-R_0_0"))
    )
    (comp (ref "U236")
      (value "MURATA_MA40H1S-RMURATA_MA40H1S-R_0_0")
      (footprint "eagle-import:MURATA_MA40H1S-R_0")
      (fields
        (field (name "DIGIKEY_PART_NUMBER") "490-MA40H1S-RCT-ND")
        (field (name "MF") "Murata")
        (field (name "MOUSER_PART_NUMBER") "81-MA40H1S-R")
      )
      (libsource (lib "eagle-import") (part "MURATA_MA40H1S-RMURATA_MA40H1S-R_0_0"))
    )
    (comp (ref "U237")
      (value "MURATA_MA40H1S-RMURATA_MA40H1S-R_0_0")
      (footprint "eagle-import:MURATA_MA40H1S-R_0")
      (fields
        (field (name "DIGIKEY_PART_NUMBER") "490-MA40H1S-RCT-ND")
        (field (name "MF") "Murata")
        (field (name "MOUSER_PART_NUMBER") "81-MA40H1S-R")
      )
      (libsource (lib "eagle-import") (part "MURATA_MA40H1S-RMURATA_MA40H1S-R_0_0"))
    )
    (comp (ref "U238")
      (value "MURATA_MA40H1S-RMURATA_MA40H1S-R_0_0")
      (footprint "eagle-import:MURATA_MA40H1S-R_0")
      (fields
        (field (name "DIGIKEY_PART_NUMBER") "490-MA40H1S-RCT-ND")
        (field (name "MF") "Murata")
        (field (name "MOUSER_PART_NUMBER") "81-MA40H1S-R")
      )
      (libsource (lib "eagle-import") (part "MURATA_MA40H1S-RMURATA_MA40H1S-R_0_0"))
    )
    (comp (ref "U239")
      (value "MURATA_MA40H1S-RMURATA_MA40H1S-R_0_0")
      (footprint "eagle-import:MURATA_MA40H1S-R_0")
      (fields
        (field (name "DIGIKEY_PART_NUMBER") "490-MA40H1S-RCT-ND")
        (field (name "MF") "Murata")
        (field (name "MOUSER_PART_NUMBER") "81-MA40H1S-R")
      )
      (libsource (lib "eagle-import") (part "MURATA_MA40H1S-RMURATA_MA40H1S-R_0_0"))
    )
    (comp (ref "U240")
      (value "MURATA_MA40H1S-RMURATA_MA40H1S-R_0_0")
      (footprint "eagle-import:MURATA_MA40H1S-R_0")
      (fields
        (field (name "DIGIKEY_PART_NUMBER") "490-MA40H1S-RCT-ND")
        (field (name "MF") "Murata")
        (field (name "MOUSER_PART_NUMBER") "81-MA40H1S-R")
      )
      (libsource (lib "eagle-import") (part "MURATA_MA40H1S-RMURATA_MA40H1S-R_0_0"))
    )
    (comp (ref "U241")
      (value "MURATA_MA40H1S-RMURATA_MA40H1S-R_0_0")
      (footprint "eagle-import:MURATA_MA40H1S-R_0")
      (fields
        (field (name "DIGIKEY_PART_NUMBER") "490-MA40H1S-RCT-ND")
        (field (name "MF") "Murata")
        (field (name "MOUSER_PART_NUMBER") "81-MA40H1S-R")
      )
      (libsource (lib "eagle-import") (part "MURATA_MA40H1S-RMURATA_MA40H1S-R_0_0"))
    )
    (comp (ref "U242")
      (value "MURATA_MA40H1S-RMURATA_MA40H1S-R_0_0")
      (footprint "eagle-import:MURATA_MA40H1S-R_0")
      (fields
        (field (name "DIGIKEY_PART_NUMBER") "490-MA40H1S-RCT-ND")
        (field (name "MF") "Murata")
        (field (name "MOUSER_PART_NUMBER") "81-MA40H1S-R")
      )
      (libsource (lib "eagle-import") (part "MURATA_MA40H1S-RMURATA_MA40H1S-R_0_0"))
    )
    (comp (ref "U246")
      (value "MURATA_MA40H1S-RMURATA_MA40H1S-R_0_0")
      (footprint "eagle-import:MURATA_MA40H1S-R_0")
      (fields
        (field (name "DIGIKEY_PART_NUMBER") "490-MA40H1S-RCT-ND")
        (field (name "MF") "Murata")
        (field (name "MOUSER_PART_NUMBER") "81-MA40H1S-R")
      )
      (libsource (lib "eagle-import") (part "MURATA_MA40H1S-RMURATA_MA40H1S-R_0_0"))
    )
    (comp (ref "U247")
      (value "MURATA_MA40H1S-RMURATA_MA40H1S-R_0_0")
      (footprint "eagle-import:MURATA_MA40H1S-R_0")
      (fields
        (field (name "DIGIKEY_PART_NUMBER") "490-MA40H1S-RCT-ND")
        (field (name "MF") "Murata")
        (field (name "MOUSER_PART_NUMBER") "81-MA40H1S-R")
      )
      (libsource (lib "eagle-import") (part "MURATA_MA40H1S-RMURATA_MA40H1S-R_0_0"))
    )
    (comp (ref "U248")
      (value "MURATA_MA40H1S-RMURATA_MA40H1S-R_0_0")
      (footprint "eagle-import:MURATA_MA40H1S-R_0")
      (fields
        (field (name "DIGIKEY_PART_NUMBER") "490-MA40H1S-RCT-ND")
        (field (name "MF") "Murata")
        (field (name "MOUSER_PART_NUMBER") "81-MA40H1S-R")
      )
      (libsource (lib "eagle-import") (part "MURATA_MA40H1S-RMURATA_MA40H1S-R_0_0"))
    )
    (comp (ref "U249")
      (value "MURATA_MA40H1S-RMURATA_MA40H1S-R_0_0")
      (footprint "eagle-import:MURATA_MA40H1S-R_0")
      (fields
        (field (name "DIGIKEY_PART_NUMBER") "490-MA40H1S-RCT-ND")
        (field (name "MF") "Murata")
        (field (name "MOUSER_PART_NUMBER") "81-MA40H1S-R")
      )
      (libsource (lib "eagle-import") (part "MURATA_MA40H1S-RMURATA_MA40H1S-R_0_0"))
    )
    (comp (ref "U250")
      (value "MURATA_MA40H1S-RMURATA_MA40H1S-R_0_0")
      (footprint "eagle-import:MURATA_MA40H1S-R_0")
      (fields
        (field (name "DIGIKEY_PART_NUMBER") "490-MA40H1S-RCT-ND")
        (field (name "MF") "Murata")
        (field (name "MOUSER_PART_NUMBER") "81-MA40H1S-R")
      )
      (libsource (lib "eagle-import") (part "MURATA_MA40H1S-RMURATA_MA40H1S-R_0_0"))
    )
    (comp (ref "U251")
      (value "MURATA_MA40H1S-RMURATA_MA40H1S-R_0_0")
      (footprint "eagle-import:MURATA_MA40H1S-R_0")
      (fields
        (field (name "DIGIKEY_PART_NUMBER") "490-MA40H1S-RCT-ND")
        (field (name "MF") "Murata")
        (field (name "MOUSER_PART_NUMBER") "81-MA40H1S-R")
      )
      (libsource (lib "eagle-import") (part "MURATA_MA40H1S-RMURATA_MA40H1S-R_0_0"))
    )
    (comp (ref "U252")
      (value "MURATA_MA40H1S-RMURATA_MA40H1S-R_0_0")
      (footprint "eagle-import:MURATA_MA40H1S-R_0")
      (fields
        (field (name "DIGIKEY_PART_NUMBER") "490-MA40H1S-RCT-ND")
        (field (name "MF") "Murata")
        (field (name "MOUSER_PART_NUMBER") "81-MA40H1S-R")
      )
      (libsource (lib "eagle-import") (part "MURATA_MA40H1S-RMURATA_MA40H1S-R_0_0"))
    )
    (comp (ref "U253")
      (value "MURATA_MA40H1S-RMURATA_MA40H1S-R_0_0")
      (footprint "eagle-import:MURATA_MA40H1S-R_0")
      (fields
        (field (name "DIGIKEY_PART_NUMBER") "490-MA40H1S-RCT-ND")
        (field (name "MF") "Murata")
        (field (name "MOUSER_PART_NUMBER") "81-MA40H1S-R")
      )
      (libsource (lib "eagle-import") (part "MURATA_MA40H1S-RMURATA_MA40H1S-R_0_0"))
    )
    (comp (ref "U254")
      (value "MURATA_MA40H1S-RMURATA_MA40H1S-R_0_0")
      (footprint "eagle-import:MURATA_MA40H1S-R_0")
      (fields
        (field (name "DIGIKEY_PART_NUMBER") "490-MA40H1S-RCT-ND")
        (field (name "MF") "Murata")
        (field (name "MOUSER_PART_NUMBER") "81-MA40H1S-R")
      )
      (libsource (lib "eagle-import") (part "MURATA_MA40H1S-RMURATA_MA40H1S-R_0_0"))
    )
    (comp (ref "U255")
      (value "MURATA_MA40H1S-RMURATA_MA40H1S-R_0_0")
      (footprint "eagle-import:MURATA_MA40H1S-R_0")
      (fields
        (field (name "DIGIKEY_PART_NUMBER") "490-MA40H1S-RCT-ND")
        (field (name "MF") "Murata")
        (field (name "MOUSER_PART_NUMBER") "81-MA40H1S-R")
      )
      (libsource (lib "eagle-import") (part "MURATA_MA40H1S-RMURATA_MA40H1S-R_0_0"))
    )
    (comp (ref "U256")
      (value "MURATA_MA40H1S-RMURATA_MA40H1S-R_0_0")
      (footprint "eagle-import:MURATA_MA40H1S-R_0")
      (fields
        (field (name "DIGIKEY_PART_NUMBER") "490-MA40H1S-RCT-ND")
        (field (name "MF") "Murata")
        (field (name "MOUSER_PART_NUMBER") "81-MA40H1S-R")
      )
      (libsource (lib "eagle-import") (part "MURATA_MA40H1S-RMURATA_MA40H1S-R_0_0"))
    )
    (comp (ref "U257")
      (value "MURATA_MA40H1S-RMURATA_MA40H1S-R_0_0")
      (footprint "eagle-import:MURATA_MA40H1S-R_0")
      (fields
        (field (name "DIGIKEY_PART_NUMBER") "490-MA40H1S-RCT-ND")
        (field (name "MF") "Murata")
        (field (name "MOUSER_PART_NUMBER") "81-MA40H1S-R")
      )
      (libsource (lib "eagle-import") (part "MURATA_MA40H1S-RMURATA_MA40H1S-R_0_0"))
    )
    (comp (ref "U258")
      (value "MURATA_MA40H1S-RMURATA_MA40H1S-R_0_0")
      (footprint "eagle-import:MURATA_MA40H1S-R_0")
      (fields
        (field (name "DIGIKEY_PART_NUMBER") "490-MA40H1S-RCT-ND")
        (field (name "MF") "Murata")
        (field (name "MOUSER_PART_NUMBER") "81-MA40H1S-R")
      )
      (libsource (lib "eagle-import") (part "MURATA_MA40H1S-RMURATA_MA40H1S-R_0_0"))
    )
    (comp (ref "U259")
      (value "MURATA_MA40H1S-RMURATA_MA40H1S-R_0_0")
      (footprint "eagle-import:MURATA_MA40H1S-R_0")
      (fields
        (field (name "DIGIKEY_PART_NUMBER") "490-MA40H1S-RCT-ND")
        (field (name "MF") "Murata")
        (field (name "MOUSER_PART_NUMBER") "81-MA40H1S-R")
      )
      (libsource (lib "eagle-import") (part "MURATA_MA40H1S-RMURATA_MA40H1S-R_0_0"))
    )
    (comp (ref "U260")
      (value "MURATA_MA40H1S-RMURATA_MA40H1S-R_0_0")
      (footprint "eagle-import:MURATA_MA40H1S-R_0")
      (fields
        (field (name "DIGIKEY_PART_NUMBER") "490-MA40H1S-RCT-ND")
        (field (name "MF") "Murata")
        (field (name "MOUSER_PART_NUMBER") "81-MA40H1S-R")
      )
      (libsource (lib "eagle-import") (part "MURATA_MA40H1S-RMURATA_MA40H1S-R_0_0"))
    )
    (comp (ref "U261")
      (value "MURATA_MA40H1S-RMURATA_MA40H1S-R_0_0")
      (footprint "eagle-import:MURATA_MA40H1S-R_0")
      (fields
        (field (name "DIGIKEY_PART_NUMBER") "490-MA40H1S-RCT-ND")
        (field (name "MF") "Murata")
        (field (name "MOUSER_PART_NUMBER") "81-MA40H1S-R")
      )
      (libsource (lib "eagle-import") (part "MURATA_MA40H1S-RMURATA_MA40H1S-R_0_0"))
    )
    (comp (ref "U262")
      (value "MURATA_MA40H1S-RMURATA_MA40H1S-R_0_0")
      (footprint "eagle-import:MURATA_MA40H1S-R_0")
      (fields
        (field (name "DIGIKEY_PART_NUMBER") "490-MA40H1S-RCT-ND")
        (field (name "MF") "Murata")
        (field (name "MOUSER_PART_NUMBER") "81-MA40H1S-R")
      )
      (libsource (lib "eagle-import") (part "MURATA_MA40H1S-RMURATA_MA40H1S-R_0_0"))
    )
    (comp (ref "U263")
      (value "MURATA_MA40H1S-RMURATA_MA40H1S-R_0_0")
      (footprint "eagle-import:MURATA_MA40H1S-R_0")
      (fields
        (field (name "DIGIKEY_PART_NUMBER") "490-MA40H1S-RCT-ND")
        (field (name "MF") "Murata")
        (field (name "MOUSER_PART_NUMBER") "81-MA40H1S-R")
      )
      (libsource (lib "eagle-import") (part "MURATA_MA40H1S-RMURATA_MA40H1S-R_0_0"))
    )
    (comp (ref "U264")
      (value "MURATA_MA40H1S-RMURATA_MA40H1S-R_0_0")
      (footprint "eagle-import:MURATA_MA40H1S-R_0")
      (fields
        (field (name "DIGIKEY_PART_NUMBER") "490-MA40H1S-RCT-ND")
        (field (name "MF") "Murata")
        (field (name "MOUSER_PART_NUMBER") "81-MA40H1S-R")
      )
      (libsource (lib "eagle-import") (part "MURATA_MA40H1S-RMURATA_MA40H1S-R_0_0"))
    )
    (comp (ref "U265")
      (value "MURATA_MA40H1S-RMURATA_MA40H1S-R_0_0")
      (footprint "eagle-import:MURATA_MA40H1S-R_0")
      (fields
        (field (name "DIGIKEY_PART_NUMBER") "490-MA40H1S-RCT-ND")
        (field (name "MF") "Murata")
        (field (name "MOUSER_PART_NUMBER") "81-MA40H1S-R")
      )
      (libsource (lib "eagle-import") (part "MURATA_MA40H1S-RMURATA_MA40H1S-R_0_0"))
    )
    (comp (ref "U266")
      (value "MURATA_MA40H1S-RMURATA_MA40H1S-R_0_0")
      (footprint "eagle-import:MURATA_MA40H1S-R_0")
      (fields
        (field (name "DIGIKEY_PART_NUMBER") "490-MA40H1S-RCT-ND")
        (field (name "MF") "Murata")
        (field (name "MOUSER_PART_NUMBER") "81-MA40H1S-R")
      )
      (libsource (lib "eagle-import") (part "MURATA_MA40H1S-RMURATA_MA40H1S-R_0_0"))
    )
    (comp (ref "U267")
      (value "MURATA_MA40H1S-RMURATA_MA40H1S-R_0_0")
      (footprint "eagle-import:MURATA_MA40H1S-R_0")
      (fields
        (field (name "DIGIKEY_PART_NUMBER") "490-MA40H1S-RCT-ND")
        (field (name "MF") "Murata")
        (field (name "MOUSER_PART_NUMBER") "81-MA40H1S-R")
      )
      (libsource (lib "eagle-import") (part "MURATA_MA40H1S-RMURATA_MA40H1S-R_0_0"))
    )
    (comp (ref "U268")
      (value "MURATA_MA40H1S-RMURATA_MA40H1S-R_0_0")
      (footprint "eagle-import:MURATA_MA40H1S-R_0")
      (fields
        (field (name "DIGIKEY_PART_NUMBER") "490-MA40H1S-RCT-ND")
        (field (name "MF") "Murata")
        (field (name "MOUSER_PART_NUMBER") "81-MA40H1S-R")
      )
      (libsource (lib "eagle-import") (part "MURATA_MA40H1S-RMURATA_MA40H1S-R_0_0"))
    )
    (comp (ref "U269")
      (value "MURATA_MA40H1S-RMURATA_MA40H1S-R_0_0")
      (footprint "eagle-import:MURATA_MA40H1S-R_0")
      (fields
        (field (name "DIGIKEY_PART_NUMBER") "490-MA40H1S-RCT-ND")
        (field (name "MF") "Murata")
        (field (name "MOUSER_PART_NUMBER") "81-MA40H1S-R")
      )
      (libsource (lib "eagle-import") (part "MURATA_MA40H1S-RMURATA_MA40H1S-R_0_0"))
    )
    (comp (ref "U270")
      (value "MURATA_MA40H1S-RMURATA_MA40H1S-R_0_0")
      (footprint "eagle-import:MURATA_MA40H1S-R_0")
      (fields
        (field (name "DIGIKEY_PART_NUMBER") "490-MA40H1S-RCT-ND")
        (field (name "MF") "Murata")
        (field (name "MOUSER_PART_NUMBER") "81-MA40H1S-R")
      )
      (libsource (lib "eagle-import") (part "MURATA_MA40H1S-RMURATA_MA40H1S-R_0_0"))
    )
    (comp (ref "U271")
      (value "MURATA_MA40H1S-RMURATA_MA40H1S-R_0_0")
      (footprint "eagle-import:MURATA_MA40H1S-R_0")
      (fields
        (field (name "DIGIKEY_PART_NUMBER") "490-MA40H1S-RCT-ND")
        (field (name "MF") "Murata")
        (field (name "MOUSER_PART_NUMBER") "81-MA40H1S-R")
      )
      (libsource (lib "eagle-import") (part "MURATA_MA40H1S-RMURATA_MA40H1S-R_0_0"))
    )
    (comp (ref "U272")
      (value "MURATA_MA40H1S-RMURATA_MA40H1S-R_0_0")
      (footprint "eagle-import:MURATA_MA40H1S-R_0")
      (fields
        (field (name "DIGIKEY_PART_NUMBER") "490-MA40H1S-RCT-ND")
        (field (name "MF") "Murata")
        (field (name "MOUSER_PART_NUMBER") "81-MA40H1S-R")
      )
      (libsource (lib "eagle-import") (part "MURATA_MA40H1S-RMURATA_MA40H1S-R_0_0"))
    )
    (comp (ref "U273")
      (value "MURATA_MA40H1S-RMURATA_MA40H1S-R_0_0")
      (footprint "eagle-import:MURATA_MA40H1S-R_0")
      (fields
        (field (name "DIGIKEY_PART_NUMBER") "490-MA40H1S-RCT-ND")
        (field (name "MF") "Murata")
        (field (name "MOUSER_PART_NUMBER") "81-MA40H1S-R")
      )
      (libsource (lib "eagle-import") (part "MURATA_MA40H1S-RMURATA_MA40H1S-R_0_0"))
    )
    (comp (ref "U274")
      (value "MURATA_MA40H1S-RMURATA_MA40H1S-R_0_0")
      (footprint "eagle-import:MURATA_MA40H1S-R_0")
      (fields
        (field (name "DIGIKEY_PART_NUMBER") "490-MA40H1S-RCT-ND")
        (field (name "MF") "Murata")
        (field (name "MOUSER_PART_NUMBER") "81-MA40H1S-R")
      )
      (libsource (lib "eagle-import") (part "MURATA_MA40H1S-RMURATA_MA40H1S-R_0_0"))
    )
    (comp (ref "U275")
      (value "MURATA_MA40H1S-RMURATA_MA40H1S-R_0_0")
      (footprint "eagle-import:MURATA_MA40H1S-R_0")
      (fields
        (field (name "DIGIKEY_PART_NUMBER") "490-MA40H1S-RCT-ND")
        (field (name "MF") "Murata")
        (field (name "MOUSER_PART_NUMBER") "81-MA40H1S-R")
      )
      (libsource (lib "eagle-import") (part "MURATA_MA40H1S-RMURATA_MA40H1S-R_0_0"))
    )
  )
  (nets
    (net (code "1") (name "GND") (class "Default")
      (node (ref "J1") (pin "1") (pinfunction "1_1") (pintype "passive"))
      (node (ref "J2") (pin "1") (pinfunction "1_1") (pintype "passive"))
      (node (ref "J4") (pin "1") (pinfunction "1_1") (pintype "passive"))
      (node (ref "J5") (pin "1") (pinfunction "1_1") (pintype "passive"))
      (node (ref "J5") (pin "11") (pinfunction "11_11") (pintype "passive"))
      (node (ref "J5") (pin "13") (pinfunction "13_13") (pintype "passive"))
      (node (ref "J5") (pin "15") (pinfunction "15_15") (pintype "passive"))
      (node (ref "J5") (pin "3") (pinfunction "3_3") (pintype "passive"))
      (node (ref "J5") (pin "5") (pinfunction "5_5") (pintype "passive"))
      (node (ref "J5") (pin "7") (pinfunction "7_7") (pintype "passive"))
      (node (ref "J5") (pin "9") (pinfunction "9_9") (pintype "passive"))
      (node (ref "J6") (pin "1") (pinfunction "1_1") (pintype "passive"))
      (node (ref "J8") (pin "1") (pinfunction "1_1") (pintype "passive"))
      (node (ref "U1") (pin "3") (pinfunction "2_SIGNAL_TERMINAL_3") (pintype "passive"))
      (node (ref "U10") (pin "3") (pinfunction "2_SIGNAL_TERMINAL_3") (pintype "passive"))
      (node (ref "U100") (pin "3") (pinfunction "2_SIGNAL_TERMINAL_3") (pintype "passive"))
      (node (ref "U101") (pin "3") (pinfunction "2_SIGNAL_TERMINAL_3") (pintype "passive"))
      (node (ref "U102") (pin "3") (pinfunction "2_SIGNAL_TERMINAL_3") (pintype "passive"))
      (node (ref "U103") (pin "3") (pinfunction "2_SIGNAL_TERMINAL_3") (pintype "passive"))
      (node (ref "U104") (pin "3") (pinfunction "2_SIGNAL_TERMINAL_3") (pintype "passive"))
      (node (ref "U105") (pin "3") (pinfunction "2_SIGNAL_TERMINAL_3") (pintype "passive"))
      (node (ref "U106") (pin "3") (pinfunction "2_SIGNAL_TERMINAL_3") (pintype "passive"))
      (node (ref "U107") (pin "3") (pinfunction "2_SIGNAL_TERMINAL_3") (pintype "passive"))
      (node (ref "U108") (pin "3") (pinfunction "2_SIGNAL_TERMINAL_3") (pintype "passive"))
      (node (ref "U109") (pin "3") (pinfunction "2_SIGNAL_TERMINAL_3") (pintype "passive"))
      (node (ref "U110") (pin "3") (pinfunction "2_SIGNAL_TERMINAL_3") (pintype "passive"))
      (node (ref "U111") (pin "3") (pinfunction "2_SIGNAL_TERMINAL_3") (pintype "passive"))
      (node (ref "U112") (pin "3") (pinfunction "2_SIGNAL_TERMINAL_3") (pintype "passive"))
      (node (ref "U113") (pin "3") (pinfunction "2_SIGNAL_TERMINAL_3") (pintype "passive"))
      (node (ref "U114") (pin "3") (pinfunction "2_SIGNAL_TERMINAL_3") (pintype "passive"))
      (node (ref "U115") (pin "3") (pinfunction "2_SIGNAL_TERMINAL_3") (pintype "passive"))
      (node (ref "U116") (pin "3") (pinfunction "2_SIGNAL_TERMINAL_3") (pintype "passive"))
      (node (ref "U117") (pin "3") (pinfunction "2_SIGNAL_TERMINAL_3") (pintype "passive"))
      (node (ref "U118") (pin "3") (pinfunction "2_SIGNAL_TERMINAL_3") (pintype "passive"))
      (node (ref "U119") (pin "3") (pinfunction "2_SIGNAL_TERMINAL_3") (pintype "passive"))
      (node (ref "U12") (pin "3") (pinfunction "2_SIGNAL_TERMINAL_3") (pintype "passive"))
      (node (ref "U120") (pin "3") (pinfunction "2_SIGNAL_TERMINAL_3") (pintype "passive"))
      (node (ref "U121") (pin "3") (pinfunction "2_SIGNAL_TERMINAL_3") (pintype "passive"))
      (node (ref "U122") (pin "3") (pinfunction "2_SIGNAL_TERMINAL_3") (pintype "passive"))
      (node (ref "U123") (pin "3") (pinfunction "2_SIGNAL_TERMINAL_3") (pintype "passive"))
      (node (ref "U124") (pin "3") (pinfunction "2_SIGNAL_TERMINAL_3") (pintype "passive"))
      (node (ref "U125") (pin "3") (pinfunction "2_SIGNAL_TERMINAL_3") (pintype "passive"))
      (node (ref "U126") (pin "3") (pinfunction "2_SIGNAL_TERMINAL_3") (pintype "passive"))
      (node (ref "U127") (pin "3") (pinfunction "2_SIGNAL_TERMINAL_3") (pintype "passive"))
      (node (ref "U128") (pin "3") (pinfunction "2_SIGNAL_TERMINAL_3") (pintype "passive"))
      (node (ref "U129") (pin "3") (pinfunction "2_SIGNAL_TERMINAL_3") (pintype "passive"))
      (node (ref "U13") (pin "3") (pinfunction "2_SIGNAL_TERMINAL_3") (pintype "passive"))
      (node (ref "U130") (pin "3") (pinfunction "2_SIGNAL_TERMINAL_3") (pintype "passive"))
      (node (ref "U131") (pin "3") (pinfunction "2_SIGNAL_TERMINAL_3") (pintype "passive"))
      (node (ref "U132") (pin "3") (pinfunction "2_SIGNAL_TERMINAL_3") (pintype "passive"))
      (node (ref "U133") (pin "3") (pinfunction "2_SIGNAL_TERMINAL_3") (pintype "passive"))
      (node (ref "U134") (pin "3") (pinfunction "2_SIGNAL_TERMINAL_3") (pintype "passive"))
      (node (ref "U135") (pin "3") (pinfunction "2_SIGNAL_TERMINAL_3") (pintype "passive"))
      (node (ref "U136") (pin "3") (pinfunction "2_SIGNAL_TERMINAL_3") (pintype "passive"))
      (node (ref "U137") (pin "3") (pinfunction "2_SIGNAL_TERMINAL_3") (pintype "passive"))
      (node (ref "U138") (pin "3") (pinfunction "2_SIGNAL_TERMINAL_3") (pintype "passive"))
      (node (ref "U139") (pin "3") (pinfunction "2_SIGNAL_TERMINAL_3") (pintype "passive"))
      (node (ref "U14") (pin "3") (pinfunction "2_SIGNAL_TERMINAL_3") (pintype "passive"))
      (node (ref "U140") (pin "3") (pinfunction "2_SIGNAL_TERMINAL_3") (pintype "passive"))
      (node (ref "U141") (pin "3") (pinfunction "2_SIGNAL_TERMINAL_3") (pintype "passive"))
      (node (ref "U142") (pin "3") (pinfunction "2_SIGNAL_TERMINAL_3") (pintype "passive"))
      (node (ref "U143") (pin "3") (pinfunction "2_SIGNAL_TERMINAL_3") (pintype "passive"))
      (node (ref "U144") (pin "3") (pinfunction "2_SIGNAL_TERMINAL_3") (pintype "passive"))
      (node (ref "U145") (pin "3") (pinfunction "2_SIGNAL_TERMINAL_3") (pintype "passive"))
      (node (ref "U146") (pin "3") (pinfunction "2_SIGNAL_TERMINAL_3") (pintype "passive"))
      (node (ref "U147") (pin "3") (pinfunction "2_SIGNAL_TERMINAL_3") (pintype "passive"))
      (node (ref "U148") (pin "3") (pinfunction "2_SIGNAL_TERMINAL_3") (pintype "passive"))
      (node (ref "U149") (pin "3") (pinfunction "2_SIGNAL_TERMINAL_3") (pintype "passive"))
      (node (ref "U15") (pin "3") (pinfunction "2_SIGNAL_TERMINAL_3") (pintype "passive"))
      (node (ref "U150") (pin "3") (pinfunction "2_SIGNAL_TERMINAL_3") (pintype "passive"))
      (node (ref "U151") (pin "3") (pinfunction "2_SIGNAL_TERMINAL_3") (pintype "passive"))
      (node (ref "U152") (pin "3") (pinfunction "2_SIGNAL_TERMINAL_3") (pintype "passive"))
      (node (ref "U153") (pin "3") (pinfunction "2_SIGNAL_TERMINAL_3") (pintype "passive"))
      (node (ref "U154") (pin "3") (pinfunction "2_SIGNAL_TERMINAL_3") (pintype "passive"))
      (node (ref "U155") (pin "3") (pinfunction "2_SIGNAL_TERMINAL_3") (pintype "passive"))
      (node (ref "U156") (pin "3") (pinfunction "2_SIGNAL_TERMINAL_3") (pintype "passive"))
      (node (ref "U157") (pin "3") (pinfunction "2_SIGNAL_TERMINAL_3") (pintype "passive"))
      (node (ref "U158") (pin "3") (pinfunction "2_SIGNAL_TERMINAL_3") (pintype "passive"))
      (node (ref "U159") (pin "3") (pinfunction "2_SIGNAL_TERMINAL_3") (pintype "passive"))
      (node (ref "U16") (pin "3") (pinfunction "2_SIGNAL_TERMINAL_3") (pintype "passive"))
      (node (ref "U160") (pin "3") (pinfunction "2_SIGNAL_TERMINAL_3") (pintype "passive"))
      (node (ref "U161") (pin "3") (pinfunction "2_SIGNAL_TERMINAL_3") (pintype "passive"))
      (node (ref "U162") (pin "3") (pinfunction "2_SIGNAL_TERMINAL_3") (pintype "passive"))
      (node (ref "U163") (pin "3") (pinfunction "2_SIGNAL_TERMINAL_3") (pintype "passive"))
      (node (ref "U164") (pin "3") (pinfunction "2_SIGNAL_TERMINAL_3") (pintype "passive"))
      (node (ref "U165") (pin "3") (pinfunction "2_SIGNAL_TERMINAL_3") (pintype "passive"))
      (node (ref "U166") (pin "3") (pinfunction "2_SIGNAL_TERMINAL_3") (pintype "passive"))
      (node (ref "U167") (pin "3") (pinfunction "2_SIGNAL_TERMINAL_3") (pintype "passive"))
      (node (ref "U168") (pin "3") (pinfunction "2_SIGNAL_TERMINAL_3") (pintype "passive"))
      (node (ref "U169") (pin "3") (pinfunction "2_SIGNAL_TERMINAL_3") (pintype "passive"))
      (node (ref "U170") (pin "3") (pinfunction "2_SIGNAL_TERMINAL_3") (pintype "passive"))
      (node (ref "U171") (pin "3") (pinfunction "2_SIGNAL_TERMINAL_3") (pintype "passive"))
      (node (ref "U172") (pin "3") (pinfunction "2_SIGNAL_TERMINAL_3") (pintype "passive"))
      (node (ref "U173") (pin "3") (pinfunction "2_SIGNAL_TERMINAL_3") (pintype "passive"))
      (node (ref "U174") (pin "3") (pinfunction "2_SIGNAL_TERMINAL_3") (pintype "passive"))
      (node (ref "U175") (pin "3") (pinfunction "2_SIGNAL_TERMINAL_3") (pintype "passive"))
      (node (ref "U176") (pin "3") (pinfunction "2_SIGNAL_TERMINAL_3") (pintype "passive"))
      (node (ref "U177") (pin "3") (pinfunction "2_SIGNAL_TERMINAL_3") (pintype "passive"))
      (node (ref "U178") (pin "3") (pinfunction "2_SIGNAL_TERMINAL_3") (pintype "passive"))
      (node (ref "U179") (pin "3") (pinfunction "2_SIGNAL_TERMINAL_3") (pintype "passive"))
      (node (ref "U180") (pin "3") (pinfunction "2_SIGNAL_TERMINAL_3") (pintype "passive"))
      (node (ref "U184") (pin "3") (pinfunction "2_SIGNAL_TERMINAL_3") (pintype "passive"))
      (node (ref "U185") (pin "3") (pinfunction "2_SIGNAL_TERMINAL_3") (pintype "passive"))
      (node (ref "U186") (pin "3") (pinfunction "2_SIGNAL_TERMINAL_3") (pintype "passive"))
      (node (ref "U192") (pin "3") (pinfunction "2_SIGNAL_TERMINAL_3") (pintype "passive"))
      (node (ref "U193") (pin "3") (pinfunction "2_SIGNAL_TERMINAL_3") (pintype "passive"))
      (node (ref "U194") (pin "3") (pinfunction "2_SIGNAL_TERMINAL_3") (pintype "passive"))
      (node (ref "U195") (pin "3") (pinfunction "2_SIGNAL_TERMINAL_3") (pintype "passive"))
      (node (ref "U196") (pin "3") (pinfunction "2_SIGNAL_TERMINAL_3") (pintype "passive"))
      (node (ref "U197") (pin "3") (pinfunction "2_SIGNAL_TERMINAL_3") (pintype "passive"))
      (node (ref "U198") (pin "3") (pinfunction "2_SIGNAL_TERMINAL_3") (pintype "passive"))
      (node (ref "U199") (pin "3") (pinfunction "2_SIGNAL_TERMINAL_3") (pintype "passive"))
      (node (ref "U2") (pin "3") (pinfunction "2_SIGNAL_TERMINAL_3") (pintype "passive"))
      (node (ref "U200") (pin "3") (pinfunction "2_SIGNAL_TERMINAL_3") (pintype "passive"))
      (node (ref "U201") (pin "3") (pinfunction "2_SIGNAL_TERMINAL_3") (pintype "passive"))
      (node (ref "U202") (pin "3") (pinfunction "2_SIGNAL_TERMINAL_3") (pintype "passive"))
      (node (ref "U203") (pin "3") (pinfunction "2_SIGNAL_TERMINAL_3") (pintype "passive"))
      (node (ref "U204") (pin "3") (pinfunction "2_SIGNAL_TERMINAL_3") (pintype "passive"))
      (node (ref "U205") (pin "3") (pinfunction "2_SIGNAL_TERMINAL_3") (pintype "passive"))
      (node (ref "U206") (pin "3") (pinfunction "2_SIGNAL_TERMINAL_3") (pintype "passive"))
      (node (ref "U207") (pin "3") (pinfunction "2_SIGNAL_TERMINAL_3") (pintype "passive"))
      (node (ref "U208") (pin "3") (pinfunction "2_SIGNAL_TERMINAL_3") (pintype "passive"))
      (node (ref "U209") (pin "3") (pinfunction "2_SIGNAL_TERMINAL_3") (pintype "passive"))
      (node (ref "U21") (pin "3") (pinfunction "2_SIGNAL_TERMINAL_3") (pintype "passive"))
      (node (ref "U210") (pin "3") (pinfunction "2_SIGNAL_TERMINAL_3") (pintype "passive"))
      (node (ref "U211") (pin "3") (pinfunction "2_SIGNAL_TERMINAL_3") (pintype "passive"))
      (node (ref "U212") (pin "3") (pinfunction "2_SIGNAL_TERMINAL_3") (pintype "passive"))
      (node (ref "U213") (pin "3") (pinfunction "2_SIGNAL_TERMINAL_3") (pintype "passive"))
      (node (ref "U214") (pin "3") (pinfunction "2_SIGNAL_TERMINAL_3") (pintype "passive"))
      (node (ref "U215") (pin "3") (pinfunction "2_SIGNAL_TERMINAL_3") (pintype "passive"))
      (node (ref "U216") (pin "3") (pinfunction "2_SIGNAL_TERMINAL_3") (pintype "passive"))
      (node (ref "U217") (pin "3") (pinfunction "2_SIGNAL_TERMINAL_3") (pintype "passive"))
      (node (ref "U218") (pin "3") (pinfunction "2_SIGNAL_TERMINAL_3") (pintype "passive"))
      (node (ref "U219") (pin "3") (pinfunction "2_SIGNAL_TERMINAL_3") (pintype "passive"))
      (node (ref "U22") (pin "3") (pinfunction "2_SIGNAL_TERMINAL_3") (pintype "passive"))
      (node (ref "U220") (pin "3") (pinfunction "2_SIGNAL_TERMINAL_3") (pintype "passive"))
      (node (ref "U221") (pin "3") (pinfunction "2_SIGNAL_TERMINAL_3") (pintype "passive"))
      (node (ref "U222") (pin "3") (pinfunction "2_SIGNAL_TERMINAL_3") (pintype "passive"))
      (node (ref "U223") (pin "3") (pinfunction "2_SIGNAL_TERMINAL_3") (pintype "passive"))
      (node (ref "U224") (pin "3") (pinfunction "2_SIGNAL_TERMINAL_3") (pintype "passive"))
      (node (ref "U225") (pin "3") (pinfunction "2_SIGNAL_TERMINAL_3") (pintype "passive"))
      (node (ref "U226") (pin "3") (pinfunction "2_SIGNAL_TERMINAL_3") (pintype "passive"))
      (node (ref "U227") (pin "3") (pinfunction "2_SIGNAL_TERMINAL_3") (pintype "passive"))
      (node (ref "U228") (pin "3") (pinfunction "2_SIGNAL_TERMINAL_3") (pintype "passive"))
      (node (ref "U229") (pin "3") (pinfunction "2_SIGNAL_TERMINAL_3") (pintype "passive"))
      (node (ref "U23") (pin "3") (pinfunction "2_SIGNAL_TERMINAL_3") (pintype "passive"))
      (node (ref "U230") (pin "3") (pinfunction "2_SIGNAL_TERMINAL_3") (pintype "passive"))
      (node (ref "U231") (pin "3") (pinfunction "2_SIGNAL_TERMINAL_3") (pintype "passive"))
      (node (ref "U232") (pin "3") (pinfunction "2_SIGNAL_TERMINAL_3") (pintype "passive"))
      (node (ref "U233") (pin "3") (pinfunction "2_SIGNAL_TERMINAL_3") (pintype "passive"))
      (node (ref "U234") (pin "3") (pinfunction "2_SIGNAL_TERMINAL_3") (pintype "passive"))
      (node (ref "U235") (pin "3") (pinfunction "2_SIGNAL_TERMINAL_3") (pintype "passive"))
      (node (ref "U236") (pin "3") (pinfunction "2_SIGNAL_TERMINAL_3") (pintype "passive"))
      (node (ref "U237") (pin "3") (pinfunction "2_SIGNAL_TERMINAL_3") (pintype "passive"))
      (node (ref "U238") (pin "3") (pinfunction "2_SIGNAL_TERMINAL_3") (pintype "passive"))
      (node (ref "U239") (pin "3") (pinfunction "2_SIGNAL_TERMINAL_3") (pintype "passive"))
      (node (ref "U24") (pin "3") (pinfunction "2_SIGNAL_TERMINAL_3") (pintype "passive"))
      (node (ref "U240") (pin "3") (pinfunction "2_SIGNAL_TERMINAL_3") (pintype "passive"))
      (node (ref "U241") (pin "3") (pinfunction "2_SIGNAL_TERMINAL_3") (pintype "passive"))
      (node (ref "U242") (pin "3") (pinfunction "2_SIGNAL_TERMINAL_3") (pintype "passive"))
      (node (ref "U246") (pin "3") (pinfunction "2_SIGNAL_TERMINAL_3") (pintype "passive"))
      (node (ref "U247") (pin "3") (pinfunction "2_SIGNAL_TERMINAL_3") (pintype "passive"))
      (node (ref "U248") (pin "3") (pinfunction "2_SIGNAL_TERMINAL_3") (pintype "passive"))
      (node (ref "U249") (pin "3") (pinfunction "2_SIGNAL_TERMINAL_3") (pintype "passive"))
      (node (ref "U25") (pin "3") (pinfunction "2_SIGNAL_TERMINAL_3") (pintype "passive"))
      (node (ref "U250") (pin "3") (pinfunction "2_SIGNAL_TERMINAL_3") (pintype "passive"))
      (node (ref "U251") (pin "3") (pinfunction "2_SIGNAL_TERMINAL_3") (pintype "passive"))
      (node (ref "U252") (pin "3") (pinfunction "2_SIGNAL_TERMINAL_3") (pintype "passive"))
      (node (ref "U253") (pin "3") (pinfunction "2_SIGNAL_TERMINAL_3") (pintype "passive"))
      (node (ref "U254") (pin "3") (pinfunction "2_SIGNAL_TERMINAL_3") (pintype "passive"))
      (node (ref "U255") (pin "3") (pinfunction "2_SIGNAL_TERMINAL_3") (pintype "passive"))
      (node (ref "U256") (pin "3") (pinfunction "2_SIGNAL_TERMINAL_3") (pintype "passive"))
      (node (ref "U257") (pin "3") (pinfunction "2_SIGNAL_TERMINAL_3") (pintype "passive"))
      (node (ref "U258") (pin "3") (pinfunction "2_SIGNAL_TERMINAL_3") (pintype "passive"))
      (node (ref "U259") (pin "3") (pinfunction "2_SIGNAL_TERMINAL_3") (pintype "passive"))
      (node (ref "U26") (pin "3") (pinfunction "2_SIGNAL_TERMINAL_3") (pintype "passive"))
      (node (ref "U260") (pin "3") (pinfunction "2_SIGNAL_TERMINAL_3") (pintype "passive"))
      (node (ref "U261") (pin "3") (pinfunction "2_SIGNAL_TERMINAL_3") (pintype "passive"))
      (node (ref "U262") (pin "3") (pinfunction "2_SIGNAL_TERMINAL_3") (pintype "passive"))
      (node (ref "U263") (pin "3") (pinfunction "2_SIGNAL_TERMINAL_3") (pintype "passive"))
      (node (ref "U264") (pin "3") (pinfunction "2_SIGNAL_TERMINAL_3") (pintype "passive"))
      (node (ref "U265") (pin "3") (pinfunction "2_SIGNAL_TERMINAL_3") (pintype "passive"))
      (node (ref "U266") (pin "3") (pinfunction "2_SIGNAL_TERMINAL_3") (pintype "passive"))
      (node (ref "U267") (pin "3") (pinfunction "2_SIGNAL_TERMINAL_3") (pintype "passive"))
      (node (ref "U268") (pin "3") (pinfunction "2_SIGNAL_TERMINAL_3") (pintype "passive"))
      (node (ref "U269") (pin "3") (pinfunction "2_SIGNAL_TERMINAL_3") (pintype "passive"))
      (node (ref "U27") (pin "3") (pinfunction "2_SIGNAL_TERMINAL_3") (pintype "passive"))
      (node (ref "U270") (pin "3") (pinfunction "2_SIGNAL_TERMINAL_3") (pintype "passive"))
      (node (ref "U271") (pin "3") (pinfunction "2_SIGNAL_TERMINAL_3") (pintype "passive"))
      (node (ref "U272") (pin "3") (pinfunction "2_SIGNAL_TERMINAL_3") (pintype "passive"))
      (node (ref "U273") (pin "3") (pinfunction "2_SIGNAL_TERMINAL_3") (pintype "passive"))
      (node (ref "U274") (pin "3") (pinfunction "2_SIGNAL_TERMINAL_3") (pintype "passive"))
      (node (ref "U275") (pin "3") (pinfunction "2_SIGNAL_TERMINAL_3") (pintype "passive"))
      (node (ref "U28") (pin "3") (pinfunction "2_SIGNAL_TERMINAL_3") (pintype "passive"))
      (node (ref "U29") (pin "3") (pinfunction "2_SIGNAL_TERMINAL_3") (pintype "passive"))
      (node (ref "U3") (pin "3") (pinfunction "2_SIGNAL_TERMINAL_3") (pintype "passive"))
      (node (ref "U30") (pin "3") (pinfunction "2_SIGNAL_TERMINAL_3") (pintype "passive"))
      (node (ref "U31") (pin "3") (pinfunction "2_SIGNAL_TERMINAL_3") (pintype "passive"))
      (node (ref "U32") (pin "3") (pinfunction "2_SIGNAL_TERMINAL_3") (pintype "passive"))
      (node (ref "U33") (pin "3") (pinfunction "2_SIGNAL_TERMINAL_3") (pintype "passive"))
      (node (ref "U34") (pin "3") (pinfunction "2_SIGNAL_TERMINAL_3") (pintype "passive"))
      (node (ref "U35") (pin "3") (pinfunction "2_SIGNAL_TERMINAL_3") (pintype "passive"))
      (node (ref "U36") (pin "3") (pinfunction "2_SIGNAL_TERMINAL_3") (pintype "passive"))
      (node (ref "U37") (pin "3") (pinfunction "2_SIGNAL_TERMINAL_3") (pintype "passive"))
      (node (ref "U38") (pin "3") (pinfunction "2_SIGNAL_TERMINAL_3") (pintype "passive"))
      (node (ref "U39") (pin "3") (pinfunction "2_SIGNAL_TERMINAL_3") (pintype "passive"))
      (node (ref "U4") (pin "3") (pinfunction "2_SIGNAL_TERMINAL_3") (pintype "passive"))
      (node (ref "U40") (pin "3") (pinfunction "2_SIGNAL_TERMINAL_3") (pintype "passive"))
      (node (ref "U41") (pin "3") (pinfunction "2_SIGNAL_TERMINAL_3") (pintype "passive"))
      (node (ref "U42") (pin "3") (pinfunction "2_SIGNAL_TERMINAL_3") (pintype "passive"))
      (node (ref "U43") (pin "3") (pinfunction "2_SIGNAL_TERMINAL_3") (pintype "passive"))
      (node (ref "U44") (pin "3") (pinfunction "2_SIGNAL_TERMINAL_3") (pintype "passive"))
      (node (ref "U45") (pin "3") (pinfunction "2_SIGNAL_TERMINAL_3") (pintype "passive"))
      (node (ref "U46") (pin "3") (pinfunction "2_SIGNAL_TERMINAL_3") (pintype "passive"))
      (node (ref "U47") (pin "3") (pinfunction "2_SIGNAL_TERMINAL_3") (pintype "passive"))
      (node (ref "U48") (pin "3") (pinfunction "2_SIGNAL_TERMINAL_3") (pintype "passive"))
      (node (ref "U49") (pin "3") (pinfunction "2_SIGNAL_TERMINAL_3") (pintype "passive"))
      (node (ref "U50") (pin "3") (pinfunction "2_SIGNAL_TERMINAL_3") (pintype "passive"))
      (node (ref "U51") (pin "3") (pinfunction "2_SIGNAL_TERMINAL_3") (pintype "passive"))
      (node (ref "U52") (pin "3") (pinfunction "2_SIGNAL_TERMINAL_3") (pintype "passive"))
      (node (ref "U53") (pin "3") (pinfunction "2_SIGNAL_TERMINAL_3") (pintype "passive"))
      (node (ref "U54") (pin "3") (pinfunction "2_SIGNAL_TERMINAL_3") (pintype "passive"))
      (node (ref "U55") (pin "3") (pinfunction "2_SIGNAL_TERMINAL_3") (pintype "passive"))
      (node (ref "U56") (pin "3") (pinfunction "2_SIGNAL_TERMINAL_3") (pintype "passive"))
      (node (ref "U57") (pin "3") (pinfunction "2_SIGNAL_TERMINAL_3") (pintype "passive"))
      (node (ref "U58") (pin "3") (pinfunction "2_SIGNAL_TERMINAL_3") (pintype "passive"))
      (node (ref "U59") (pin "3") (pinfunction "2_SIGNAL_TERMINAL_3") (pintype "passive"))
      (node (ref "U6") (pin "3") (pinfunction "2_SIGNAL_TERMINAL_3") (pintype "passive"))
      (node (ref "U60") (pin "3") (pinfunction "2_SIGNAL_TERMINAL_3") (pintype "passive"))
      (node (ref "U61") (pin "3") (pinfunction "2_SIGNAL_TERMINAL_3") (pintype "passive"))
      (node (ref "U62") (pin "3") (pinfunction "2_SIGNAL_TERMINAL_3") (pintype "passive"))
      (node (ref "U63") (pin "3") (pinfunction "2_SIGNAL_TERMINAL_3") (pintype "passive"))
      (node (ref "U64") (pin "3") (pinfunction "2_SIGNAL_TERMINAL_3") (pintype "passive"))
      (node (ref "U65") (pin "3") (pinfunction "2_SIGNAL_TERMINAL_3") (pintype "passive"))
      (node (ref "U66") (pin "3") (pinfunction "2_SIGNAL_TERMINAL_3") (pintype "passive"))
      (node (ref "U67") (pin "3") (pinfunction "2_SIGNAL_TERMINAL_3") (pintype "passive"))
      (node (ref "U68") (pin "3") (pinfunction "2_SIGNAL_TERMINAL_3") (pintype "passive"))
      (node (ref "U69") (pin "3") (pinfunction "2_SIGNAL_TERMINAL_3") (pintype "passive"))
      (node (ref "U70") (pin "3") (pinfunction "2_SIGNAL_TERMINAL_3") (pintype "passive"))
      (node (ref "U71") (pin "3") (pinfunction "2_SIGNAL_TERMINAL_3") (pintype "passive"))
      (node (ref "U72") (pin "3") (pinfunction "2_SIGNAL_TERMINAL_3") (pintype "passive"))
      (node (ref "U73") (pin "3") (pinfunction "2_SIGNAL_TERMINAL_3") (pintype "passive"))
      (node (ref "U74") (pin "3") (pinfunction "2_SIGNAL_TERMINAL_3") (pintype "passive"))
      (node (ref "U75") (pin "3") (pinfunction "2_SIGNAL_TERMINAL_3") (pintype "passive"))
      (node (ref "U76") (pin "3") (pinfunction "2_SIGNAL_TERMINAL_3") (pintype "passive"))
      (node (ref "U77") (pin "3") (pinfunction "2_SIGNAL_TERMINAL_3") (pintype "passive"))
      (node (ref "U78") (pin "3") (pinfunction "2_SIGNAL_TERMINAL_3") (pintype "passive"))
      (node (ref "U79") (pin "3") (pinfunction "2_SIGNAL_TERMINAL_3") (pintype "passive"))
      (node (ref "U80") (pin "3") (pinfunction "2_SIGNAL_TERMINAL_3") (pintype "passive"))
      (node (ref "U9") (pin "3") (pinfunction "2_SIGNAL_TERMINAL_3") (pintype "passive"))
      (node (ref "U90") (pin "3") (pinfunction "2_SIGNAL_TERMINAL_3") (pintype "passive"))
      (node (ref "U91") (pin "3") (pinfunction "2_SIGNAL_TERMINAL_3") (pintype "passive"))
      (node (ref "U92") (pin "3") (pinfunction "2_SIGNAL_TERMINAL_3") (pintype "passive"))
      (node (ref "U93") (pin "3") (pinfunction "2_SIGNAL_TERMINAL_3") (pintype "passive"))
      (node (ref "U94") (pin "3") (pinfunction "2_SIGNAL_TERMINAL_3") (pintype "passive"))
      (node (ref "U95") (pin "3") (pinfunction "2_SIGNAL_TERMINAL_3") (pintype "passive"))
      (node (ref "U96") (pin "3") (pinfunction "2_SIGNAL_TERMINAL_3") (pintype "passive"))
      (node (ref "U97") (pin "3") (pinfunction "2_SIGNAL_TERMINAL_3") (pintype "passive"))
      (node (ref "U98") (pin "3") (pinfunction "2_SIGNAL_TERMINAL_3") (pintype "passive"))
      (node (ref "U99") (pin "3") (pinfunction "2_SIGNAL_TERMINAL_3") (pintype "passive"))
    )
    (net (code "2") (name "Net-(U1-1_SIGNAL_TERMINAL)") (class "Default")
      (node (ref "J7") (pin "2") (pinfunction "2_2") (pintype "passive"))
      (node (ref "U1") (pin "1") (pinfunction "1_SIGNAL_TERMINAL_1") (pintype "passive"))
      (node (ref "U2") (pin "1") (pinfunction "1_SIGNAL_TERMINAL_1") (pintype "passive"))
      (node (ref "U3") (pin "1") (pinfunction "1_SIGNAL_TERMINAL_1") (pintype "passive"))
      (node (ref "U4") (pin "1") (pinfunction "1_SIGNAL_TERMINAL_1") (pintype "passive"))
    )
    (net (code "3") (name "Net-(U10-1_SIGNAL_TERMINAL)") (class "Default")
      (node (ref "J5") (pin "14") (pinfunction "14_14") (pintype "passive"))
      (node (ref "U10") (pin "1") (pinfunction "1_SIGNAL_TERMINAL_1") (pintype "passive"))
      (node (ref "U6") (pin "1") (pinfunction "1_SIGNAL_TERMINAL_1") (pintype "passive"))
      (node (ref "U9") (pin "1") (pinfunction "1_SIGNAL_TERMINAL_1") (pintype "passive"))
    )
    (net (code "4") (name "Net-(U11-1_SIGNAL_TERMINAL)") (class "Default")
      (node (ref "J6") (pin "10") (pinfunction "10_10") (pintype "passive"))
      (node (ref "U11") (pin "1") (pinfunction "1_SIGNAL_TERMINAL_1") (pintype "passive"))
      (node (ref "U12") (pin "1") (pinfunction "1_SIGNAL_TERMINAL_1") (pintype "passive"))
      (node (ref "U13") (pin "1") (pinfunction "1_SIGNAL_TERMINAL_1") (pintype "passive"))
    )
    (net (code "5") (name "Net-(U14-1_SIGNAL_TERMINAL)") (class "Default")
      (node (ref "J6") (pin "2") (pinfunction "2_2") (pintype "passive"))
      (node (ref "U14") (pin "1") (pinfunction "1_SIGNAL_TERMINAL_1") (pintype "passive"))
      (node (ref "U15") (pin "1") (pinfunction "1_SIGNAL_TERMINAL_1") (pintype "passive"))
      (node (ref "U16") (pin "1") (pinfunction "1_SIGNAL_TERMINAL_1") (pintype "passive"))
    )
    (net (code "6") (name "Net-(U21-1_SIGNAL_TERMINAL)") (class "Default")
      (node (ref "J7") (pin "4") (pinfunction "4_4") (pintype "passive"))
      (node (ref "U21") (pin "1") (pinfunction "1_SIGNAL_TERMINAL_1") (pintype "passive"))
      (node (ref "U22") (pin "1") (pinfunction "1_SIGNAL_TERMINAL_1") (pintype "passive"))
      (node (ref "U23") (pin "1") (pinfunction "1_SIGNAL_TERMINAL_1") (pintype "passive"))
      (node (ref "U24") (pin "1") (pinfunction "1_SIGNAL_TERMINAL_1") (pintype "passive"))
    )
    (net (code "7") (name "Net-(U25-1_SIGNAL_TERMINAL)") (class "Default")
      (node (ref "J4") (pin "12") (pinfunction "12_12") (pintype "passive"))
      (node (ref "U25") (pin "1") (pinfunction "1_SIGNAL_TERMINAL_1") (pintype "passive"))
      (node (ref "U26") (pin "1") (pinfunction "1_SIGNAL_TERMINAL_1") (pintype "passive"))
      (node (ref "U27") (pin "1") (pinfunction "1_SIGNAL_TERMINAL_1") (pintype "passive"))
      (node (ref "U28") (pin "1") (pinfunction "1_SIGNAL_TERMINAL_1") (pintype "passive"))
    )
    (net (code "8") (name "Net-(U29-1_SIGNAL_TERMINAL)") (class "Default")
      (node (ref "J4") (pin "16") (pinfunction "16_16") (pintype "passive"))
      (node (ref "U29") (pin "1") (pinfunction "1_SIGNAL_TERMINAL_1") (pintype "passive"))
      (node (ref "U30") (pin "1") (pinfunction "1_SIGNAL_TERMINAL_1") (pintype "passive"))
      (node (ref "U31") (pin "1") (pinfunction "1_SIGNAL_TERMINAL_1") (pintype "passive"))
      (node (ref "U32") (pin "1") (pinfunction "1_SIGNAL_TERMINAL_1") (pintype "passive"))
    )
    (net (code "9") (name "Net-(U33-1_SIGNAL_TERMINAL)") (class "Default")
      (node (ref "J4") (pin "2") (pinfunction "2_2") (pintype "passive"))
      (node (ref "U33") (pin "1") (pinfunction "1_SIGNAL_TERMINAL_1") (pintype "passive"))
      (node (ref "U34") (pin "1") (pinfunction "1_SIGNAL_TERMINAL_1") (pintype "passive"))
      (node (ref "U35") (pin "1") (pinfunction "1_SIGNAL_TERMINAL_1") (pintype "passive"))
      (node (ref "U36") (pin "1") (pinfunction "1_SIGNAL_TERMINAL_1") (pintype "passive"))
    )
    (net (code "10") (name "Net-(U37-1_SIGNAL_TERMINAL)") (class "Default")
      (node (ref "J4") (pin "4") (pinfunction "4_4") (pintype "passive"))
      (node (ref "U37") (pin "1") (pinfunction "1_SIGNAL_TERMINAL_1") (pintype "passive"))
      (node (ref "U38") (pin "1") (pinfunction "1_SIGNAL_TERMINAL_1") (pintype "passive"))
      (node (ref "U39") (pin "1") (pinfunction "1_SIGNAL_TERMINAL_1") (pintype "passive"))
      (node (ref "U40") (pin "1") (pinfunction "1_SIGNAL_TERMINAL_1") (pintype "passive"))
    )
    (net (code "11") (name "Net-(U41-1_SIGNAL_TERMINAL)") (class "Default")
      (node (ref "J4") (pin "10") (pinfunction "10_10") (pintype "passive"))
      (node (ref "U41") (pin "1") (pinfunction "1_SIGNAL_TERMINAL_1") (pintype "passive"))
      (node (ref "U42") (pin "1") (pinfunction "1_SIGNAL_TERMINAL_1") (pintype "passive"))
      (node (ref "U43") (pin "1") (pinfunction "1_SIGNAL_TERMINAL_1") (pintype "passive"))
      (node (ref "U44") (pin "1") (pinfunction "1_SIGNAL_TERMINAL_1") (pintype "passive"))
    )
    (net (code "12") (name "Net-(U45-1_SIGNAL_TERMINAL)") (class "Default")
      (node (ref "J4") (pin "14") (pinfunction "14_14") (pintype "passive"))
      (node (ref "U45") (pin "1") (pinfunction "1_SIGNAL_TERMINAL_1") (pintype "passive"))
      (node (ref "U46") (pin "1") (pinfunction "1_SIGNAL_TERMINAL_1") (pintype "passive"))
      (node (ref "U47") (pin "1") (pinfunction "1_SIGNAL_TERMINAL_1") (pintype "passive"))
      (node (ref "U48") (pin "1") (pinfunction "1_SIGNAL_TERMINAL_1") (pintype "passive"))
    )
    (net (code "13") (name "Net-(U49-1_SIGNAL_TERMINAL)") (class "Default")
      (node (ref "J5") (pin "16") (pinfunction "16_16") (pintype "passive"))
      (node (ref "U49") (pin "1") (pinfunction "1_SIGNAL_TERMINAL_1") (pintype "passive"))
      (node (ref "U50") (pin "1") (pinfunction "1_SIGNAL_TERMINAL_1") (pintype "passive"))
      (node (ref "U51") (pin "1") (pinfunction "1_SIGNAL_TERMINAL_1") (pintype "passive"))
      (node (ref "U52") (pin "1") (pinfunction "1_SIGNAL_TERMINAL_1") (pintype "passive"))
    )
    (net (code "14") (name "Net-(U53-1_SIGNAL_TERMINAL)") (class "Default")
      (node (ref "J8") (pin "2") (pinfunction "2_2") (pintype "passive"))
      (node (ref "U53") (pin "1") (pinfunction "1_SIGNAL_TERMINAL_1") (pintype "passive"))
      (node (ref "U54") (pin "1") (pinfunction "1_SIGNAL_TERMINAL_1") (pintype "passive"))
      (node (ref "U55") (pin "1") (pinfunction "1_SIGNAL_TERMINAL_1") (pintype "passive"))
      (node (ref "U56") (pin "1") (pinfunction "1_SIGNAL_TERMINAL_1") (pintype "passive"))
    )
    (net (code "15") (name "Net-(U57-1_SIGNAL_TERMINAL)") (class "Default")
      (node (ref "J7") (pin "16") (pinfunction "16_16") (pintype "passive"))
      (node (ref "U57") (pin "1") (pinfunction "1_SIGNAL_TERMINAL_1") (pintype "passive"))
      (node (ref "U58") (pin "1") (pinfunction "1_SIGNAL_TERMINAL_1") (pintype "passive"))
      (node (ref "U59") (pin "1") (pinfunction "1_SIGNAL_TERMINAL_1") (pintype "passive"))
      (node (ref "U60") (pin "1") (pinfunction "1_SIGNAL_TERMINAL_1") (pintype "passive"))
    )
    (net (code "16") (name "Net-(U61-1_SIGNAL_TERMINAL)") (class "Default")
      (node (ref "J7") (pin "14") (pinfunction "14_14") (pintype "passive"))
      (node (ref "U61") (pin "1") (pinfunction "1_SIGNAL_TERMINAL_1") (pintype "passive"))
      (node (ref "U62") (pin "1") (pinfunction "1_SIGNAL_TERMINAL_1") (pintype "passive"))
      (node (ref "U63") (pin "1") (pinfunction "1_SIGNAL_TERMINAL_1") (pintype "passive"))
      (node (ref "U64") (pin "1") (pinfunction "1_SIGNAL_TERMINAL_1") (pintype "passive"))
    )
    (net (code "17") (name "Net-(U65-1_SIGNAL_TERMINAL)") (class "Default")
      (node (ref "J7") (pin "12") (pinfunction "12_12") (pintype "passive"))
      (node (ref "U65") (pin "1") (pinfunction "1_SIGNAL_TERMINAL_1") (pintype "passive"))
      (node (ref "U66") (pin "1") (pinfunction "1_SIGNAL_TERMINAL_1") (pintype "passive"))
      (node (ref "U67") (pin "1") (pinfunction "1_SIGNAL_TERMINAL_1") (pintype "passive"))
      (node (ref "U68") (pin "1") (pinfunction "1_SIGNAL_TERMINAL_1") (pintype "passive"))
    )
    (net (code "18") (name "Net-(U69-1_SIGNAL_TERMINAL)") (class "Default")
      (node (ref "J7") (pin "10") (pinfunction "10_10") (pintype "passive"))
      (node (ref "U69") (pin "1") (pinfunction "1_SIGNAL_TERMINAL_1") (pintype "passive"))
      (node (ref "U70") (pin "1") (pinfunction "1_SIGNAL_TERMINAL_1") (pintype "passive"))
      (node (ref "U71") (pin "1") (pinfunction "1_SIGNAL_TERMINAL_1") (pintype "passive"))
      (node (ref "U72") (pin "1") (pinfunction "1_SIGNAL_TERMINAL_1") (pintype "passive"))
    )
    (net (code "19") (name "Net-(U73-1_SIGNAL_TERMINAL)") (class "Default")
      (node (ref "J7") (pin "8") (pinfunction "8_8") (pintype "passive"))
      (node (ref "U73") (pin "1") (pinfunction "1_SIGNAL_TERMINAL_1") (pintype "passive"))
      (node (ref "U74") (pin "1") (pinfunction "1_SIGNAL_TERMINAL_1") (pintype "passive"))
      (node (ref "U75") (pin "1") (pinfunction "1_SIGNAL_TERMINAL_1") (pintype "passive"))
      (node (ref "U76") (pin "1") (pinfunction "1_SIGNAL_TERMINAL_1") (pintype "passive"))
    )
    (net (code "20") (name "Net-(U77-1_SIGNAL_TERMINAL)") (class "Default")
      (node (ref "J7") (pin "6") (pinfunction "6_6") (pintype "passive"))
      (node (ref "U77") (pin "1") (pinfunction "1_SIGNAL_TERMINAL_1") (pintype "passive"))
      (node (ref "U78") (pin "1") (pinfunction "1_SIGNAL_TERMINAL_1") (pintype "passive"))
      (node (ref "U79") (pin "1") (pinfunction "1_SIGNAL_TERMINAL_1") (pintype "passive"))
      (node (ref "U80") (pin "1") (pinfunction "1_SIGNAL_TERMINAL_1") (pintype "passive"))
    )
    (net (code "21") (name "Net-(U92-1_SIGNAL_TERMINAL)") (class "Default")
      (node (ref "J5") (pin "12") (pinfunction "12_12") (pintype "passive"))
      (node (ref "U92") (pin "1") (pinfunction "1_SIGNAL_TERMINAL_1") (pintype "passive"))
      (node (ref "U93") (pin "1") (pinfunction "1_SIGNAL_TERMINAL_1") (pintype "passive"))
      (node (ref "U94") (pin "1") (pinfunction "1_SIGNAL_TERMINAL_1") (pintype "passive"))
      (node (ref "U95") (pin "1") (pinfunction "1_SIGNAL_TERMINAL_1") (pintype "passive"))
    )
    (net (code "22") (name "Net-(U96-1_SIGNAL_TERMINAL)") (class "Default")
      (node (ref "J8") (pin "4") (pinfunction "4_4") (pintype "passive"))
      (node (ref "U96") (pin "1") (pinfunction "1_SIGNAL_TERMINAL_1") (pintype "passive"))
      (node (ref "U97") (pin "1") (pinfunction "1_SIGNAL_TERMINAL_1") (pintype "passive"))
      (node (ref "U98") (pin "1") (pinfunction "1_SIGNAL_TERMINAL_1") (pintype "passive"))
      (node (ref "U99") (pin "1") (pinfunction "1_SIGNAL_TERMINAL_1") (pintype "passive"))
    )
    (net (code "23") (name "Net-(U100-1_SIGNAL_TERMINAL)") (class "Default")
      (node (ref "J8") (pin "14") (pinfunction "14_14") (pintype "passive"))
      (node (ref "U100") (pin "1") (pinfunction "1_SIGNAL_TERMINAL_1") (pintype "passive"))
      (node (ref "U101") (pin "1") (pinfunction "1_SIGNAL_TERMINAL_1") (pintype "passive"))
      (node (ref "U102") (pin "1") (pinfunction "1_SIGNAL_TERMINAL_1") (pintype "passive"))
      (node (ref "U103") (pin "1") (pinfunction "1_SIGNAL_TERMINAL_1") (pintype "passive"))
    )
    (net (code "24") (name "Net-(U104-1_SIGNAL_TERMINAL)") (class "Default")
      (node (ref "J8") (pin "16") (pinfunction "16_16") (pintype "passive"))
      (node (ref "U104") (pin "1") (pinfunction "1_SIGNAL_TERMINAL_1") (pintype "passive"))
      (node (ref "U105") (pin "1") (pinfunction "1_SIGNAL_TERMINAL_1") (pintype "passive"))
      (node (ref "U106") (pin "1") (pinfunction "1_SIGNAL_TERMINAL_1") (pintype "passive"))
      (node (ref "U107") (pin "1") (pinfunction "1_SIGNAL_TERMINAL_1") (pintype "passive"))
    )
    (net (code "25") (name "Net-(U108-1_SIGNAL_TERMINAL)") (class "Default")
      (node (ref "J5") (pin "6") (pinfunction "6_6") (pintype "passive"))
      (node (ref "U108") (pin "1") (pinfunction "1_SIGNAL_TERMINAL_1") (pintype "passive"))
      (node (ref "U109") (pin "1") (pinfunction "1_SIGNAL_TERMINAL_1") (pintype "passive"))
      (node (ref "U110") (pin "1") (pinfunction "1_SIGNAL_TERMINAL_1") (pintype "passive"))
      (node (ref "U111") (pin "1") (pinfunction "1_SIGNAL_TERMINAL_1") (pintype "passive"))
    )
    (net (code "26") (name "Net-(U112-1_SIGNAL_TERMINAL)") (class "Default")
      (node (ref "J6") (pin "14") (pinfunction "14_14") (pintype "passive"))
      (node (ref "U112") (pin "1") (pinfunction "1_SIGNAL_TERMINAL_1") (pintype "passive"))
      (node (ref "U113") (pin "1") (pinfunction "1_SIGNAL_TERMINAL_1") (pintype "passive"))
      (node (ref "U114") (pin "1") (pinfunction "1_SIGNAL_TERMINAL_1") (pintype "passive"))
      (node (ref "U115") (pin "1") (pinfunction "1_SIGNAL_TERMINAL_1") (pintype "passive"))
    )
    (net (code "27") (name "Net-(U116-1_SIGNAL_TERMINAL)") (class "Default")
      (node (ref "J4") (pin "8") (pinfunction "8_8") (pintype "passive"))
      (node (ref "U116") (pin "1") (pinfunction "1_SIGNAL_TERMINAL_1") (pintype "passive"))
      (node (ref "U117") (pin "1") (pinfunction "1_SIGNAL_TERMINAL_1") (pintype "passive"))
      (node (ref "U90") (pin "1") (pinfunction "1_SIGNAL_TERMINAL_1") (pintype "passive"))
      (node (ref "U91") (pin "1") (pinfunction "1_SIGNAL_TERMINAL_1") (pintype "passive"))
    )
    (net (code "28") (name "Net-(U118-1_SIGNAL_TERMINAL)") (class "Default")
      (node (ref "J3") (pin "4") (pinfunction "4_4") (pintype "passive"))
      (node (ref "U118") (pin "1") (pinfunction "1_SIGNAL_TERMINAL_1") (pintype "passive"))
      (node (ref "U170") (pin "1") (pinfunction "1_SIGNAL_TERMINAL_1") (pintype "passive"))
      (node (ref "U171") (pin "1") (pinfunction "1_SIGNAL_TERMINAL_1") (pintype "passive"))
      (node (ref "U172") (pin "1") (pinfunction "1_SIGNAL_TERMINAL_1") (pintype "passive"))
    )
    (net (code "29") (name "Net-(U119-1_SIGNAL_TERMINAL)") (class "Default")
      (node (ref "J5") (pin "4") (pinfunction "4_4") (pintype "passive"))
      (node (ref "U119") (pin "1") (pinfunction "1_SIGNAL_TERMINAL_1") (pintype "passive"))
      (node (ref "U120") (pin "1") (pinfunction "1_SIGNAL_TERMINAL_1") (pintype "passive"))
      (node (ref "U121") (pin "1") (pinfunction "1_SIGNAL_TERMINAL_1") (pintype "passive"))
      (node (ref "U122") (pin "1") (pinfunction "1_SIGNAL_TERMINAL_1") (pintype "passive"))
    )
    (net (code "30") (name "Net-(U123-1_SIGNAL_TERMINAL)") (class "Default")
      (node (ref "J5") (pin "10") (pinfunction "10_10") (pintype "passive"))
      (node (ref "U123") (pin "1") (pinfunction "1_SIGNAL_TERMINAL_1") (pintype "passive"))
      (node (ref "U124") (pin "1") (pinfunction "1_SIGNAL_TERMINAL_1") (pintype "passive"))
      (node (ref "U125") (pin "1") (pinfunction "1_SIGNAL_TERMINAL_1") (pintype "passive"))
      (node (ref "U126") (pin "1") (pinfunction "1_SIGNAL_TERMINAL_1") (pintype "passive"))
    )
    (net (code "31") (name "Net-(U127-1_SIGNAL_TERMINAL)") (class "Default")
      (node (ref "J8") (pin "6") (pinfunction "6_6") (pintype "passive"))
      (node (ref "U127") (pin "1") (pinfunction "1_SIGNAL_TERMINAL_1") (pintype "passive"))
      (node (ref "U128") (pin "1") (pinfunction "1_SIGNAL_TERMINAL_1") (pintype "passive"))
      (node (ref "U129") (pin "1") (pinfunction "1_SIGNAL_TERMINAL_1") (pintype "passive"))
      (node (ref "U130") (pin "1") (pinfunction "1_SIGNAL_TERMINAL_1") (pintype "passive"))
    )
    (net (code "32") (name "Net-(U131-1_SIGNAL_TERMINAL)") (class "Default")
      (node (ref "J8") (pin "12") (pinfunction "12_12") (pintype "passive"))
      (node (ref "U131") (pin "1") (pinfunction "1_SIGNAL_TERMINAL_1") (pintype "passive"))
      (node (ref "U132") (pin "1") (pinfunction "1_SIGNAL_TERMINAL_1") (pintype "passive"))
      (node (ref "U133") (pin "1") (pinfunction "1_SIGNAL_TERMINAL_1") (pintype "passive"))
      (node (ref "U134") (pin "1") (pinfunction "1_SIGNAL_TERMINAL_1") (pintype "passive"))
    )
    (net (code "33") (name "Net-(U135-1_SIGNAL_TERMINAL)") (class "Default")
      (node (ref "J6") (pin "16") (pinfunction "16_16") (pintype "passive"))
      (node (ref "U135") (pin "1") (pinfunction "1_SIGNAL_TERMINAL_1") (pintype "passive"))
      (node (ref "U136") (pin "1") (pinfunction "1_SIGNAL_TERMINAL_1") (pintype "passive"))
      (node (ref "U137") (pin "1") (pinfunction "1_SIGNAL_TERMINAL_1") (pintype "passive"))
      (node (ref "U138") (pin "1") (pinfunction "1_SIGNAL_TERMINAL_1") (pintype "passive"))
    )
    (net (code "34") (name "Net-(U139-1_SIGNAL_TERMINAL)") (class "Default")
      (node (ref "J6") (pin "8") (pinfunction "8_8") (pintype "passive"))
      (node (ref "U139") (pin "1") (pinfunction "1_SIGNAL_TERMINAL_1") (pintype "passive"))
      (node (ref "U140") (pin "1") (pinfunction "1_SIGNAL_TERMINAL_1") (pintype "passive"))
      (node (ref "U141") (pin "1") (pinfunction "1_SIGNAL_TERMINAL_1") (pintype "passive"))
      (node (ref "U142") (pin "1") (pinfunction "1_SIGNAL_TERMINAL_1") (pintype "passive"))
    )
    (net (code "35") (name "Net-(U143-1_SIGNAL_TERMINAL)") (class "Default")
      (node (ref "J5") (pin "2") (pinfunction "2_2") (pintype "passive"))
      (node (ref "U143") (pin "1") (pinfunction "1_SIGNAL_TERMINAL_1") (pintype "passive"))
      (node (ref "U144") (pin "1") (pinfunction "1_SIGNAL_TERMINAL_1") (pintype "passive"))
      (node (ref "U145") (pin "1") (pinfunction "1_SIGNAL_TERMINAL_1") (pintype "passive"))
      (node (ref "U149") (pin "1") (pinfunction "1_SIGNAL_TERMINAL_1") (pintype "passive"))
    )
    (net (code "36") (name "Net-(U146-1_SIGNAL_TERMINAL)") (class "Default")
      (node (ref "J6") (pin "4") (pinfunction "4_4") (pintype "passive"))
      (node (ref "U146") (pin "1") (pinfunction "1_SIGNAL_TERMINAL_1") (pintype "passive"))
      (node (ref "U147") (pin "1") (pinfunction "1_SIGNAL_TERMINAL_1") (pintype "passive"))
      (node (ref "U148") (pin "1") (pinfunction "1_SIGNAL_TERMINAL_1") (pintype "passive"))
    )
    (net (code "37") (name "Net-(U150-1_SIGNAL_TERMINAL)") (class "Default")
      (node (ref "J5") (pin "8") (pinfunction "8_8") (pintype "passive"))
      (node (ref "U150") (pin "1") (pinfunction "1_SIGNAL_TERMINAL_1") (pintype "passive"))
      (node (ref "U151") (pin "1") (pinfunction "1_SIGNAL_TERMINAL_1") (pintype "passive"))
      (node (ref "U152") (pin "1") (pinfunction "1_SIGNAL_TERMINAL_1") (pintype "passive"))
      (node (ref "U153") (pin "1") (pinfunction "1_SIGNAL_TERMINAL_1") (pintype "passive"))
    )
    (net (code "38") (name "Net-(U154-1_SIGNAL_TERMINAL)") (class "Default")
      (node (ref "J8") (pin "8") (pinfunction "8_8") (pintype "passive"))
      (node (ref "U154") (pin "1") (pinfunction "1_SIGNAL_TERMINAL_1") (pintype "passive"))
      (node (ref "U155") (pin "1") (pinfunction "1_SIGNAL_TERMINAL_1") (pintype "passive"))
      (node (ref "U156") (pin "1") (pinfunction "1_SIGNAL_TERMINAL_1") (pintype "passive"))
      (node (ref "U157") (pin "1") (pinfunction "1_SIGNAL_TERMINAL_1") (pintype "passive"))
    )
    (net (code "39") (name "Net-(U158-1_SIGNAL_TERMINAL)") (class "Default")
      (node (ref "J8") (pin "10") (pinfunction "10_10") (pintype "passive"))
      (node (ref "U158") (pin "1") (pinfunction "1_SIGNAL_TERMINAL_1") (pintype "passive"))
      (node (ref "U159") (pin "1") (pinfunction "1_SIGNAL_TERMINAL_1") (pintype "passive"))
      (node (ref "U160") (pin "1") (pinfunction "1_SIGNAL_TERMINAL_1") (pintype "passive"))
      (node (ref "U161") (pin "1") (pinfunction "1_SIGNAL_TERMINAL_1") (pintype "passive"))
    )
    (net (code "40") (name "Net-(U162-1_SIGNAL_TERMINAL)") (class "Default")
      (node (ref "J6") (pin "12") (pinfunction "12_12") (pintype "passive"))
      (node (ref "U162") (pin "1") (pinfunction "1_SIGNAL_TERMINAL_1") (pintype "passive"))
      (node (ref "U163") (pin "1") (pinfunction "1_SIGNAL_TERMINAL_1") (pintype "passive"))
      (node (ref "U164") (pin "1") (pinfunction "1_SIGNAL_TERMINAL_1") (pintype "passive"))
      (node (ref "U165") (pin "1") (pinfunction "1_SIGNAL_TERMINAL_1") (pintype "passive"))
    )
    (net (code "41") (name "Net-(U166-1_SIGNAL_TERMINAL)") (class "Default")
      (node (ref "J6") (pin "6") (pinfunction "6_6") (pintype "passive"))
      (node (ref "U166") (pin "1") (pinfunction "1_SIGNAL_TERMINAL_1") (pintype "passive"))
      (node (ref "U167") (pin "1") (pinfunction "1_SIGNAL_TERMINAL_1") (pintype "passive"))
      (node (ref "U168") (pin "1") (pinfunction "1_SIGNAL_TERMINAL_1") (pintype "passive"))
      (node (ref "U169") (pin "1") (pinfunction "1_SIGNAL_TERMINAL_1") (pintype "passive"))
    )
    (net (code "42") (name "Net-(U173-1_SIGNAL_TERMINAL)") (class "Default")
      (node (ref "J3") (pin "6") (pinfunction "6_6") (pintype "passive"))
      (node (ref "U173") (pin "1") (pinfunction "1_SIGNAL_TERMINAL_1") (pintype "passive"))
      (node (ref "U174") (pin "1") (pinfunction "1_SIGNAL_TERMINAL_1") (pintype "passive"))
      (node (ref "U175") (pin "1") (pinfunction "1_SIGNAL_TERMINAL_1") (pintype "passive"))
      (node (ref "U176") (pin "1") (pinfunction "1_SIGNAL_TERMINAL_1") (pintype "passive"))
    )
    (net (code "43") (name "Net-(U177-1_SIGNAL_TERMINAL)") (class "Default")
      (node (ref "J3") (pin "10") (pinfunction "10_10") (pintype "passive"))
      (node (ref "U177") (pin "1") (pinfunction "1_SIGNAL_TERMINAL_1") (pintype "passive"))
      (node (ref "U178") (pin "1") (pinfunction "1_SIGNAL_TERMINAL_1") (pintype "passive"))
      (node (ref "U179") (pin "1") (pinfunction "1_SIGNAL_TERMINAL_1") (pintype "passive"))
      (node (ref "U180") (pin "1") (pinfunction "1_SIGNAL_TERMINAL_1") (pintype "passive"))
    )
    (net (code "44") (name "Net-(U184-1_SIGNAL_TERMINAL)") (class "Default")
      (node (ref "J4") (pin "6") (pinfunction "6_6") (pintype "passive"))
      (node (ref "U184") (pin "1") (pinfunction "1_SIGNAL_TERMINAL_1") (pintype "passive"))
      (node (ref "U185") (pin "1") (pinfunction "1_SIGNAL_TERMINAL_1") (pintype "passive"))
      (node (ref "U186") (pin "1") (pinfunction "1_SIGNAL_TERMINAL_1") (pintype "passive"))
    )
    (net (code "45") (name "Net-(U192-1_SIGNAL_TERMINAL)") (class "Default")
      (node (ref "J2") (pin "8") (pinfunction "8_8") (pintype "passive"))
      (node (ref "U192") (pin "1") (pinfunction "1_SIGNAL_TERMINAL_1") (pintype "passive"))
      (node (ref "U193") (pin "1") (pinfunction "1_SIGNAL_TERMINAL_1") (pintype "passive"))
      (node (ref "U194") (pin "1") (pinfunction "1_SIGNAL_TERMINAL_1") (pintype "passive"))
      (node (ref "U195") (pin "1") (pinfunction "1_SIGNAL_TERMINAL_1") (pintype "passive"))
    )
    (net (code "46") (name "Net-(U196-1_SIGNAL_TERMINAL)") (class "Default")
      (node (ref "J2") (pin "14") (pinfunction "14_14") (pintype "passive"))
      (node (ref "U196") (pin "1") (pinfunction "1_SIGNAL_TERMINAL_1") (pintype "passive"))
      (node (ref "U197") (pin "1") (pinfunction "1_SIGNAL_TERMINAL_1") (pintype "passive"))
      (node (ref "U198") (pin "1") (pinfunction "1_SIGNAL_TERMINAL_1") (pintype "passive"))
      (node (ref "U199") (pin "1") (pinfunction "1_SIGNAL_TERMINAL_1") (pintype "passive"))
    )
    (net (code "47") (name "Net-(U200-1_SIGNAL_TERMINAL)") (class "Default")
      (node (ref "J3") (pin "8") (pinfunction "8_8") (pintype "passive"))
      (node (ref "U200") (pin "1") (pinfunction "1_SIGNAL_TERMINAL_1") (pintype "passive"))
      (node (ref "U201") (pin "1") (pinfunction "1_SIGNAL_TERMINAL_1") (pintype "passive"))
      (node (ref "U202") (pin "1") (pinfunction "1_SIGNAL_TERMINAL_1") (pintype "passive"))
      (node (ref "U203") (pin "1") (pinfunction "1_SIGNAL_TERMINAL_1") (pintype "passive"))
    )
    (net (code "48") (name "Net-(U204-1_SIGNAL_TERMINAL)") (class "Default")
      (node (ref "J3") (pin "12") (pinfunction "12_12") (pintype "passive"))
      (node (ref "U204") (pin "1") (pinfunction "1_SIGNAL_TERMINAL_1") (pintype "passive"))
      (node (ref "U205") (pin "1") (pinfunction "1_SIGNAL_TERMINAL_1") (pintype "passive"))
      (node (ref "U206") (pin "1") (pinfunction "1_SIGNAL_TERMINAL_1") (pintype "passive"))
      (node (ref "U207") (pin "1") (pinfunction "1_SIGNAL_TERMINAL_1") (pintype "passive"))
    )
    (net (code "49") (name "Net-(U208-1_SIGNAL_TERMINAL)") (class "Default")
      (node (ref "J1") (pin "14") (pinfunction "14_14") (pintype "passive"))
      (node (ref "U208") (pin "1") (pinfunction "1_SIGNAL_TERMINAL_1") (pintype "passive"))
      (node (ref "U209") (pin "1") (pinfunction "1_SIGNAL_TERMINAL_1") (pintype "passive"))
      (node (ref "U210") (pin "1") (pinfunction "1_SIGNAL_TERMINAL_1") (pintype "passive"))
      (node (ref "U211") (pin "1") (pinfunction "1_SIGNAL_TERMINAL_1") (pintype "passive"))
    )
    (net (code "50") (name "Net-(U212-1_SIGNAL_TERMINAL)") (class "Default")
      (node (ref "J1") (pin "8") (pinfunction "8_8") (pintype "passive"))
      (node (ref "U212") (pin "1") (pinfunction "1_SIGNAL_TERMINAL_1") (pintype "passive"))
      (node (ref "U213") (pin "1") (pinfunction "1_SIGNAL_TERMINAL_1") (pintype "passive"))
      (node (ref "U214") (pin "1") (pinfunction "1_SIGNAL_TERMINAL_1") (pintype "passive"))
      (node (ref "U215") (pin "1") (pinfunction "1_SIGNAL_TERMINAL_1") (pintype "passive"))
    )
    (net (code "51") (name "Net-(U216-1_SIGNAL_TERMINAL)") (class "Default")
      (node (ref "J2") (pin "4") (pinfunction "4_4") (pintype "passive"))
      (node (ref "U216") (pin "1") (pinfunction "1_SIGNAL_TERMINAL_1") (pintype "passive"))
      (node (ref "U217") (pin "1") (pinfunction "1_SIGNAL_TERMINAL_1") (pintype "passive"))
      (node (ref "U218") (pin "1") (pinfunction "1_SIGNAL_TERMINAL_1") (pintype "passive"))
      (node (ref "U222") (pin "1") (pinfunction "1_SIGNAL_TERMINAL_1") (pintype "passive"))
    )
    (net (code "52") (name "Net-(U219-1_SIGNAL_TERMINAL)") (class "Default")
      (node (ref "J1") (pin "6") (pinfunction "6_6") (pintype "passive"))
      (node (ref "U219") (pin "1") (pinfunction "1_SIGNAL_TERMINAL_1") (pintype "passive"))
      (node (ref "U220") (pin "1") (pinfunction "1_SIGNAL_TERMINAL_1") (pintype "passive"))
      (node (ref "U221") (pin "1") (pinfunction "1_SIGNAL_TERMINAL_1") (pintype "passive"))
    )
    (net (code "53") (name "Net-(U223-1_SIGNAL_TERMINAL)") (class "Default")
      (node (ref "J2") (pin "12") (pinfunction "12_12") (pintype "passive"))
      (node (ref "U223") (pin "1") (pinfunction "1_SIGNAL_TERMINAL_1") (pintype "passive"))
      (node (ref "U224") (pin "1") (pinfunction "1_SIGNAL_TERMINAL_1") (pintype "passive"))
      (node (ref "U225") (pin "1") (pinfunction "1_SIGNAL_TERMINAL_1") (pintype "passive"))
      (node (ref "U226") (pin "1") (pinfunction "1_SIGNAL_TERMINAL_1") (pintype "passive"))
    )
    (net (code "54") (name "Net-(U227-1_SIGNAL_TERMINAL)") (class "Default")
      (node (ref "J3") (pin "2") (pinfunction "2_2") (pintype "passive"))
      (node (ref "U227") (pin "1") (pinfunction "1_SIGNAL_TERMINAL_1") (pintype "passive"))
      (node (ref "U228") (pin "1") (pinfunction "1_SIGNAL_TERMINAL_1") (pintype "passive"))
      (node (ref "U229") (pin "1") (pinfunction "1_SIGNAL_TERMINAL_1") (pintype "passive"))
      (node (ref "U230") (pin "1") (pinfunction "1_SIGNAL_TERMINAL_1") (pintype "passive"))
    )
    (net (code "55") (name "Net-(U231-1_SIGNAL_TERMINAL)") (class "Default")
      (node (ref "J3") (pin "16") (pinfunction "16_16") (pintype "passive"))
      (node (ref "U231") (pin "1") (pinfunction "1_SIGNAL_TERMINAL_1") (pintype "passive"))
      (node (ref "U232") (pin "1") (pinfunction "1_SIGNAL_TERMINAL_1") (pintype "passive"))
      (node (ref "U233") (pin "1") (pinfunction "1_SIGNAL_TERMINAL_1") (pintype "passive"))
      (node (ref "U234") (pin "1") (pinfunction "1_SIGNAL_TERMINAL_1") (pintype "passive"))
    )
    (net (code "56") (name "Net-(U235-1_SIGNAL_TERMINAL)") (class "Default")
      (node (ref "J2") (pin "2") (pinfunction "2_2") (pintype "passive"))
      (node (ref "U235") (pin "1") (pinfunction "1_SIGNAL_TERMINAL_1") (pintype "passive"))
      (node (ref "U236") (pin "1") (pinfunction "1_SIGNAL_TERMINAL_1") (pintype "passive"))
      (node (ref "U237") (pin "1") (pinfunction "1_SIGNAL_TERMINAL_1") (pintype "passive"))
      (node (ref "U238") (pin "1") (pinfunction "1_SIGNAL_TERMINAL_1") (pintype "passive"))
    )
    (net (code "57") (name "Net-(U239-1_SIGNAL_TERMINAL)") (class "Default")
      (node (ref "J1") (pin "12") (pinfunction "12_12") (pintype "passive"))
      (node (ref "U239") (pin "1") (pinfunction "1_SIGNAL_TERMINAL_1") (pintype "passive"))
      (node (ref "U240") (pin "1") (pinfunction "1_SIGNAL_TERMINAL_1") (pintype "passive"))
      (node (ref "U241") (pin "1") (pinfunction "1_SIGNAL_TERMINAL_1") (pintype "passive"))
      (node (ref "U242") (pin "1") (pinfunction "1_SIGNAL_TERMINAL_1") (pintype "passive"))
    )
    (net (code "58") (name "Net-(U246-1_SIGNAL_TERMINAL)") (class "Default")
      (node (ref "J2") (pin "6") (pinfunction "6_6") (pintype "passive"))
      (node (ref "U246") (pin "1") (pinfunction "1_SIGNAL_TERMINAL_1") (pintype "passive"))
      (node (ref "U247") (pin "1") (pinfunction "1_SIGNAL_TERMINAL_1") (pintype "passive"))
      (node (ref "U248") (pin "1") (pinfunction "1_SIGNAL_TERMINAL_1") (pintype "passive"))
      (node (ref "U249") (pin "1") (pinfunction "1_SIGNAL_TERMINAL_1") (pintype "passive"))
    )
    (net (code "59") (name "Net-(U250-1_SIGNAL_TERMINAL)") (class "Default")
      (node (ref "J2") (pin "10") (pinfunction "10_10") (pintype "passive"))
      (node (ref "U250") (pin "1") (pinfunction "1_SIGNAL_TERMINAL_1") (pintype "passive"))
      (node (ref "U251") (pin "1") (pinfunction "1_SIGNAL_TERMINAL_1") (pintype "passive"))
      (node (ref "U252") (pin "1") (pinfunction "1_SIGNAL_TERMINAL_1") (pintype "passive"))
      (node (ref "U253") (pin "1") (pinfunction "1_SIGNAL_TERMINAL_1") (pintype "passive"))
    )
    (net (code "60") (name "Net-(U254-1_SIGNAL_TERMINAL)") (class "Default")
      (node (ref "J2") (pin "16") (pinfunction "16_16") (pintype "passive"))
      (node (ref "U254") (pin "1") (pinfunction "1_SIGNAL_TERMINAL_1") (pintype "passive"))
      (node (ref "U255") (pin "1") (pinfunction "1_SIGNAL_TERMINAL_1") (pintype "passive"))
      (node (ref "U256") (pin "1") (pinfunction "1_SIGNAL_TERMINAL_1") (pintype "passive"))
      (node (ref "U257") (pin "1") (pinfunction "1_SIGNAL_TERMINAL_1") (pintype "passive"))
    )
    (net (code "61") (name "Net-(U258-1_SIGNAL_TERMINAL)") (class "Default")
      (node (ref "J3") (pin "14") (pinfunction "14_14") (pintype "passive"))
      (node (ref "U258") (pin "1") (pinfunction "1_SIGNAL_TERMINAL_1") (pintype "passive"))
      (node (ref "U259") (pin "1") (pinfunction "1_SIGNAL_TERMINAL_1") (pintype "passive"))
      (node (ref "U260") (pin "1") (pinfunction "1_SIGNAL_TERMINAL_1") (pintype "passive"))
      (node (ref "U261") (pin "1") (pinfunction "1_SIGNAL_TERMINAL_1") (pintype "passive"))
    )
    (net (code "62") (name "Net-(U262-1_SIGNAL_TERMINAL)") (class "Default")
      (node (ref "J1") (pin "16") (pinfunction "16_16") (pintype "passive"))
      (node (ref "U262") (pin "1") (pinfunction "1_SIGNAL_TERMINAL_1") (pintype "passive"))
      (node (ref "U263") (pin "1") (pinfunction "1_SIGNAL_TERMINAL_1") (pintype "passive"))
      (node (ref "U264") (pin "1") (pinfunction "1_SIGNAL_TERMINAL_1") (pintype "passive"))
      (node (ref "U265") (pin "1") (pinfunction "1_SIGNAL_TERMINAL_1") (pintype "passive"))
    )
    (net (code "63") (name "Net-(U266-1_SIGNAL_TERMINAL)") (class "Default")
      (node (ref "J1") (pin "10") (pinfunction "10_10") (pintype "passive"))
      (node (ref "U266") (pin "1") (pinfunction "1_SIGNAL_TERMINAL_1") (pintype "passive"))
      (node (ref "U267") (pin "1") (pinfunction "1_SIGNAL_TERMINAL_1") (pintype "passive"))
      (node (ref "U268") (pin "1") (pinfunction "1_SIGNAL_TERMINAL_1") (pintype "passive"))
      (node (ref "U269") (pin "1") (pinfunction "1_SIGNAL_TERMINAL_1") (pintype "passive"))
    )
    (net (code "64") (name "Net-(U270-1_SIGNAL_TERMINAL)") (class "Default")
      (node (ref "J1") (pin "2") (pinfunction "2_2") (pintype "passive"))
      (node (ref "U270") (pin "1") (pinfunction "1_SIGNAL_TERMINAL_1") (pintype "passive"))
      (node (ref "U271") (pin "1") (pinfunction "1_SIGNAL_TERMINAL_1") (pintype "passive"))
      (node (ref "U272") (pin "1") (pinfunction "1_SIGNAL_TERMINAL_1") (pintype "passive"))
    )
    (net (code "65") (name "Net-(U273-1_SIGNAL_TERMINAL)") (class "Default")
      (node (ref "J1") (pin "4") (pinfunction "4_4") (pintype "passive"))
      (node (ref "U273") (pin "1") (pinfunction "1_SIGNAL_TERMINAL_1") (pintype "passive"))
      (node (ref "U274") (pin "1") (pinfunction "1_SIGNAL_TERMINAL_1") (pintype "passive"))
      (node (ref "U275") (pin "1") (pinfunction "1_SIGNAL_TERMINAL_1") (pintype "passive"))
    )
    (net (code "66") (name "unconnected-(J1-Pad3)") (class "Default")
      (node (ref "J1") (pin "3") (pinfunction "3_3") (pintype "passive"))
    )
    (net (code "67") (name "unconnected-(J1-Pad5)") (class "Default")
      (node (ref "J1") (pin "5") (pinfunction "5_5") (pintype "passive"))
    )
    (net (code "68") (name "unconnected-(J1-Pad7)") (class "Default")
      (node (ref "J1") (pin "7") (pinfunction "7_7") (pintype "passive"))
    )
    (net (code "69") (name "unconnected-(J1-Pad9)") (class "Default")
      (node (ref "J1") (pin "9") (pinfunction "9_9") (pintype "passive"))
    )
    (net (code "70") (name "unconnected-(J1-Pad11)") (class "Default")
      (node (ref "J1") (pin "11") (pinfunction "11_11") (pintype "passive"))
    )
    (net (code "71") (name "unconnected-(J1-Pad13)") (class "Default")
      (node (ref "J1") (pin "13") (pinfunction "13_13") (pintype "passive"))
    )
    (net (code "72") (name "unconnected-(J1-Pad15)") (class "Default")
      (node (ref "J1") (pin "15") (pinfunction "15_15") (pintype "passive"))
    )
    (net (code "73") (name "unconnected-(J2-Pad3)") (class "Default")
      (node (ref "J2") (pin "3") (pinfunction "3_3") (pintype "passive"))
    )
    (net (code "74") (name "unconnected-(J2-Pad5)") (class "Default")
      (node (ref "J2") (pin "5") (pinfunction "5_5") (pintype "passive"))
    )
    (net (code "75") (name "unconnected-(J2-Pad7)") (class "Default")
      (node (ref "J2") (pin "7") (pinfunction "7_7") (pintype "passive"))
    )
    (net (code "76") (name "unconnected-(J2-Pad9)") (class "Default")
      (node (ref "J2") (pin "9") (pinfunction "9_9") (pintype "passive"))
    )
    (net (code "77") (name "unconnected-(J2-Pad11)") (class "Default")
      (node (ref "J2") (pin "11") (pinfunction "11_11") (pintype "passive"))
    )
    (net (code "78") (name "unconnected-(J2-Pad13)") (class "Default")
      (node (ref "J2") (pin "13") (pinfunction "13_13") (pintype "passive"))
    )
    (net (code "79") (name "unconnected-(J2-Pad15)") (class "Default")
      (node (ref "J2") (pin "15") (pinfunction "15_15") (pintype "passive"))
    )
    (net (code "80") (name "unconnected-(J3-Pad1)") (class "Default")
      (node (ref "J3") (pin "1") (pinfunction "1_1") (pintype "passive"))
    )
    (net (code "81") (name "unconnected-(J3-Pad3)") (class "Default")
      (node (ref "J3") (pin "3") (pinfunction "3_3") (pintype "passive"))
    )
    (net (code "82") (name "unconnected-(J3-Pad5)") (class "Default")
      (node (ref "J3") (pin "5") (pinfunction "5_5") (pintype "passive"))
    )
    (net (code "83") (name "unconnected-(J3-Pad7)") (class "Default")
      (node (ref "J3") (pin "7") (pinfunction "7_7") (pintype "passive"))
    )
    (net (code "84") (name "unconnected-(J3-Pad9)") (class "Default")
      (node (ref "J3") (pin "9") (pinfunction "9_9") (pintype "passive"))
    )
    (net (code "85") (name "unconnected-(J3-Pad11)") (class "Default")
      (node (ref "J3") (pin "11") (pinfunction "11_11") (pintype "passive"))
    )
    (net (code "86") (name "unconnected-(J3-Pad13)") (class "Default")
      (node (ref "J3") (pin "13") (pinfunction "13_13") (pintype "passive"))
    )
    (net (code "87") (name "unconnected-(J3-Pad15)") (class "Default")
      (node (ref "J3") (pin "15") (pinfunction "15_15") (pintype "passive"))
    )
    (net (code "88") (name "unconnected-(J4-Pad3)") (class "Default")
      (node (ref "J4") (pin "3") (pinfunction "3_3") (pintype "passive"))
    )
    (net (code "89") (name "unconnected-(J4-Pad5)") (class "Default")
      (node (ref "J4") (pin "5") (pinfunction "5_5") (pintype "passive"))
    )
    (net (code "90") (name "unconnected-(J4-Pad7)") (class "Default")
      (node (ref "J4") (pin "7") (pinfunction "7_7") (pintype "passive"))
    )
    (net (code "91") (name "unconnected-(J4-Pad9)") (class "Default")
      (node (ref "J4") (pin "9") (pinfunction "9_9") (pintype "passive"))
    )
    (net (code "92") (name "unconnected-(J4-Pad11)") (class "Default")
      (node (ref "J4") (pin "11") (pinfunction "11_11") (pintype "passive"))
    )
    (net (code "93") (name "unconnected-(J4-Pad13)") (class "Default")
      (node (ref "J4") (pin "13") (pinfunction "13_13") (pintype "passive"))
    )
    (net (code "94") (name "unconnected-(J4-Pad15)") (class "Default")
      (node (ref "J4") (pin "15") (pinfunction "15_15") (pintype "passive"))
    )
    (net (code "95") (name "unconnected-(J6-Pad3)") (class "Default")
      (node (ref "J6") (pin "3") (pinfunction "3_3") (pintype "passive"))
    )
    (net (code "96") (name "unconnected-(J6-Pad5)") (class "Default")
      (node (ref "J6") (pin "5") (pinfunction "5_5") (pintype "passive"))
    )
    (net (code "97") (name "unconnected-(J6-Pad7)") (class "Default")
      (node (ref "J6") (pin "7") (pinfunction "7_7") (pintype "passive"))
    )
    (net (code "98") (name "unconnected-(J6-Pad9)") (class "Default")
      (node (ref "J6") (pin "9") (pinfunction "9_9") (pintype "passive"))
    )
    (net (code "99") (name "unconnected-(J6-Pad11)") (class "Default")
      (node (ref "J6") (pin "11") (pinfunction "11_11") (pintype "passive"))
    )
    (net (code "100") (name "unconnected-(J6-Pad13)") (class "Default")
      (node (ref "J6") (pin "13") (pinfunction "13_13") (pintype "passive"))
    )
    (net (code "101") (name "unconnected-(J6-Pad15)") (class "Default")
      (node (ref "J6") (pin "15") (pinfunction "15_15") (pintype "passive"))
    )
    (net (code "102") (name "unconnected-(J7-Pad1)") (class "Default")
      (node (ref "J7") (pin "1") (pinfunction "1_1") (pintype "passive"))
    )
    (net (code "103") (name "unconnected-(J7-Pad3)") (class "Default")
      (node (ref "J7") (pin "3") (pinfunction "3_3") (pintype "passive"))
    )
    (net (code "104") (name "unconnected-(J7-Pad5)") (class "Default")
      (node (ref "J7") (pin "5") (pinfunction "5_5") (pintype "passive"))
    )
    (net (code "105") (name "unconnected-(J7-Pad7)") (class "Default")
      (node (ref "J7") (pin "7") (pinfunction "7_7") (pintype "passive"))
    )
    (net (code "106") (name "unconnected-(J7-Pad9)") (class "Default")
      (node (ref "J7") (pin "9") (pinfunction "9_9") (pintype "passive"))
    )
    (net (code "107") (name "unconnected-(J7-Pad11)") (class "Default")
      (node (ref "J7") (pin "11") (pinfunction "11_11") (pintype "passive"))
    )
    (net (code "108") (name "unconnected-(J7-Pad13)") (class "Default")
      (node (ref "J7") (pin "13") (pinfunction "13_13") (pintype "passive"))
    )
    (net (code "109") (name "unconnected-(J7-Pad15)") (class "Default")
      (node (ref "J7") (pin "15") (pinfunction "15_15") (pintype "passive"))
    )
    (net (code "110") (name "unconnected-(J8-Pad3)") (class "Default")
      (node (ref "J8") (pin "3") (pinfunction "3_3") (pintype "passive"))
    )
    (net (code "111") (name "unconnected-(J8-Pad5)") (class "Default")
      (node (ref "J8") (pin "5") (pinfunction "5_5") (pintype "passive"))
    )
    (net (code "112") (name "unconnected-(J8-Pad7)") (class "Default")
      (node (ref "J8") (pin "7") (pinfunction "7_7") (pintype "passive"))
    )
    (net (code "113") (name "unconnected-(J8-Pad9)") (class "Default")
      (node (ref "J8") (pin "9") (pinfunction "9_9") (pintype "passive"))
    )
    (net (code "114") (name "unconnected-(J8-Pad11)") (class "Default")
      (node (ref "J8") (pin "11") (pinfunction "11_11") (pintype "passive"))
    )
    (net (code "115") (name "unconnected-(J8-Pad13)") (class "Default")
      (node (ref "J8") (pin "13") (pinfunction "13_13") (pintype "passive"))
    )
    (net (code "116") (name "unconnected-(J8-Pad15)") (class "Default")
      (node (ref "J8") (pin "15") (pinfunction "15_15") (pintype "passive"))
    )
    (net (code "117") (name "unconnected-(U1-1_NC-Pad2)") (class "Default")
      (node (ref "U1") (pin "2") (pinfunction "1_NC_2") (pintype "passive"))
    )
    (net (code "118") (name "unconnected-(U1-2_NC-Pad4)") (class "Default")
      (node (ref "U1") (pin "4") (pinfunction "2_NC_4") (pintype "passive"))
    )
    (net (code "119") (name "unconnected-(U2-1_NC-Pad2)") (class "Default")
      (node (ref "U2") (pin "2") (pinfunction "1_NC_2") (pintype "passive"))
    )
    (net (code "120") (name "unconnected-(U2-2_NC-Pad4)") (class "Default")
      (node (ref "U2") (pin "4") (pinfunction "2_NC_4") (pintype "passive"))
    )
    (net (code "121") (name "unconnected-(U3-1_NC-Pad2)") (class "Default")
      (node (ref "U3") (pin "2") (pinfunction "1_NC_2") (pintype "passive"))
    )
    (net (code "122") (name "unconnected-(U3-2_NC-Pad4)") (class "Default")
      (node (ref "U3") (pin "4") (pinfunction "2_NC_4") (pintype "passive"))
    )
    (net (code "123") (name "unconnected-(U4-1_NC-Pad2)") (class "Default")
      (node (ref "U4") (pin "2") (pinfunction "1_NC_2") (pintype "passive"))
    )
    (net (code "124") (name "unconnected-(U4-2_NC-Pad4)") (class "Default")
      (node (ref "U4") (pin "4") (pinfunction "2_NC_4") (pintype "passive"))
    )
    (net (code "125") (name "unconnected-(U6-1_NC-Pad2)") (class "Default")
      (node (ref "U6") (pin "2") (pinfunction "1_NC_2") (pintype "passive"))
    )
    (net (code "126") (name "unconnected-(U6-2_NC-Pad4)") (class "Default")
      (node (ref "U6") (pin "4") (pinfunction "2_NC_4") (pintype "passive"))
    )
    (net (code "127") (name "unconnected-(U9-1_NC-Pad2)") (class "Default")
      (node (ref "U9") (pin "2") (pinfunction "1_NC_2") (pintype "passive"))
    )
    (net (code "128") (name "unconnected-(U9-2_NC-Pad4)") (class "Default")
      (node (ref "U9") (pin "4") (pinfunction "2_NC_4") (pintype "passive"))
    )
    (net (code "129") (name "unconnected-(U10-1_NC-Pad2)") (class "Default")
      (node (ref "U10") (pin "2") (pinfunction "1_NC_2") (pintype "passive"))
    )
    (net (code "130") (name "unconnected-(U10-2_NC-Pad4)") (class "Default")
      (node (ref "U10") (pin "4") (pinfunction "2_NC_4") (pintype "passive"))
    )
    (net (code "131") (name "unconnected-(U11-1_NC-Pad2)") (class "Default")
      (node (ref "U11") (pin "2") (pinfunction "1_NC_2") (pintype "passive"))
    )
    (net (code "132") (name "unconnected-(U11-2_NC-Pad4)") (class "Default")
      (node (ref "U11") (pin "4") (pinfunction "2_NC_4") (pintype "passive"))
    )
    (net (code "133") (name "unconnected-(U11-2_SIGNAL_TERMINAL-Pad3)") (class "Default")
      (node (ref "U11") (pin "3") (pinfunction "2_SIGNAL_TERMINAL_3") (pintype "passive"))
    )
    (net (code "134") (name "unconnected-(U12-1_NC-Pad2)") (class "Default")
      (node (ref "U12") (pin "2") (pinfunction "1_NC_2") (pintype "passive"))
    )
    (net (code "135") (name "unconnected-(U12-2_NC-Pad4)") (class "Default")
      (node (ref "U12") (pin "4") (pinfunction "2_NC_4") (pintype "passive"))
    )
    (net (code "136") (name "unconnected-(U13-1_NC-Pad2)") (class "Default")
      (node (ref "U13") (pin "2") (pinfunction "1_NC_2") (pintype "passive"))
    )
    (net (code "137") (name "unconnected-(U13-2_NC-Pad4)") (class "Default")
      (node (ref "U13") (pin "4") (pinfunction "2_NC_4") (pintype "passive"))
    )
    (net (code "138") (name "unconnected-(U14-1_NC-Pad2)") (class "Default")
      (node (ref "U14") (pin "2") (pinfunction "1_NC_2") (pintype "passive"))
    )
    (net (code "139") (name "unconnected-(U14-2_NC-Pad4)") (class "Default")
      (node (ref "U14") (pin "4") (pinfunction "2_NC_4") (pintype "passive"))
    )
    (net (code "140") (name "unconnected-(U15-1_NC-Pad2)") (class "Default")
      (node (ref "U15") (pin "2") (pinfunction "1_NC_2") (pintype "passive"))
    )
    (net (code "141") (name "unconnected-(U15-2_NC-Pad4)") (class "Default")
      (node (ref "U15") (pin "4") (pinfunction "2_NC_4") (pintype "passive"))
    )
    (net (code "142") (name "unconnected-(U16-1_NC-Pad2)") (class "Default")
      (node (ref "U16") (pin "2") (pinfunction "1_NC_2") (pintype "passive"))
    )
    (net (code "143") (name "unconnected-(U16-2_NC-Pad4)") (class "Default")
      (node (ref "U16") (pin "4") (pinfunction "2_NC_4") (pintype "passive"))
    )
    (net (code "144") (name "unconnected-(U21-1_NC-Pad2)") (class "Default")
      (node (ref "U21") (pin "2") (pinfunction "1_NC_2") (pintype "passive"))
    )
    (net (code "145") (name "unconnected-(U21-2_NC-Pad4)") (class "Default")
      (node (ref "U21") (pin "4") (pinfunction "2_NC_4") (pintype "passive"))
    )
    (net (code "146") (name "unconnected-(U22-1_NC-Pad2)") (class "Default")
      (node (ref "U22") (pin "2") (pinfunction "1_NC_2") (pintype "passive"))
    )
    (net (code "147") (name "unconnected-(U22-2_NC-Pad4)") (class "Default")
      (node (ref "U22") (pin "4") (pinfunction "2_NC_4") (pintype "passive"))
    )
    (net (code "148") (name "unconnected-(U23-1_NC-Pad2)") (class "Default")
      (node (ref "U23") (pin "2") (pinfunction "1_NC_2") (pintype "passive"))
    )
    (net (code "149") (name "unconnected-(U23-2_NC-Pad4)") (class "Default")
      (node (ref "U23") (pin "4") (pinfunction "2_NC_4") (pintype "passive"))
    )
    (net (code "150") (name "unconnected-(U24-1_NC-Pad2)") (class "Default")
      (node (ref "U24") (pin "2") (pinfunction "1_NC_2") (pintype "passive"))
    )
    (net (code "151") (name "unconnected-(U24-2_NC-Pad4)") (class "Default")
      (node (ref "U24") (pin "4") (pinfunction "2_NC_4") (pintype "passive"))
    )
    (net (code "152") (name "unconnected-(U25-1_NC-Pad2)") (class "Default")
      (node (ref "U25") (pin "2") (pinfunction "1_NC_2") (pintype "passive"))
    )
    (net (code "153") (name "unconnected-(U25-2_NC-Pad4)") (class "Default")
      (node (ref "U25") (pin "4") (pinfunction "2_NC_4") (pintype "passive"))
    )
    (net (code "154") (name "unconnected-(U26-1_NC-Pad2)") (class "Default")
      (node (ref "U26") (pin "2") (pinfunction "1_NC_2") (pintype "passive"))
    )
    (net (code "155") (name "unconnected-(U26-2_NC-Pad4)") (class "Default")
      (node (ref "U26") (pin "4") (pinfunction "2_NC_4") (pintype "passive"))
    )
    (net (code "156") (name "unconnected-(U27-1_NC-Pad2)") (class "Default")
      (node (ref "U27") (pin "2") (pinfunction "1_NC_2") (pintype "passive"))
    )
    (net (code "157") (name "unconnected-(U27-2_NC-Pad4)") (class "Default")
      (node (ref "U27") (pin "4") (pinfunction "2_NC_4") (pintype "passive"))
    )
    (net (code "158") (name "unconnected-(U28-1_NC-Pad2)") (class "Default")
      (node (ref "U28") (pin "2") (pinfunction "1_NC_2") (pintype "passive"))
    )
    (net (code "159") (name "unconnected-(U28-2_NC-Pad4)") (class "Default")
      (node (ref "U28") (pin "4") (pinfunction "2_NC_4") (pintype "passive"))
    )
    (net (code "160") (name "unconnected-(U29-1_NC-Pad2)") (class "Default")
      (node (ref "U29") (pin "2") (pinfunction "1_NC_2") (pintype "passive"))
    )
    (net (code "161") (name "unconnected-(U29-2_NC-Pad4)") (class "Default")
      (node (ref "U29") (pin "4") (pinfunction "2_NC_4") (pintype "passive"))
    )
    (net (code "162") (name "unconnected-(U30-1_NC-Pad2)") (class "Default")
      (node (ref "U30") (pin "2") (pinfunction "1_NC_2") (pintype "passive"))
    )
    (net (code "163") (name "unconnected-(U30-2_NC-Pad4)") (class "Default")
      (node (ref "U30") (pin "4") (pinfunction "2_NC_4") (pintype "passive"))
    )
    (net (code "164") (name "unconnected-(U31-1_NC-Pad2)") (class "Default")
      (node (ref "U31") (pin "2") (pinfunction "1_NC_2") (pintype "passive"))
    )
    (net (code "165") (name "unconnected-(U31-2_NC-Pad4)") (class "Default")
      (node (ref "U31") (pin "4") (pinfunction "2_NC_4") (pintype "passive"))
    )
    (net (code "166") (name "unconnected-(U32-1_NC-Pad2)") (class "Default")
      (node (ref "U32") (pin "2") (pinfunction "1_NC_2") (pintype "passive"))
    )
    (net (code "167") (name "unconnected-(U32-2_NC-Pad4)") (class "Default")
      (node (ref "U32") (pin "4") (pinfunction "2_NC_4") (pintype "passive"))
    )
    (net (code "168") (name "unconnected-(U33-1_NC-Pad2)") (class "Default")
      (node (ref "U33") (pin "2") (pinfunction "1_NC_2") (pintype "passive"))
    )
    (net (code "169") (name "unconnected-(U33-2_NC-Pad4)") (class "Default")
      (node (ref "U33") (pin "4") (pinfunction "2_NC_4") (pintype "passive"))
    )
    (net (code "170") (name "unconnected-(U34-1_NC-Pad2)") (class "Default")
      (node (ref "U34") (pin "2") (pinfunction "1_NC_2") (pintype "passive"))
    )
    (net (code "171") (name "unconnected-(U34-2_NC-Pad4)") (class "Default")
      (node (ref "U34") (pin "4") (pinfunction "2_NC_4") (pintype "passive"))
    )
    (net (code "172") (name "unconnected-(U35-1_NC-Pad2)") (class "Default")
      (node (ref "U35") (pin "2") (pinfunction "1_NC_2") (pintype "passive"))
    )
    (net (code "173") (name "unconnected-(U35-2_NC-Pad4)") (class "Default")
      (node (ref "U35") (pin "4") (pinfunction "2_NC_4") (pintype "passive"))
    )
    (net (code "174") (name "unconnected-(U36-1_NC-Pad2)") (class "Default")
      (node (ref "U36") (pin "2") (pinfunction "1_NC_2") (pintype "passive"))
    )
    (net (code "175") (name "unconnected-(U36-2_NC-Pad4)") (class "Default")
      (node (ref "U36") (pin "4") (pinfunction "2_NC_4") (pintype "passive"))
    )
    (net (code "176") (name "unconnected-(U37-1_NC-Pad2)") (class "Default")
      (node (ref "U37") (pin "2") (pinfunction "1_NC_2") (pintype "passive"))
    )
    (net (code "177") (name "unconnected-(U37-2_NC-Pad4)") (class "Default")
      (node (ref "U37") (pin "4") (pinfunction "2_NC_4") (pintype "passive"))
    )
    (net (code "178") (name "unconnected-(U38-1_NC-Pad2)") (class "Default")
      (node (ref "U38") (pin "2") (pinfunction "1_NC_2") (pintype "passive"))
    )
    (net (code "179") (name "unconnected-(U38-2_NC-Pad4)") (class "Default")
      (node (ref "U38") (pin "4") (pinfunction "2_NC_4") (pintype "passive"))
    )
    (net (code "180") (name "unconnected-(U39-1_NC-Pad2)") (class "Default")
      (node (ref "U39") (pin "2") (pinfunction "1_NC_2") (pintype "passive"))
    )
    (net (code "181") (name "unconnected-(U39-2_NC-Pad4)") (class "Default")
      (node (ref "U39") (pin "4") (pinfunction "2_NC_4") (pintype "passive"))
    )
    (net (code "182") (name "unconnected-(U40-1_NC-Pad2)") (class "Default")
      (node (ref "U40") (pin "2") (pinfunction "1_NC_2") (pintype "passive"))
    )
    (net (code "183") (name "unconnected-(U40-2_NC-Pad4)") (class "Default")
      (node (ref "U40") (pin "4") (pinfunction "2_NC_4") (pintype "passive"))
    )
    (net (code "184") (name "unconnected-(U41-1_NC-Pad2)") (class "Default")
      (node (ref "U41") (pin "2") (pinfunction "1_NC_2") (pintype "passive"))
    )
    (net (code "185") (name "unconnected-(U41-2_NC-Pad4)") (class "Default")
      (node (ref "U41") (pin "4") (pinfunction "2_NC_4") (pintype "passive"))
    )
    (net (code "186") (name "unconnected-(U42-1_NC-Pad2)") (class "Default")
      (node (ref "U42") (pin "2") (pinfunction "1_NC_2") (pintype "passive"))
    )
    (net (code "187") (name "unconnected-(U42-2_NC-Pad4)") (class "Default")
      (node (ref "U42") (pin "4") (pinfunction "2_NC_4") (pintype "passive"))
    )
    (net (code "188") (name "unconnected-(U43-1_NC-Pad2)") (class "Default")
      (node (ref "U43") (pin "2") (pinfunction "1_NC_2") (pintype "passive"))
    )
    (net (code "189") (name "unconnected-(U43-2_NC-Pad4)") (class "Default")
      (node (ref "U43") (pin "4") (pinfunction "2_NC_4") (pintype "passive"))
    )
    (net (code "190") (name "unconnected-(U44-1_NC-Pad2)") (class "Default")
      (node (ref "U44") (pin "2") (pinfunction "1_NC_2") (pintype "passive"))
    )
    (net (code "191") (name "unconnected-(U44-2_NC-Pad4)") (class "Default")
      (node (ref "U44") (pin "4") (pinfunction "2_NC_4") (pintype "passive"))
    )
    (net (code "192") (name "unconnected-(U45-1_NC-Pad2)") (class "Default")
      (node (ref "U45") (pin "2") (pinfunction "1_NC_2") (pintype "passive"))
    )
    (net (code "193") (name "unconnected-(U45-2_NC-Pad4)") (class "Default")
      (node (ref "U45") (pin "4") (pinfunction "2_NC_4") (pintype "passive"))
    )
    (net (code "194") (name "unconnected-(U46-1_NC-Pad2)") (class "Default")
      (node (ref "U46") (pin "2") (pinfunction "1_NC_2") (pintype "passive"))
    )
    (net (code "195") (name "unconnected-(U46-2_NC-Pad4)") (class "Default")
      (node (ref "U46") (pin "4") (pinfunction "2_NC_4") (pintype "passive"))
    )
    (net (code "196") (name "unconnected-(U47-1_NC-Pad2)") (class "Default")
      (node (ref "U47") (pin "2") (pinfunction "1_NC_2") (pintype "passive"))
    )
    (net (code "197") (name "unconnected-(U47-2_NC-Pad4)") (class "Default")
      (node (ref "U47") (pin "4") (pinfunction "2_NC_4") (pintype "passive"))
    )
    (net (code "198") (name "unconnected-(U48-1_NC-Pad2)") (class "Default")
      (node (ref "U48") (pin "2") (pinfunction "1_NC_2") (pintype "passive"))
    )
    (net (code "199") (name "unconnected-(U48-2_NC-Pad4)") (class "Default")
      (node (ref "U48") (pin "4") (pinfunction "2_NC_4") (pintype "passive"))
    )
    (net (code "200") (name "unconnected-(U49-1_NC-Pad2)") (class "Default")
      (node (ref "U49") (pin "2") (pinfunction "1_NC_2") (pintype "passive"))
    )
    (net (code "201") (name "unconnected-(U49-2_NC-Pad4)") (class "Default")
      (node (ref "U49") (pin "4") (pinfunction "2_NC_4") (pintype "passive"))
    )
    (net (code "202") (name "unconnected-(U50-1_NC-Pad2)") (class "Default")
      (node (ref "U50") (pin "2") (pinfunction "1_NC_2") (pintype "passive"))
    )
    (net (code "203") (name "unconnected-(U50-2_NC-Pad4)") (class "Default")
      (node (ref "U50") (pin "4") (pinfunction "2_NC_4") (pintype "passive"))
    )
    (net (code "204") (name "unconnected-(U51-1_NC-Pad2)") (class "Default")
      (node (ref "U51") (pin "2") (pinfunction "1_NC_2") (pintype "passive"))
    )
    (net (code "205") (name "unconnected-(U51-2_NC-Pad4)") (class "Default")
      (node (ref "U51") (pin "4") (pinfunction "2_NC_4") (pintype "passive"))
    )
    (net (code "206") (name "unconnected-(U52-1_NC-Pad2)") (class "Default")
      (node (ref "U52") (pin "2") (pinfunction "1_NC_2") (pintype "passive"))
    )
    (net (code "207") (name "unconnected-(U52-2_NC-Pad4)") (class "Default")
      (node (ref "U52") (pin "4") (pinfunction "2_NC_4") (pintype "passive"))
    )
    (net (code "208") (name "unconnected-(U53-1_NC-Pad2)") (class "Default")
      (node (ref "U53") (pin "2") (pinfunction "1_NC_2") (pintype "passive"))
    )
    (net (code "209") (name "unconnected-(U53-2_NC-Pad4)") (class "Default")
      (node (ref "U53") (pin "4") (pinfunction "2_NC_4") (pintype "passive"))
    )
    (net (code "210") (name "unconnected-(U54-1_NC-Pad2)") (class "Default")
      (node (ref "U54") (pin "2") (pinfunction "1_NC_2") (pintype "passive"))
    )
    (net (code "211") (name "unconnected-(U54-2_NC-Pad4)") (class "Default")
      (node (ref "U54") (pin "4") (pinfunction "2_NC_4") (pintype "passive"))
    )
    (net (code "212") (name "unconnected-(U55-1_NC-Pad2)") (class "Default")
      (node (ref "U55") (pin "2") (pinfunction "1_NC_2") (pintype "passive"))
    )
    (net (code "213") (name "unconnected-(U55-2_NC-Pad4)") (class "Default")
      (node (ref "U55") (pin "4") (pinfunction "2_NC_4") (pintype "passive"))
    )
    (net (code "214") (name "unconnected-(U56-1_NC-Pad2)") (class "Default")
      (node (ref "U56") (pin "2") (pinfunction "1_NC_2") (pintype "passive"))
    )
    (net (code "215") (name "unconnected-(U56-2_NC-Pad4)") (class "Default")
      (node (ref "U56") (pin "4") (pinfunction "2_NC_4") (pintype "passive"))
    )
    (net (code "216") (name "unconnected-(U57-1_NC-Pad2)") (class "Default")
      (node (ref "U57") (pin "2") (pinfunction "1_NC_2") (pintype "passive"))
    )
    (net (code "217") (name "unconnected-(U57-2_NC-Pad4)") (class "Default")
      (node (ref "U57") (pin "4") (pinfunction "2_NC_4") (pintype "passive"))
    )
    (net (code "218") (name "unconnected-(U58-1_NC-Pad2)") (class "Default")
      (node (ref "U58") (pin "2") (pinfunction "1_NC_2") (pintype "passive"))
    )
    (net (code "219") (name "unconnected-(U58-2_NC-Pad4)") (class "Default")
      (node (ref "U58") (pin "4") (pinfunction "2_NC_4") (pintype "passive"))
    )
    (net (code "220") (name "unconnected-(U59-1_NC-Pad2)") (class "Default")
      (node (ref "U59") (pin "2") (pinfunction "1_NC_2") (pintype "passive"))
    )
    (net (code "221") (name "unconnected-(U59-2_NC-Pad4)") (class "Default")
      (node (ref "U59") (pin "4") (pinfunction "2_NC_4") (pintype "passive"))
    )
    (net (code "222") (name "unconnected-(U60-1_NC-Pad2)") (class "Default")
      (node (ref "U60") (pin "2") (pinfunction "1_NC_2") (pintype "passive"))
    )
    (net (code "223") (name "unconnected-(U60-2_NC-Pad4)") (class "Default")
      (node (ref "U60") (pin "4") (pinfunction "2_NC_4") (pintype "passive"))
    )
    (net (code "224") (name "unconnected-(U61-1_NC-Pad2)") (class "Default")
      (node (ref "U61") (pin "2") (pinfunction "1_NC_2") (pintype "passive"))
    )
    (net (code "225") (name "unconnected-(U61-2_NC-Pad4)") (class "Default")
      (node (ref "U61") (pin "4") (pinfunction "2_NC_4") (pintype "passive"))
    )
    (net (code "226") (name "unconnected-(U62-1_NC-Pad2)") (class "Default")
      (node (ref "U62") (pin "2") (pinfunction "1_NC_2") (pintype "passive"))
    )
    (net (code "227") (name "unconnected-(U62-2_NC-Pad4)") (class "Default")
      (node (ref "U62") (pin "4") (pinfunction "2_NC_4") (pintype "passive"))
    )
    (net (code "228") (name "unconnected-(U63-1_NC-Pad2)") (class "Default")
      (node (ref "U63") (pin "2") (pinfunction "1_NC_2") (pintype "passive"))
    )
    (net (code "229") (name "unconnected-(U63-2_NC-Pad4)") (class "Default")
      (node (ref "U63") (pin "4") (pinfunction "2_NC_4") (pintype "passive"))
    )
    (net (code "230") (name "unconnected-(U64-1_NC-Pad2)") (class "Default")
      (node (ref "U64") (pin "2") (pinfunction "1_NC_2") (pintype "passive"))
    )
    (net (code "231") (name "unconnected-(U64-2_NC-Pad4)") (class "Default")
      (node (ref "U64") (pin "4") (pinfunction "2_NC_4") (pintype "passive"))
    )
    (net (code "232") (name "unconnected-(U65-1_NC-Pad2)") (class "Default")
      (node (ref "U65") (pin "2") (pinfunction "1_NC_2") (pintype "passive"))
    )
    (net (code "233") (name "unconnected-(U65-2_NC-Pad4)") (class "Default")
      (node (ref "U65") (pin "4") (pinfunction "2_NC_4") (pintype "passive"))
    )
    (net (code "234") (name "unconnected-(U66-1_NC-Pad2)") (class "Default")
      (node (ref "U66") (pin "2") (pinfunction "1_NC_2") (pintype "passive"))
    )
    (net (code "235") (name "unconnected-(U66-2_NC-Pad4)") (class "Default")
      (node (ref "U66") (pin "4") (pinfunction "2_NC_4") (pintype "passive"))
    )
    (net (code "236") (name "unconnected-(U67-1_NC-Pad2)") (class "Default")
      (node (ref "U67") (pin "2") (pinfunction "1_NC_2") (pintype "passive"))
    )
    (net (code "237") (name "unconnected-(U67-2_NC-Pad4)") (class "Default")
      (node (ref "U67") (pin "4") (pinfunction "2_NC_4") (pintype "passive"))
    )
    (net (code "238") (name "unconnected-(U68-1_NC-Pad2)") (class "Default")
      (node (ref "U68") (pin "2") (pinfunction "1_NC_2") (pintype "passive"))
    )
    (net (code "239") (name "unconnected-(U68-2_NC-Pad4)") (class "Default")
      (node (ref "U68") (pin "4") (pinfunction "2_NC_4") (pintype "passive"))
    )
    (net (code "240") (name "unconnected-(U69-1_NC-Pad2)") (class "Default")
      (node (ref "U69") (pin "2") (pinfunction "1_NC_2") (pintype "passive"))
    )
    (net (code "241") (name "unconnected-(U69-2_NC-Pad4)") (class "Default")
      (node (ref "U69") (pin "4") (pinfunction "2_NC_4") (pintype "passive"))
    )
    (net (code "242") (name "unconnected-(U70-1_NC-Pad2)") (class "Default")
      (node (ref "U70") (pin "2") (pinfunction "1_NC_2") (pintype "passive"))
    )
    (net (code "243") (name "unconnected-(U70-2_NC-Pad4)") (class "Default")
      (node (ref "U70") (pin "4") (pinfunction "2_NC_4") (pintype "passive"))
    )
    (net (code "244") (name "unconnected-(U71-1_NC-Pad2)") (class "Default")
      (node (ref "U71") (pin "2") (pinfunction "1_NC_2") (pintype "passive"))
    )
    (net (code "245") (name "unconnected-(U71-2_NC-Pad4)") (class "Default")
      (node (ref "U71") (pin "4") (pinfunction "2_NC_4") (pintype "passive"))
    )
    (net (code "246") (name "unconnected-(U72-1_NC-Pad2)") (class "Default")
      (node (ref "U72") (pin "2") (pinfunction "1_NC_2") (pintype "passive"))
    )
    (net (code "247") (name "unconnected-(U72-2_NC-Pad4)") (class "Default")
      (node (ref "U72") (pin "4") (pinfunction "2_NC_4") (pintype "passive"))
    )
    (net (code "248") (name "unconnected-(U73-1_NC-Pad2)") (class "Default")
      (node (ref "U73") (pin "2") (pinfunction "1_NC_2") (pintype "passive"))
    )
    (net (code "249") (name "unconnected-(U73-2_NC-Pad4)") (class "Default")
      (node (ref "U73") (pin "4") (pinfunction "2_NC_4") (pintype "passive"))
    )
    (net (code "250") (name "unconnected-(U74-1_NC-Pad2)") (class "Default")
      (node (ref "U74") (pin "2") (pinfunction "1_NC_2") (pintype "passive"))
    )
    (net (code "251") (name "unconnected-(U74-2_NC-Pad4)") (class "Default")
      (node (ref "U74") (pin "4") (pinfunction "2_NC_4") (pintype "passive"))
    )
    (net (code "252") (name "unconnected-(U75-1_NC-Pad2)") (class "Default")
      (node (ref "U75") (pin "2") (pinfunction "1_NC_2") (pintype "passive"))
    )
    (net (code "253") (name "unconnected-(U75-2_NC-Pad4)") (class "Default")
      (node (ref "U75") (pin "4") (pinfunction "2_NC_4") (pintype "passive"))
    )
    (net (code "254") (name "unconnected-(U76-1_NC-Pad2)") (class "Default")
      (node (ref "U76") (pin "2") (pinfunction "1_NC_2") (pintype "passive"))
    )
    (net (code "255") (name "unconnected-(U76-2_NC-Pad4)") (class "Default")
      (node (ref "U76") (pin "4") (pinfunction "2_NC_4") (pintype "passive"))
    )
    (net (code "256") (name "unconnected-(U77-1_NC-Pad2)") (class "Default")
      (node (ref "U77") (pin "2") (pinfunction "1_NC_2") (pintype "passive"))
    )
    (net (code "257") (name "unconnected-(U77-2_NC-Pad4)") (class "Default")
      (node (ref "U77") (pin "4") (pinfunction "2_NC_4") (pintype "passive"))
    )
    (net (code "258") (name "unconnected-(U78-1_NC-Pad2)") (class "Default")
      (node (ref "U78") (pin "2") (pinfunction "1_NC_2") (pintype "passive"))
    )
    (net (code "259") (name "unconnected-(U78-2_NC-Pad4)") (class "Default")
      (node (ref "U78") (pin "4") (pinfunction "2_NC_4") (pintype "passive"))
    )
    (net (code "260") (name "unconnected-(U79-1_NC-Pad2)") (class "Default")
      (node (ref "U79") (pin "2") (pinfunction "1_NC_2") (pintype "passive"))
    )
    (net (code "261") (name "unconnected-(U79-2_NC-Pad4)") (class "Default")
      (node (ref "U79") (pin "4") (pinfunction "2_NC_4") (pintype "passive"))
    )
    (net (code "262") (name "unconnected-(U80-1_NC-Pad2)") (class "Default")
      (node (ref "U80") (pin "2") (pinfunction "1_NC_2") (pintype "passive"))
    )
    (net (code "263") (name "unconnected-(U80-2_NC-Pad4)") (class "Default")
      (node (ref "U80") (pin "4") (pinfunction "2_NC_4") (pintype "passive"))
    )
    (net (code "264") (name "unconnected-(U90-1_NC-Pad2)") (class "Default")
      (node (ref "U90") (pin "2") (pinfunction "1_NC_2") (pintype "passive"))
    )
    (net (code "265") (name "unconnected-(U90-2_NC-Pad4)") (class "Default")
      (node (ref "U90") (pin "4") (pinfunction "2_NC_4") (pintype "passive"))
    )
    (net (code "266") (name "unconnected-(U91-1_NC-Pad2)") (class "Default")
      (node (ref "U91") (pin "2") (pinfunction "1_NC_2") (pintype "passive"))
    )
    (net (code "267") (name "unconnected-(U91-2_NC-Pad4)") (class "Default")
      (node (ref "U91") (pin "4") (pinfunction "2_NC_4") (pintype "passive"))
    )
    (net (code "268") (name "unconnected-(U92-1_NC-Pad2)") (class "Default")
      (node (ref "U92") (pin "2") (pinfunction "1_NC_2") (pintype "passive"))
    )
    (net (code "269") (name "unconnected-(U92-2_NC-Pad4)") (class "Default")
      (node (ref "U92") (pin "4") (pinfunction "2_NC_4") (pintype "passive"))
    )
    (net (code "270") (name "unconnected-(U93-1_NC-Pad2)") (class "Default")
      (node (ref "U93") (pin "2") (pinfunction "1_NC_2") (pintype "passive"))
    )
    (net (code "271") (name "unconnected-(U93-2_NC-Pad4)") (class "Default")
      (node (ref "U93") (pin "4") (pinfunction "2_NC_4") (pintype "passive"))
    )
    (net (code "272") (name "unconnected-(U94-1_NC-Pad2)") (class "Default")
      (node (ref "U94") (pin "2") (pinfunction "1_NC_2") (pintype "passive"))
    )
    (net (code "273") (name "unconnected-(U94-2_NC-Pad4)") (class "Default")
      (node (ref "U94") (pin "4") (pinfunction "2_NC_4") (pintype "passive"))
    )
    (net (code "274") (name "unconnected-(U95-1_NC-Pad2)") (class "Default")
      (node (ref "U95") (pin "2") (pinfunction "1_NC_2") (pintype "passive"))
    )
    (net (code "275") (name "unconnected-(U95-2_NC-Pad4)") (class "Default")
      (node (ref "U95") (pin "4") (pinfunction "2_NC_4") (pintype "passive"))
    )
    (net (code "276") (name "unconnected-(U96-1_NC-Pad2)") (class "Default")
      (node (ref "U96") (pin "2") (pinfunction "1_NC_2") (pintype "passive"))
    )
    (net (code "277") (name "unconnected-(U96-2_NC-Pad4)") (class "Default")
      (node (ref "U96") (pin "4") (pinfunction "2_NC_4") (pintype "passive"))
    )
    (net (code "278") (name "unconnected-(U97-1_NC-Pad2)") (class "Default")
      (node (ref "U97") (pin "2") (pinfunction "1_NC_2") (pintype "passive"))
    )
    (net (code "279") (name "unconnected-(U97-2_NC-Pad4)") (class "Default")
      (node (ref "U97") (pin "4") (pinfunction "2_NC_4") (pintype "passive"))
    )
    (net (code "280") (name "unconnected-(U98-1_NC-Pad2)") (class "Default")
      (node (ref "U98") (pin "2") (pinfunction "1_NC_2") (pintype "passive"))
    )
    (net (code "281") (name "unconnected-(U98-2_NC-Pad4)") (class "Default")
      (node (ref "U98") (pin "4") (pinfunction "2_NC_4") (pintype "passive"))
    )
    (net (code "282") (name "unconnected-(U99-1_NC-Pad2)") (class "Default")
      (node (ref "U99") (pin "2") (pinfunction "1_NC_2") (pintype "passive"))
    )
    (net (code "283") (name "unconnected-(U99-2_NC-Pad4)") (class "Default")
      (node (ref "U99") (pin "4") (pinfunction "2_NC_4") (pintype "passive"))
    )
    (net (code "284") (name "unconnected-(U100-1_NC-Pad2)") (class "Default")
      (node (ref "U100") (pin "2") (pinfunction "1_NC_2") (pintype "passive"))
    )
    (net (code "285") (name "unconnected-(U100-2_NC-Pad4)") (class "Default")
      (node (ref "U100") (pin "4") (pinfunction "2_NC_4") (pintype "passive"))
    )
    (net (code "286") (name "unconnected-(U101-1_NC-Pad2)") (class "Default")
      (node (ref "U101") (pin "2") (pinfunction "1_NC_2") (pintype "passive"))
    )
    (net (code "287") (name "unconnected-(U101-2_NC-Pad4)") (class "Default")
      (node (ref "U101") (pin "4") (pinfunction "2_NC_4") (pintype "passive"))
    )
    (net (code "288") (name "unconnected-(U102-1_NC-Pad2)") (class "Default")
      (node (ref "U102") (pin "2") (pinfunction "1_NC_2") (pintype "passive"))
    )
    (net (code "289") (name "unconnected-(U102-2_NC-Pad4)") (class "Default")
      (node (ref "U102") (pin "4") (pinfunction "2_NC_4") (pintype "passive"))
    )
    (net (code "290") (name "unconnected-(U103-1_NC-Pad2)") (class "Default")
      (node (ref "U103") (pin "2") (pinfunction "1_NC_2") (pintype "passive"))
    )
    (net (code "291") (name "unconnected-(U103-2_NC-Pad4)") (class "Default")
      (node (ref "U103") (pin "4") (pinfunction "2_NC_4") (pintype "passive"))
    )
    (net (code "292") (name "unconnected-(U104-1_NC-Pad2)") (class "Default")
      (node (ref "U104") (pin "2") (pinfunction "1_NC_2") (pintype "passive"))
    )
    (net (code "293") (name "unconnected-(U104-2_NC-Pad4)") (class "Default")
      (node (ref "U104") (pin "4") (pinfunction "2_NC_4") (pintype "passive"))
    )
    (net (code "294") (name "unconnected-(U105-1_NC-Pad2)") (class "Default")
      (node (ref "U105") (pin "2") (pinfunction "1_NC_2") (pintype "passive"))
    )
    (net (code "295") (name "unconnected-(U105-2_NC-Pad4)") (class "Default")
      (node (ref "U105") (pin "4") (pinfunction "2_NC_4") (pintype "passive"))
    )
    (net (code "296") (name "unconnected-(U106-1_NC-Pad2)") (class "Default")
      (node (ref "U106") (pin "2") (pinfunction "1_NC_2") (pintype "passive"))
    )
    (net (code "297") (name "unconnected-(U106-2_NC-Pad4)") (class "Default")
      (node (ref "U106") (pin "4") (pinfunction "2_NC_4") (pintype "passive"))
    )
    (net (code "298") (name "unconnected-(U107-1_NC-Pad2)") (class "Default")
      (node (ref "U107") (pin "2") (pinfunction "1_NC_2") (pintype "passive"))
    )
    (net (code "299") (name "unconnected-(U107-2_NC-Pad4)") (class "Default")
      (node (ref "U107") (pin "4") (pinfunction "2_NC_4") (pintype "passive"))
    )
    (net (code "300") (name "unconnected-(U108-1_NC-Pad2)") (class "Default")
      (node (ref "U108") (pin "2") (pinfunction "1_NC_2") (pintype "passive"))
    )
    (net (code "301") (name "unconnected-(U108-2_NC-Pad4)") (class "Default")
      (node (ref "U108") (pin "4") (pinfunction "2_NC_4") (pintype "passive"))
    )
    (net (code "302") (name "unconnected-(U109-1_NC-Pad2)") (class "Default")
      (node (ref "U109") (pin "2") (pinfunction "1_NC_2") (pintype "passive"))
    )
    (net (code "303") (name "unconnected-(U109-2_NC-Pad4)") (class "Default")
      (node (ref "U109") (pin "4") (pinfunction "2_NC_4") (pintype "passive"))
    )
    (net (code "304") (name "unconnected-(U110-1_NC-Pad2)") (class "Default")
      (node (ref "U110") (pin "2") (pinfunction "1_NC_2") (pintype "passive"))
    )
    (net (code "305") (name "unconnected-(U110-2_NC-Pad4)") (class "Default")
      (node (ref "U110") (pin "4") (pinfunction "2_NC_4") (pintype "passive"))
    )
    (net (code "306") (name "unconnected-(U111-1_NC-Pad2)") (class "Default")
      (node (ref "U111") (pin "2") (pinfunction "1_NC_2") (pintype "passive"))
    )
    (net (code "307") (name "unconnected-(U111-2_NC-Pad4)") (class "Default")
      (node (ref "U111") (pin "4") (pinfunction "2_NC_4") (pintype "passive"))
    )
    (net (code "308") (name "unconnected-(U112-1_NC-Pad2)") (class "Default")
      (node (ref "U112") (pin "2") (pinfunction "1_NC_2") (pintype "passive"))
    )
    (net (code "309") (name "unconnected-(U112-2_NC-Pad4)") (class "Default")
      (node (ref "U112") (pin "4") (pinfunction "2_NC_4") (pintype "passive"))
    )
    (net (code "310") (name "unconnected-(U113-1_NC-Pad2)") (class "Default")
      (node (ref "U113") (pin "2") (pinfunction "1_NC_2") (pintype "passive"))
    )
    (net (code "311") (name "unconnected-(U113-2_NC-Pad4)") (class "Default")
      (node (ref "U113") (pin "4") (pinfunction "2_NC_4") (pintype "passive"))
    )
    (net (code "312") (name "unconnected-(U114-1_NC-Pad2)") (class "Default")
      (node (ref "U114") (pin "2") (pinfunction "1_NC_2") (pintype "passive"))
    )
    (net (code "313") (name "unconnected-(U114-2_NC-Pad4)") (class "Default")
      (node (ref "U114") (pin "4") (pinfunction "2_NC_4") (pintype "passive"))
    )
    (net (code "314") (name "unconnected-(U115-1_NC-Pad2)") (class "Default")
      (node (ref "U115") (pin "2") (pinfunction "1_NC_2") (pintype "passive"))
    )
    (net (code "315") (name "unconnected-(U115-2_NC-Pad4)") (class "Default")
      (node (ref "U115") (pin "4") (pinfunction "2_NC_4") (pintype "passive"))
    )
    (net (code "316") (name "unconnected-(U116-1_NC-Pad2)") (class "Default")
      (node (ref "U116") (pin "2") (pinfunction "1_NC_2") (pintype "passive"))
    )
    (net (code "317") (name "unconnected-(U116-2_NC-Pad4)") (class "Default")
      (node (ref "U116") (pin "4") (pinfunction "2_NC_4") (pintype "passive"))
    )
    (net (code "318") (name "unconnected-(U117-1_NC-Pad2)") (class "Default")
      (node (ref "U117") (pin "2") (pinfunction "1_NC_2") (pintype "passive"))
    )
    (net (code "319") (name "unconnected-(U117-2_NC-Pad4)") (class "Default")
      (node (ref "U117") (pin "4") (pinfunction "2_NC_4") (pintype "passive"))
    )
    (net (code "320") (name "unconnected-(U118-1_NC-Pad2)") (class "Default")
      (node (ref "U118") (pin "2") (pinfunction "1_NC_2") (pintype "passive"))
    )
    (net (code "321") (name "unconnected-(U118-2_NC-Pad4)") (class "Default")
      (node (ref "U118") (pin "4") (pinfunction "2_NC_4") (pintype "passive"))
    )
    (net (code "322") (name "unconnected-(U119-1_NC-Pad2)") (class "Default")
      (node (ref "U119") (pin "2") (pinfunction "1_NC_2") (pintype "passive"))
    )
    (net (code "323") (name "unconnected-(U119-2_NC-Pad4)") (class "Default")
      (node (ref "U119") (pin "4") (pinfunction "2_NC_4") (pintype "passive"))
    )
    (net (code "324") (name "unconnected-(U120-1_NC-Pad2)") (class "Default")
      (node (ref "U120") (pin "2") (pinfunction "1_NC_2") (pintype "passive"))
    )
    (net (code "325") (name "unconnected-(U120-2_NC-Pad4)") (class "Default")
      (node (ref "U120") (pin "4") (pinfunction "2_NC_4") (pintype "passive"))
    )
    (net (code "326") (name "unconnected-(U121-1_NC-Pad2)") (class "Default")
      (node (ref "U121") (pin "2") (pinfunction "1_NC_2") (pintype "passive"))
    )
    (net (code "327") (name "unconnected-(U121-2_NC-Pad4)") (class "Default")
      (node (ref "U121") (pin "4") (pinfunction "2_NC_4") (pintype "passive"))
    )
    (net (code "328") (name "unconnected-(U122-1_NC-Pad2)") (class "Default")
      (node (ref "U122") (pin "2") (pinfunction "1_NC_2") (pintype "passive"))
    )
    (net (code "329") (name "unconnected-(U122-2_NC-Pad4)") (class "Default")
      (node (ref "U122") (pin "4") (pinfunction "2_NC_4") (pintype "passive"))
    )
    (net (code "330") (name "unconnected-(U123-1_NC-Pad2)") (class "Default")
      (node (ref "U123") (pin "2") (pinfunction "1_NC_2") (pintype "passive"))
    )
    (net (code "331") (name "unconnected-(U123-2_NC-Pad4)") (class "Default")
      (node (ref "U123") (pin "4") (pinfunction "2_NC_4") (pintype "passive"))
    )
    (net (code "332") (name "unconnected-(U124-1_NC-Pad2)") (class "Default")
      (node (ref "U124") (pin "2") (pinfunction "1_NC_2") (pintype "passive"))
    )
    (net (code "333") (name "unconnected-(U124-2_NC-Pad4)") (class "Default")
      (node (ref "U124") (pin "4") (pinfunction "2_NC_4") (pintype "passive"))
    )
    (net (code "334") (name "unconnected-(U125-1_NC-Pad2)") (class "Default")
      (node (ref "U125") (pin "2") (pinfunction "1_NC_2") (pintype "passive"))
    )
    (net (code "335") (name "unconnected-(U125-2_NC-Pad4)") (class "Default")
      (node (ref "U125") (pin "4") (pinfunction "2_NC_4") (pintype "passive"))
    )
    (net (code "336") (name "unconnected-(U126-1_NC-Pad2)") (class "Default")
      (node (ref "U126") (pin "2") (pinfunction "1_NC_2") (pintype "passive"))
    )
    (net (code "337") (name "unconnected-(U126-2_NC-Pad4)") (class "Default")
      (node (ref "U126") (pin "4") (pinfunction "2_NC_4") (pintype "passive"))
    )
    (net (code "338") (name "unconnected-(U127-1_NC-Pad2)") (class "Default")
      (node (ref "U127") (pin "2") (pinfunction "1_NC_2") (pintype "passive"))
    )
    (net (code "339") (name "unconnected-(U127-2_NC-Pad4)") (class "Default")
      (node (ref "U127") (pin "4") (pinfunction "2_NC_4") (pintype "passive"))
    )
    (net (code "340") (name "unconnected-(U128-1_NC-Pad2)") (class "Default")
      (node (ref "U128") (pin "2") (pinfunction "1_NC_2") (pintype "passive"))
    )
    (net (code "341") (name "unconnected-(U128-2_NC-Pad4)") (class "Default")
      (node (ref "U128") (pin "4") (pinfunction "2_NC_4") (pintype "passive"))
    )
    (net (code "342") (name "unconnected-(U129-1_NC-Pad2)") (class "Default")
      (node (ref "U129") (pin "2") (pinfunction "1_NC_2") (pintype "passive"))
    )
    (net (code "343") (name "unconnected-(U129-2_NC-Pad4)") (class "Default")
      (node (ref "U129") (pin "4") (pinfunction "2_NC_4") (pintype "passive"))
    )
    (net (code "344") (name "unconnected-(U130-1_NC-Pad2)") (class "Default")
      (node (ref "U130") (pin "2") (pinfunction "1_NC_2") (pintype "passive"))
    )
    (net (code "345") (name "unconnected-(U130-2_NC-Pad4)") (class "Default")
      (node (ref "U130") (pin "4") (pinfunction "2_NC_4") (pintype "passive"))
    )
    (net (code "346") (name "unconnected-(U131-1_NC-Pad2)") (class "Default")
      (node (ref "U131") (pin "2") (pinfunction "1_NC_2") (pintype "passive"))
    )
    (net (code "347") (name "unconnected-(U131-2_NC-Pad4)") (class "Default")
      (node (ref "U131") (pin "4") (pinfunction "2_NC_4") (pintype "passive"))
    )
    (net (code "348") (name "unconnected-(U132-1_NC-Pad2)") (class "Default")
      (node (ref "U132") (pin "2") (pinfunction "1_NC_2") (pintype "passive"))
    )
    (net (code "349") (name "unconnected-(U132-2_NC-Pad4)") (class "Default")
      (node (ref "U132") (pin "4") (pinfunction "2_NC_4") (pintype "passive"))
    )
    (net (code "350") (name "unconnected-(U133-1_NC-Pad2)") (class "Default")
      (node (ref "U133") (pin "2") (pinfunction "1_NC_2") (pintype "passive"))
    )
    (net (code "351") (name "unconnected-(U133-2_NC-Pad4)") (class "Default")
      (node (ref "U133") (pin "4") (pinfunction "2_NC_4") (pintype "passive"))
    )
    (net (code "352") (name "unconnected-(U134-1_NC-Pad2)") (class "Default")
      (node (ref "U134") (pin "2") (pinfunction "1_NC_2") (pintype "passive"))
    )
    (net (code "353") (name "unconnected-(U134-2_NC-Pad4)") (class "Default")
      (node (ref "U134") (pin "4") (pinfunction "2_NC_4") (pintype "passive"))
    )
    (net (code "354") (name "unconnected-(U135-1_NC-Pad2)") (class "Default")
      (node (ref "U135") (pin "2") (pinfunction "1_NC_2") (pintype "passive"))
    )
    (net (code "355") (name "unconnected-(U135-2_NC-Pad4)") (class "Default")
      (node (ref "U135") (pin "4") (pinfunction "2_NC_4") (pintype "passive"))
    )
    (net (code "356") (name "unconnected-(U136-1_NC-Pad2)") (class "Default")
      (node (ref "U136") (pin "2") (pinfunction "1_NC_2") (pintype "passive"))
    )
    (net (code "357") (name "unconnected-(U136-2_NC-Pad4)") (class "Default")
      (node (ref "U136") (pin "4") (pinfunction "2_NC_4") (pintype "passive"))
    )
    (net (code "358") (name "unconnected-(U137-1_NC-Pad2)") (class "Default")
      (node (ref "U137") (pin "2") (pinfunction "1_NC_2") (pintype "passive"))
    )
    (net (code "359") (name "unconnected-(U137-2_NC-Pad4)") (class "Default")
      (node (ref "U137") (pin "4") (pinfunction "2_NC_4") (pintype "passive"))
    )
    (net (code "360") (name "unconnected-(U138-1_NC-Pad2)") (class "Default")
      (node (ref "U138") (pin "2") (pinfunction "1_NC_2") (pintype "passive"))
    )
    (net (code "361") (name "unconnected-(U138-2_NC-Pad4)") (class "Default")
      (node (ref "U138") (pin "4") (pinfunction "2_NC_4") (pintype "passive"))
    )
    (net (code "362") (name "unconnected-(U139-1_NC-Pad2)") (class "Default")
      (node (ref "U139") (pin "2") (pinfunction "1_NC_2") (pintype "passive"))
    )
    (net (code "363") (name "unconnected-(U139-2_NC-Pad4)") (class "Default")
      (node (ref "U139") (pin "4") (pinfunction "2_NC_4") (pintype "passive"))
    )
    (net (code "364") (name "unconnected-(U140-1_NC-Pad2)") (class "Default")
      (node (ref "U140") (pin "2") (pinfunction "1_NC_2") (pintype "passive"))
    )
    (net (code "365") (name "unconnected-(U140-2_NC-Pad4)") (class "Default")
      (node (ref "U140") (pin "4") (pinfunction "2_NC_4") (pintype "passive"))
    )
    (net (code "366") (name "unconnected-(U141-1_NC-Pad2)") (class "Default")
      (node (ref "U141") (pin "2") (pinfunction "1_NC_2") (pintype "passive"))
    )
    (net (code "367") (name "unconnected-(U141-2_NC-Pad4)") (class "Default")
      (node (ref "U141") (pin "4") (pinfunction "2_NC_4") (pintype "passive"))
    )
    (net (code "368") (name "unconnected-(U142-1_NC-Pad2)") (class "Default")
      (node (ref "U142") (pin "2") (pinfunction "1_NC_2") (pintype "passive"))
    )
    (net (code "369") (name "unconnected-(U142-2_NC-Pad4)") (class "Default")
      (node (ref "U142") (pin "4") (pinfunction "2_NC_4") (pintype "passive"))
    )
    (net (code "370") (name "unconnected-(U143-1_NC-Pad2)") (class "Default")
      (node (ref "U143") (pin "2") (pinfunction "1_NC_2") (pintype "passive"))
    )
    (net (code "371") (name "unconnected-(U143-2_NC-Pad4)") (class "Default")
      (node (ref "U143") (pin "4") (pinfunction "2_NC_4") (pintype "passive"))
    )
    (net (code "372") (name "unconnected-(U144-1_NC-Pad2)") (class "Default")
      (node (ref "U144") (pin "2") (pinfunction "1_NC_2") (pintype "passive"))
    )
    (net (code "373") (name "unconnected-(U144-2_NC-Pad4)") (class "Default")
      (node (ref "U144") (pin "4") (pinfunction "2_NC_4") (pintype "passive"))
    )
    (net (code "374") (name "unconnected-(U145-1_NC-Pad2)") (class "Default")
      (node (ref "U145") (pin "2") (pinfunction "1_NC_2") (pintype "passive"))
    )
    (net (code "375") (name "unconnected-(U145-2_NC-Pad4)") (class "Default")
      (node (ref "U145") (pin "4") (pinfunction "2_NC_4") (pintype "passive"))
    )
    (net (code "376") (name "unconnected-(U146-1_NC-Pad2)") (class "Default")
      (node (ref "U146") (pin "2") (pinfunction "1_NC_2") (pintype "passive"))
    )
    (net (code "377") (name "unconnected-(U146-2_NC-Pad4)") (class "Default")
      (node (ref "U146") (pin "4") (pinfunction "2_NC_4") (pintype "passive"))
    )
    (net (code "378") (name "unconnected-(U147-1_NC-Pad2)") (class "Default")
      (node (ref "U147") (pin "2") (pinfunction "1_NC_2") (pintype "passive"))
    )
    (net (code "379") (name "unconnected-(U147-2_NC-Pad4)") (class "Default")
      (node (ref "U147") (pin "4") (pinfunction "2_NC_4") (pintype "passive"))
    )
    (net (code "380") (name "unconnected-(U148-1_NC-Pad2)") (class "Default")
      (node (ref "U148") (pin "2") (pinfunction "1_NC_2") (pintype "passive"))
    )
    (net (code "381") (name "unconnected-(U148-2_NC-Pad4)") (class "Default")
      (node (ref "U148") (pin "4") (pinfunction "2_NC_4") (pintype "passive"))
    )
    (net (code "382") (name "unconnected-(U149-1_NC-Pad2)") (class "Default")
      (node (ref "U149") (pin "2") (pinfunction "1_NC_2") (pintype "passive"))
    )
    (net (code "383") (name "unconnected-(U149-2_NC-Pad4)") (class "Default")
      (node (ref "U149") (pin "4") (pinfunction "2_NC_4") (pintype "passive"))
    )
    (net (code "384") (name "unconnected-(U150-1_NC-Pad2)") (class "Default")
      (node (ref "U150") (pin "2") (pinfunction "1_NC_2") (pintype "passive"))
    )
    (net (code "385") (name "unconnected-(U150-2_NC-Pad4)") (class "Default")
      (node (ref "U150") (pin "4") (pinfunction "2_NC_4") (pintype "passive"))
    )
    (net (code "386") (name "unconnected-(U151-1_NC-Pad2)") (class "Default")
      (node (ref "U151") (pin "2") (pinfunction "1_NC_2") (pintype "passive"))
    )
    (net (code "387") (name "unconnected-(U151-2_NC-Pad4)") (class "Default")
      (node (ref "U151") (pin "4") (pinfunction "2_NC_4") (pintype "passive"))
    )
    (net (code "388") (name "unconnected-(U152-1_NC-Pad2)") (class "Default")
      (node (ref "U152") (pin "2") (pinfunction "1_NC_2") (pintype "passive"))
    )
    (net (code "389") (name "unconnected-(U152-2_NC-Pad4)") (class "Default")
      (node (ref "U152") (pin "4") (pinfunction "2_NC_4") (pintype "passive"))
    )
    (net (code "390") (name "unconnected-(U153-1_NC-Pad2)") (class "Default")
      (node (ref "U153") (pin "2") (pinfunction "1_NC_2") (pintype "passive"))
    )
    (net (code "391") (name "unconnected-(U153-2_NC-Pad4)") (class "Default")
      (node (ref "U153") (pin "4") (pinfunction "2_NC_4") (pintype "passive"))
    )
    (net (code "392") (name "unconnected-(U154-1_NC-Pad2)") (class "Default")
      (node (ref "U154") (pin "2") (pinfunction "1_NC_2") (pintype "passive"))
    )
    (net (code "393") (name "unconnected-(U154-2_NC-Pad4)") (class "Default")
      (node (ref "U154") (pin "4") (pinfunction "2_NC_4") (pintype "passive"))
    )
    (net (code "394") (name "unconnected-(U155-1_NC-Pad2)") (class "Default")
      (node (ref "U155") (pin "2") (pinfunction "1_NC_2") (pintype "passive"))
    )
    (net (code "395") (name "unconnected-(U155-2_NC-Pad4)") (class "Default")
      (node (ref "U155") (pin "4") (pinfunction "2_NC_4") (pintype "passive"))
    )
    (net (code "396") (name "unconnected-(U156-1_NC-Pad2)") (class "Default")
      (node (ref "U156") (pin "2") (pinfunction "1_NC_2") (pintype "passive"))
    )
    (net (code "397") (name "unconnected-(U156-2_NC-Pad4)") (class "Default")
      (node (ref "U156") (pin "4") (pinfunction "2_NC_4") (pintype "passive"))
    )
    (net (code "398") (name "unconnected-(U157-1_NC-Pad2)") (class "Default")
      (node (ref "U157") (pin "2") (pinfunction "1_NC_2") (pintype "passive"))
    )
    (net (code "399") (name "unconnected-(U157-2_NC-Pad4)") (class "Default")
      (node (ref "U157") (pin "4") (pinfunction "2_NC_4") (pintype "passive"))
    )
    (net (code "400") (name "unconnected-(U158-1_NC-Pad2)") (class "Default")
      (node (ref "U158") (pin "2") (pinfunction "1_NC_2") (pintype "passive"))
    )
    (net (code "401") (name "unconnected-(U158-2_NC-Pad4)") (class "Default")
      (node (ref "U158") (pin "4") (pinfunction "2_NC_4") (pintype "passive"))
    )
    (net (code "402") (name "unconnected-(U159-1_NC-Pad2)") (class "Default")
      (node (ref "U159") (pin "2") (pinfunction "1_NC_2") (pintype "passive"))
    )
    (net (code "403") (name "unconnected-(U159-2_NC-Pad4)") (class "Default")
      (node (ref "U159") (pin "4") (pinfunction "2_NC_4") (pintype "passive"))
    )
    (net (code "404") (name "unconnected-(U160-1_NC-Pad2)") (class "Default")
      (node (ref "U160") (pin "2") (pinfunction "1_NC_2") (pintype "passive"))
    )
    (net (code "405") (name "unconnected-(U160-2_NC-Pad4)") (class "Default")
      (node (ref "U160") (pin "4") (pinfunction "2_NC_4") (pintype "passive"))
    )
    (net (code "406") (name "unconnected-(U161-1_NC-Pad2)") (class "Default")
      (node (ref "U161") (pin "2") (pinfunction "1_NC_2") (pintype "passive"))
    )
    (net (code "407") (name "unconnected-(U161-2_NC-Pad4)") (class "Default")
      (node (ref "U161") (pin "4") (pinfunction "2_NC_4") (pintype "passive"))
    )
    (net (code "408") (name "unconnected-(U162-1_NC-Pad2)") (class "Default")
      (node (ref "U162") (pin "2") (pinfunction "1_NC_2") (pintype "passive"))
    )
    (net (code "409") (name "unconnected-(U162-2_NC-Pad4)") (class "Default")
      (node (ref "U162") (pin "4") (pinfunction "2_NC_4") (pintype "passive"))
    )
    (net (code "410") (name "unconnected-(U163-1_NC-Pad2)") (class "Default")
      (node (ref "U163") (pin "2") (pinfunction "1_NC_2") (pintype "passive"))
    )
    (net (code "411") (name "unconnected-(U163-2_NC-Pad4)") (class "Default")
      (node (ref "U163") (pin "4") (pinfunction "2_NC_4") (pintype "passive"))
    )
    (net (code "412") (name "unconnected-(U164-1_NC-Pad2)") (class "Default")
      (node (ref "U164") (pin "2") (pinfunction "1_NC_2") (pintype "passive"))
    )
    (net (code "413") (name "unconnected-(U164-2_NC-Pad4)") (class "Default")
      (node (ref "U164") (pin "4") (pinfunction "2_NC_4") (pintype "passive"))
    )
    (net (code "414") (name "unconnected-(U165-1_NC-Pad2)") (class "Default")
      (node (ref "U165") (pin "2") (pinfunction "1_NC_2") (pintype "passive"))
    )
    (net (code "415") (name "unconnected-(U165-2_NC-Pad4)") (class "Default")
      (node (ref "U165") (pin "4") (pinfunction "2_NC_4") (pintype "passive"))
    )
    (net (code "416") (name "unconnected-(U166-1_NC-Pad2)") (class "Default")
      (node (ref "U166") (pin "2") (pinfunction "1_NC_2") (pintype "passive"))
    )
    (net (code "417") (name "unconnected-(U166-2_NC-Pad4)") (class "Default")
      (node (ref "U166") (pin "4") (pinfunction "2_NC_4") (pintype "passive"))
    )
    (net (code "418") (name "unconnected-(U167-1_NC-Pad2)") (class "Default")
      (node (ref "U167") (pin "2") (pinfunction "1_NC_2") (pintype "passive"))
    )
    (net (code "419") (name "unconnected-(U167-2_NC-Pad4)") (class "Default")
      (node (ref "U167") (pin "4") (pinfunction "2_NC_4") (pintype "passive"))
    )
    (net (code "420") (name "unconnected-(U168-1_NC-Pad2)") (class "Default")
      (node (ref "U168") (pin "2") (pinfunction "1_NC_2") (pintype "passive"))
    )
    (net (code "421") (name "unconnected-(U168-2_NC-Pad4)") (class "Default")
      (node (ref "U168") (pin "4") (pinfunction "2_NC_4") (pintype "passive"))
    )
    (net (code "422") (name "unconnected-(U169-1_NC-Pad2)") (class "Default")
      (node (ref "U169") (pin "2") (pinfunction "1_NC_2") (pintype "passive"))
    )
    (net (code "423") (name "unconnected-(U169-2_NC-Pad4)") (class "Default")
      (node (ref "U169") (pin "4") (pinfunction "2_NC_4") (pintype "passive"))
    )
    (net (code "424") (name "unconnected-(U170-1_NC-Pad2)") (class "Default")
      (node (ref "U170") (pin "2") (pinfunction "1_NC_2") (pintype "passive"))
    )
    (net (code "425") (name "unconnected-(U170-2_NC-Pad4)") (class "Default")
      (node (ref "U170") (pin "4") (pinfunction "2_NC_4") (pintype "passive"))
    )
    (net (code "426") (name "unconnected-(U171-1_NC-Pad2)") (class "Default")
      (node (ref "U171") (pin "2") (pinfunction "1_NC_2") (pintype "passive"))
    )
    (net (code "427") (name "unconnected-(U171-2_NC-Pad4)") (class "Default")
      (node (ref "U171") (pin "4") (pinfunction "2_NC_4") (pintype "passive"))
    )
    (net (code "428") (name "unconnected-(U172-1_NC-Pad2)") (class "Default")
      (node (ref "U172") (pin "2") (pinfunction "1_NC_2") (pintype "passive"))
    )
    (net (code "429") (name "unconnected-(U172-2_NC-Pad4)") (class "Default")
      (node (ref "U172") (pin "4") (pinfunction "2_NC_4") (pintype "passive"))
    )
    (net (code "430") (name "unconnected-(U173-1_NC-Pad2)") (class "Default")
      (node (ref "U173") (pin "2") (pinfunction "1_NC_2") (pintype "passive"))
    )
    (net (code "431") (name "unconnected-(U173-2_NC-Pad4)") (class "Default")
      (node (ref "U173") (pin "4") (pinfunction "2_NC_4") (pintype "passive"))
    )
    (net (code "432") (name "unconnected-(U174-1_NC-Pad2)") (class "Default")
      (node (ref "U174") (pin "2") (pinfunction "1_NC_2") (pintype "passive"))
    )
    (net (code "433") (name "unconnected-(U174-2_NC-Pad4)") (class "Default")
      (node (ref "U174") (pin "4") (pinfunction "2_NC_4") (pintype "passive"))
    )
    (net (code "434") (name "unconnected-(U175-1_NC-Pad2)") (class "Default")
      (node (ref "U175") (pin "2") (pinfunction "1_NC_2") (pintype "passive"))
    )
    (net (code "435") (name "unconnected-(U175-2_NC-Pad4)") (class "Default")
      (node (ref "U175") (pin "4") (pinfunction "2_NC_4") (pintype "passive"))
    )
    (net (code "436") (name "unconnected-(U176-1_NC-Pad2)") (class "Default")
      (node (ref "U176") (pin "2") (pinfunction "1_NC_2") (pintype "passive"))
    )
    (net (code "437") (name "unconnected-(U176-2_NC-Pad4)") (class "Default")
      (node (ref "U176") (pin "4") (pinfunction "2_NC_4") (pintype "passive"))
    )
    (net (code "438") (name "unconnected-(U177-1_NC-Pad2)") (class "Default")
      (node (ref "U177") (pin "2") (pinfunction "1_NC_2") (pintype "passive"))
    )
    (net (code "439") (name "unconnected-(U177-2_NC-Pad4)") (class "Default")
      (node (ref "U177") (pin "4") (pinfunction "2_NC_4") (pintype "passive"))
    )
    (net (code "440") (name "unconnected-(U178-1_NC-Pad2)") (class "Default")
      (node (ref "U178") (pin "2") (pinfunction "1_NC_2") (pintype "passive"))
    )
    (net (code "441") (name "unconnected-(U178-2_NC-Pad4)") (class "Default")
      (node (ref "U178") (pin "4") (pinfunction "2_NC_4") (pintype "passive"))
    )
    (net (code "442") (name "unconnected-(U179-1_NC-Pad2)") (class "Default")
      (node (ref "U179") (pin "2") (pinfunction "1_NC_2") (pintype "passive"))
    )
    (net (code "443") (name "unconnected-(U179-2_NC-Pad4)") (class "Default")
      (node (ref "U179") (pin "4") (pinfunction "2_NC_4") (pintype "passive"))
    )
    (net (code "444") (name "unconnected-(U180-1_NC-Pad2)") (class "Default")
      (node (ref "U180") (pin "2") (pinfunction "1_NC_2") (pintype "passive"))
    )
    (net (code "445") (name "unconnected-(U180-2_NC-Pad4)") (class "Default")
      (node (ref "U180") (pin "4") (pinfunction "2_NC_4") (pintype "passive"))
    )
    (net (code "446") (name "unconnected-(U184-1_NC-Pad2)") (class "Default")
      (node (ref "U184") (pin "2") (pinfunction "1_NC_2") (pintype "passive"))
    )
    (net (code "447") (name "unconnected-(U184-2_NC-Pad4)") (class "Default")
      (node (ref "U184") (pin "4") (pinfunction "2_NC_4") (pintype "passive"))
    )
    (net (code "448") (name "unconnected-(U185-1_NC-Pad2)") (class "Default")
      (node (ref "U185") (pin "2") (pinfunction "1_NC_2") (pintype "passive"))
    )
    (net (code "449") (name "unconnected-(U185-2_NC-Pad4)") (class "Default")
      (node (ref "U185") (pin "4") (pinfunction "2_NC_4") (pintype "passive"))
    )
    (net (code "450") (name "unconnected-(U186-1_NC-Pad2)") (class "Default")
      (node (ref "U186") (pin "2") (pinfunction "1_NC_2") (pintype "passive"))
    )
    (net (code "451") (name "unconnected-(U186-2_NC-Pad4)") (class "Default")
      (node (ref "U186") (pin "4") (pinfunction "2_NC_4") (pintype "passive"))
    )
    (net (code "452") (name "unconnected-(U192-1_NC-Pad2)") (class "Default")
      (node (ref "U192") (pin "2") (pinfunction "1_NC_2") (pintype "passive"))
    )
    (net (code "453") (name "unconnected-(U192-2_NC-Pad4)") (class "Default")
      (node (ref "U192") (pin "4") (pinfunction "2_NC_4") (pintype "passive"))
    )
    (net (code "454") (name "unconnected-(U193-1_NC-Pad2)") (class "Default")
      (node (ref "U193") (pin "2") (pinfunction "1_NC_2") (pintype "passive"))
    )
    (net (code "455") (name "unconnected-(U193-2_NC-Pad4)") (class "Default")
      (node (ref "U193") (pin "4") (pinfunction "2_NC_4") (pintype "passive"))
    )
    (net (code "456") (name "unconnected-(U194-1_NC-Pad2)") (class "Default")
      (node (ref "U194") (pin "2") (pinfunction "1_NC_2") (pintype "passive"))
    )
    (net (code "457") (name "unconnected-(U194-2_NC-Pad4)") (class "Default")
      (node (ref "U194") (pin "4") (pinfunction "2_NC_4") (pintype "passive"))
    )
    (net (code "458") (name "unconnected-(U195-1_NC-Pad2)") (class "Default")
      (node (ref "U195") (pin "2") (pinfunction "1_NC_2") (pintype "passive"))
    )
    (net (code "459") (name "unconnected-(U195-2_NC-Pad4)") (class "Default")
      (node (ref "U195") (pin "4") (pinfunction "2_NC_4") (pintype "passive"))
    )
    (net (code "460") (name "unconnected-(U196-1_NC-Pad2)") (class "Default")
      (node (ref "U196") (pin "2") (pinfunction "1_NC_2") (pintype "passive"))
    )
    (net (code "461") (name "unconnected-(U196-2_NC-Pad4)") (class "Default")
      (node (ref "U196") (pin "4") (pinfunction "2_NC_4") (pintype "passive"))
    )
    (net (code "462") (name "unconnected-(U197-1_NC-Pad2)") (class "Default")
      (node (ref "U197") (pin "2") (pinfunction "1_NC_2") (pintype "passive"))
    )
    (net (code "463") (name "unconnected-(U197-2_NC-Pad4)") (class "Default")
      (node (ref "U197") (pin "4") (pinfunction "2_NC_4") (pintype "passive"))
    )
    (net (code "464") (name "unconnected-(U198-1_NC-Pad2)") (class "Default")
      (node (ref "U198") (pin "2") (pinfunction "1_NC_2") (pintype "passive"))
    )
    (net (code "465") (name "unconnected-(U198-2_NC-Pad4)") (class "Default")
      (node (ref "U198") (pin "4") (pinfunction "2_NC_4") (pintype "passive"))
    )
    (net (code "466") (name "unconnected-(U199-1_NC-Pad2)") (class "Default")
      (node (ref "U199") (pin "2") (pinfunction "1_NC_2") (pintype "passive"))
    )
    (net (code "467") (name "unconnected-(U199-2_NC-Pad4)") (class "Default")
      (node (ref "U199") (pin "4") (pinfunction "2_NC_4") (pintype "passive"))
    )
    (net (code "468") (name "unconnected-(U200-1_NC-Pad2)") (class "Default")
      (node (ref "U200") (pin "2") (pinfunction "1_NC_2") (pintype "passive"))
    )
    (net (code "469") (name "unconnected-(U200-2_NC-Pad4)") (class "Default")
      (node (ref "U200") (pin "4") (pinfunction "2_NC_4") (pintype "passive"))
    )
    (net (code "470") (name "unconnected-(U201-1_NC-Pad2)") (class "Default")
      (node (ref "U201") (pin "2") (pinfunction "1_NC_2") (pintype "passive"))
    )
    (net (code "471") (name "unconnected-(U201-2_NC-Pad4)") (class "Default")
      (node (ref "U201") (pin "4") (pinfunction "2_NC_4") (pintype "passive"))
    )
    (net (code "472") (name "unconnected-(U202-1_NC-Pad2)") (class "Default")
      (node (ref "U202") (pin "2") (pinfunction "1_NC_2") (pintype "passive"))
    )
    (net (code "473") (name "unconnected-(U202-2_NC-Pad4)") (class "Default")
      (node (ref "U202") (pin "4") (pinfunction "2_NC_4") (pintype "passive"))
    )
    (net (code "474") (name "unconnected-(U203-1_NC-Pad2)") (class "Default")
      (node (ref "U203") (pin "2") (pinfunction "1_NC_2") (pintype "passive"))
    )
    (net (code "475") (name "unconnected-(U203-2_NC-Pad4)") (class "Default")
      (node (ref "U203") (pin "4") (pinfunction "2_NC_4") (pintype "passive"))
    )
    (net (code "476") (name "unconnected-(U204-1_NC-Pad2)") (class "Default")
      (node (ref "U204") (pin "2") (pinfunction "1_NC_2") (pintype "passive"))
    )
    (net (code "477") (name "unconnected-(U204-2_NC-Pad4)") (class "Default")
      (node (ref "U204") (pin "4") (pinfunction "2_NC_4") (pintype "passive"))
    )
    (net (code "478") (name "unconnected-(U205-1_NC-Pad2)") (class "Default")
      (node (ref "U205") (pin "2") (pinfunction "1_NC_2") (pintype "passive"))
    )
    (net (code "479") (name "unconnected-(U205-2_NC-Pad4)") (class "Default")
      (node (ref "U205") (pin "4") (pinfunction "2_NC_4") (pintype "passive"))
    )
    (net (code "480") (name "unconnected-(U206-1_NC-Pad2)") (class "Default")
      (node (ref "U206") (pin "2") (pinfunction "1_NC_2") (pintype "passive"))
    )
    (net (code "481") (name "unconnected-(U206-2_NC-Pad4)") (class "Default")
      (node (ref "U206") (pin "4") (pinfunction "2_NC_4") (pintype "passive"))
    )
    (net (code "482") (name "unconnected-(U207-1_NC-Pad2)") (class "Default")
      (node (ref "U207") (pin "2") (pinfunction "1_NC_2") (pintype "passive"))
    )
    (net (code "483") (name "unconnected-(U207-2_NC-Pad4)") (class "Default")
      (node (ref "U207") (pin "4") (pinfunction "2_NC_4") (pintype "passive"))
    )
    (net (code "484") (name "unconnected-(U208-1_NC-Pad2)") (class "Default")
      (node (ref "U208") (pin "2") (pinfunction "1_NC_2") (pintype "passive"))
    )
    (net (code "485") (name "unconnected-(U208-2_NC-Pad4)") (class "Default")
      (node (ref "U208") (pin "4") (pinfunction "2_NC_4") (pintype "passive"))
    )
    (net (code "486") (name "unconnected-(U209-1_NC-Pad2)") (class "Default")
      (node (ref "U209") (pin "2") (pinfunction "1_NC_2") (pintype "passive"))
    )
    (net (code "487") (name "unconnected-(U209-2_NC-Pad4)") (class "Default")
      (node (ref "U209") (pin "4") (pinfunction "2_NC_4") (pintype "passive"))
    )
    (net (code "488") (name "unconnected-(U210-1_NC-Pad2)") (class "Default")
      (node (ref "U210") (pin "2") (pinfunction "1_NC_2") (pintype "passive"))
    )
    (net (code "489") (name "unconnected-(U210-2_NC-Pad4)") (class "Default")
      (node (ref "U210") (pin "4") (pinfunction "2_NC_4") (pintype "passive"))
    )
    (net (code "490") (name "unconnected-(U211-1_NC-Pad2)") (class "Default")
      (node (ref "U211") (pin "2") (pinfunction "1_NC_2") (pintype "passive"))
    )
    (net (code "491") (name "unconnected-(U211-2_NC-Pad4)") (class "Default")
      (node (ref "U211") (pin "4") (pinfunction "2_NC_4") (pintype "passive"))
    )
    (net (code "492") (name "unconnected-(U212-1_NC-Pad2)") (class "Default")
      (node (ref "U212") (pin "2") (pinfunction "1_NC_2") (pintype "passive"))
    )
    (net (code "493") (name "unconnected-(U212-2_NC-Pad4)") (class "Default")
      (node (ref "U212") (pin "4") (pinfunction "2_NC_4") (pintype "passive"))
    )
    (net (code "494") (name "unconnected-(U213-1_NC-Pad2)") (class "Default")
      (node (ref "U213") (pin "2") (pinfunction "1_NC_2") (pintype "passive"))
    )
    (net (code "495") (name "unconnected-(U213-2_NC-Pad4)") (class "Default")
      (node (ref "U213") (pin "4") (pinfunction "2_NC_4") (pintype "passive"))
    )
    (net (code "496") (name "unconnected-(U214-1_NC-Pad2)") (class "Default")
      (node (ref "U214") (pin "2") (pinfunction "1_NC_2") (pintype "passive"))
    )
    (net (code "497") (name "unconnected-(U214-2_NC-Pad4)") (class "Default")
      (node (ref "U214") (pin "4") (pinfunction "2_NC_4") (pintype "passive"))
    )
    (net (code "498") (name "unconnected-(U215-1_NC-Pad2)") (class "Default")
      (node (ref "U215") (pin "2") (pinfunction "1_NC_2") (pintype "passive"))
    )
    (net (code "499") (name "unconnected-(U215-2_NC-Pad4)") (class "Default")
      (node (ref "U215") (pin "4") (pinfunction "2_NC_4") (pintype "passive"))
    )
    (net (code "500") (name "unconnected-(U216-1_NC-Pad2)") (class "Default")
      (node (ref "U216") (pin "2") (pinfunction "1_NC_2") (pintype "passive"))
    )
    (net (code "501") (name "unconnected-(U216-2_NC-Pad4)") (class "Default")
      (node (ref "U216") (pin "4") (pinfunction "2_NC_4") (pintype "passive"))
    )
    (net (code "502") (name "unconnected-(U217-1_NC-Pad2)") (class "Default")
      (node (ref "U217") (pin "2") (pinfunction "1_NC_2") (pintype "passive"))
    )
    (net (code "503") (name "unconnected-(U217-2_NC-Pad4)") (class "Default")
      (node (ref "U217") (pin "4") (pinfunction "2_NC_4") (pintype "passive"))
    )
    (net (code "504") (name "unconnected-(U218-1_NC-Pad2)") (class "Default")
      (node (ref "U218") (pin "2") (pinfunction "1_NC_2") (pintype "passive"))
    )
    (net (code "505") (name "unconnected-(U218-2_NC-Pad4)") (class "Default")
      (node (ref "U218") (pin "4") (pinfunction "2_NC_4") (pintype "passive"))
    )
    (net (code "506") (name "unconnected-(U219-1_NC-Pad2)") (class "Default")
      (node (ref "U219") (pin "2") (pinfunction "1_NC_2") (pintype "passive"))
    )
    (net (code "507") (name "unconnected-(U219-2_NC-Pad4)") (class "Default")
      (node (ref "U219") (pin "4") (pinfunction "2_NC_4") (pintype "passive"))
    )
    (net (code "508") (name "unconnected-(U220-1_NC-Pad2)") (class "Default")
      (node (ref "U220") (pin "2") (pinfunction "1_NC_2") (pintype "passive"))
    )
    (net (code "509") (name "unconnected-(U220-2_NC-Pad4)") (class "Default")
      (node (ref "U220") (pin "4") (pinfunction "2_NC_4") (pintype "passive"))
    )
    (net (code "510") (name "unconnected-(U221-1_NC-Pad2)") (class "Default")
      (node (ref "U221") (pin "2") (pinfunction "1_NC_2") (pintype "passive"))
    )
    (net (code "511") (name "unconnected-(U221-2_NC-Pad4)") (class "Default")
      (node (ref "U221") (pin "4") (pinfunction "2_NC_4") (pintype "passive"))
    )
    (net (code "512") (name "unconnected-(U222-1_NC-Pad2)") (class "Default")
      (node (ref "U222") (pin "2") (pinfunction "1_NC_2") (pintype "passive"))
    )
    (net (code "513") (name "unconnected-(U222-2_NC-Pad4)") (class "Default")
      (node (ref "U222") (pin "4") (pinfunction "2_NC_4") (pintype "passive"))
    )
    (net (code "514") (name "unconnected-(U223-1_NC-Pad2)") (class "Default")
      (node (ref "U223") (pin "2") (pinfunction "1_NC_2") (pintype "passive"))
    )
    (net (code "515") (name "unconnected-(U223-2_NC-Pad4)") (class "Default")
      (node (ref "U223") (pin "4") (pinfunction "2_NC_4") (pintype "passive"))
    )
    (net (code "516") (name "unconnected-(U224-1_NC-Pad2)") (class "Default")
      (node (ref "U224") (pin "2") (pinfunction "1_NC_2") (pintype "passive"))
    )
    (net (code "517") (name "unconnected-(U224-2_NC-Pad4)") (class "Default")
      (node (ref "U224") (pin "4") (pinfunction "2_NC_4") (pintype "passive"))
    )
    (net (code "518") (name "unconnected-(U225-1_NC-Pad2)") (class "Default")
      (node (ref "U225") (pin "2") (pinfunction "1_NC_2") (pintype "passive"))
    )
    (net (code "519") (name "unconnected-(U225-2_NC-Pad4)") (class "Default")
      (node (ref "U225") (pin "4") (pinfunction "2_NC_4") (pintype "passive"))
    )
    (net (code "520") (name "unconnected-(U226-1_NC-Pad2)") (class "Default")
      (node (ref "U226") (pin "2") (pinfunction "1_NC_2") (pintype "passive"))
    )
    (net (code "521") (name "unconnected-(U226-2_NC-Pad4)") (class "Default")
      (node (ref "U226") (pin "4") (pinfunction "2_NC_4") (pintype "passive"))
    )
    (net (code "522") (name "unconnected-(U227-1_NC-Pad2)") (class "Default")
      (node (ref "U227") (pin "2") (pinfunction "1_NC_2") (pintype "passive"))
    )
    (net (code "523") (name "unconnected-(U227-2_NC-Pad4)") (class "Default")
      (node (ref "U227") (pin "4") (pinfunction "2_NC_4") (pintype "passive"))
    )
    (net (code "524") (name "unconnected-(U228-1_NC-Pad2)") (class "Default")
      (node (ref "U228") (pin "2") (pinfunction "1_NC_2") (pintype "passive"))
    )
    (net (code "525") (name "unconnected-(U228-2_NC-Pad4)") (class "Default")
      (node (ref "U228") (pin "4") (pinfunction "2_NC_4") (pintype "passive"))
    )
    (net (code "526") (name "unconnected-(U229-1_NC-Pad2)") (class "Default")
      (node (ref "U229") (pin "2") (pinfunction "1_NC_2") (pintype "passive"))
    )
    (net (code "527") (name "unconnected-(U229-2_NC-Pad4)") (class "Default")
      (node (ref "U229") (pin "4") (pinfunction "2_NC_4") (pintype "passive"))
    )
    (net (code "528") (name "unconnected-(U230-1_NC-Pad2)") (class "Default")
      (node (ref "U230") (pin "2") (pinfunction "1_NC_2") (pintype "passive"))
    )
    (net (code "529") (name "unconnected-(U230-2_NC-Pad4)") (class "Default")
      (node (ref "U230") (pin "4") (pinfunction "2_NC_4") (pintype "passive"))
    )
    (net (code "530") (name "unconnected-(U231-1_NC-Pad2)") (class "Default")
      (node (ref "U231") (pin "2") (pinfunction "1_NC_2") (pintype "passive"))
    )
    (net (code "531") (name "unconnected-(U231-2_NC-Pad4)") (class "Default")
      (node (ref "U231") (pin "4") (pinfunction "2_NC_4") (pintype "passive"))
    )
    (net (code "532") (name "unconnected-(U232-1_NC-Pad2)") (class "Default")
      (node (ref "U232") (pin "2") (pinfunction "1_NC_2") (pintype "passive"))
    )
    (net (code "533") (name "unconnected-(U232-2_NC-Pad4)") (class "Default")
      (node (ref "U232") (pin "4") (pinfunction "2_NC_4") (pintype "passive"))
    )
    (net (code "534") (name "unconnected-(U233-1_NC-Pad2)") (class "Default")
      (node (ref "U233") (pin "2") (pinfunction "1_NC_2") (pintype "passive"))
    )
    (net (code "535") (name "unconnected-(U233-2_NC-Pad4)") (class "Default")
      (node (ref "U233") (pin "4") (pinfunction "2_NC_4") (pintype "passive"))
    )
    (net (code "536") (name "unconnected-(U234-1_NC-Pad2)") (class "Default")
      (node (ref "U234") (pin "2") (pinfunction "1_NC_2") (pintype "passive"))
    )
    (net (code "537") (name "unconnected-(U234-2_NC-Pad4)") (class "Default")
      (node (ref "U234") (pin "4") (pinfunction "2_NC_4") (pintype "passive"))
    )
    (net (code "538") (name "unconnected-(U235-1_NC-Pad2)") (class "Default")
      (node (ref "U235") (pin "2") (pinfunction "1_NC_2") (pintype "passive"))
    )
    (net (code "539") (name "unconnected-(U235-2_NC-Pad4)") (class "Default")
      (node (ref "U235") (pin "4") (pinfunction "2_NC_4") (pintype "passive"))
    )
    (net (code "540") (name "unconnected-(U236-1_NC-Pad2)") (class "Default")
      (node (ref "U236") (pin "2") (pinfunction "1_NC_2") (pintype "passive"))
    )
    (net (code "541") (name "unconnected-(U236-2_NC-Pad4)") (class "Default")
      (node (ref "U236") (pin "4") (pinfunction "2_NC_4") (pintype "passive"))
    )
    (net (code "542") (name "unconnected-(U237-1_NC-Pad2)") (class "Default")
      (node (ref "U237") (pin "2") (pinfunction "1_NC_2") (pintype "passive"))
    )
    (net (code "543") (name "unconnected-(U237-2_NC-Pad4)") (class "Default")
      (node (ref "U237") (pin "4") (pinfunction "2_NC_4") (pintype "passive"))
    )
    (net (code "544") (name "unconnected-(U238-1_NC-Pad2)") (class "Default")
      (node (ref "U238") (pin "2") (pinfunction "1_NC_2") (pintype "passive"))
    )
    (net (code "545") (name "unconnected-(U238-2_NC-Pad4)") (class "Default")
      (node (ref "U238") (pin "4") (pinfunction "2_NC_4") (pintype "passive"))
    )
    (net (code "546") (name "unconnected-(U239-1_NC-Pad2)") (class "Default")
      (node (ref "U239") (pin "2") (pinfunction "1_NC_2") (pintype "passive"))
    )
    (net (code "547") (name "unconnected-(U239-2_NC-Pad4)") (class "Default")
      (node (ref "U239") (pin "4") (pinfunction "2_NC_4") (pintype "passive"))
    )
    (net (code "548") (name "unconnected-(U240-1_NC-Pad2)") (class "Default")
      (node (ref "U240") (pin "2") (pinfunction "1_NC_2") (pintype "passive"))
    )
    (net (code "549") (name "unconnected-(U240-2_NC-Pad4)") (class "Default")
      (node (ref "U240") (pin "4") (pinfunction "2_NC_4") (pintype "passive"))
    )
    (net (code "550") (name "unconnected-(U241-1_NC-Pad2)") (class "Default")
      (node (ref "U241") (pin "2") (pinfunction "1_NC_2") (pintype "passive"))
    )
    (net (code "551") (name "unconnected-(U241-2_NC-Pad4)") (class "Default")
      (node (ref "U241") (pin "4") (pinfunction "2_NC_4") (pintype "passive"))
    )
    (net (code "552") (name "unconnected-(U242-1_NC-Pad2)") (class "Default")
      (node (ref "U242") (pin "2") (pinfunction "1_NC_2") (pintype "passive"))
    )
    (net (code "553") (name "unconnected-(U242-2_NC-Pad4)") (class "Default")
      (node (ref "U242") (pin "4") (pinfunction "2_NC_4") (pintype "passive"))
    )
    (net (code "554") (name "unconnected-(U246-1_NC-Pad2)") (class "Default")
      (node (ref "U246") (pin "2") (pinfunction "1_NC_2") (pintype "passive"))
    )
    (net (code "555") (name "unconnected-(U246-2_NC-Pad4)") (class "Default")
      (node (ref "U246") (pin "4") (pinfunction "2_NC_4") (pintype "passive"))
    )
    (net (code "556") (name "unconnected-(U247-1_NC-Pad2)") (class "Default")
      (node (ref "U247") (pin "2") (pinfunction "1_NC_2") (pintype "passive"))
    )
    (net (code "557") (name "unconnected-(U247-2_NC-Pad4)") (class "Default")
      (node (ref "U247") (pin "4") (pinfunction "2_NC_4") (pintype "passive"))
    )
    (net (code "558") (name "unconnected-(U248-1_NC-Pad2)") (class "Default")
      (node (ref "U248") (pin "2") (pinfunction "1_NC_2") (pintype "passive"))
    )
    (net (code "559") (name "unconnected-(U248-2_NC-Pad4)") (class "Default")
      (node (ref "U248") (pin "4") (pinfunction "2_NC_4") (pintype "passive"))
    )
    (net (code "560") (name "unconnected-(U249-1_NC-Pad2)") (class "Default")
      (node (ref "U249") (pin "2") (pinfunction "1_NC_2") (pintype "passive"))
    )
    (net (code "561") (name "unconnected-(U249-2_NC-Pad4)") (class "Default")
      (node (ref "U249") (pin "4") (pinfunction "2_NC_4") (pintype "passive"))
    )
    (net (code "562") (name "unconnected-(U250-1_NC-Pad2)") (class "Default")
      (node (ref "U250") (pin "2") (pinfunction "1_NC_2") (pintype "passive"))
    )
    (net (code "563") (name "unconnected-(U250-2_NC-Pad4)") (class "Default")
      (node (ref "U250") (pin "4") (pinfunction "2_NC_4") (pintype "passive"))
    )
    (net (code "564") (name "unconnected-(U251-1_NC-Pad2)") (class "Default")
      (node (ref "U251") (pin "2") (pinfunction "1_NC_2") (pintype "passive"))
    )
    (net (code "565") (name "unconnected-(U251-2_NC-Pad4)") (class "Default")
      (node (ref "U251") (pin "4") (pinfunction "2_NC_4") (pintype "passive"))
    )
    (net (code "566") (name "unconnected-(U252-1_NC-Pad2)") (class "Default")
      (node (ref "U252") (pin "2") (pinfunction "1_NC_2") (pintype "passive"))
    )
    (net (code "567") (name "unconnected-(U252-2_NC-Pad4)") (class "Default")
      (node (ref "U252") (pin "4") (pinfunction "2_NC_4") (pintype "passive"))
    )
    (net (code "568") (name "unconnected-(U253-1_NC-Pad2)") (class "Default")
      (node (ref "U253") (pin "2") (pinfunction "1_NC_2") (pintype "passive"))
    )
    (net (code "569") (name "unconnected-(U253-2_NC-Pad4)") (class "Default")
      (node (ref "U253") (pin "4") (pinfunction "2_NC_4") (pintype "passive"))
    )
    (net (code "570") (name "unconnected-(U254-1_NC-Pad2)") (class "Default")
      (node (ref "U254") (pin "2") (pinfunction "1_NC_2") (pintype "passive"))
    )
    (net (code "571") (name "unconnected-(U254-2_NC-Pad4)") (class "Default")
      (node (ref "U254") (pin "4") (pinfunction "2_NC_4") (pintype "passive"))
    )
    (net (code "572") (name "unconnected-(U255-1_NC-Pad2)") (class "Default")
      (node (ref "U255") (pin "2") (pinfunction "1_NC_2") (pintype "passive"))
    )
    (net (code "573") (name "unconnected-(U255-2_NC-Pad4)") (class "Default")
      (node (ref "U255") (pin "4") (pinfunction "2_NC_4") (pintype "passive"))
    )
    (net (code "574") (name "unconnected-(U256-1_NC-Pad2)") (class "Default")
      (node (ref "U256") (pin "2") (pinfunction "1_NC_2") (pintype "passive"))
    )
    (net (code "575") (name "unconnected-(U256-2_NC-Pad4)") (class "Default")
      (node (ref "U256") (pin "4") (pinfunction "2_NC_4") (pintype "passive"))
    )
    (net (code "576") (name "unconnected-(U257-1_NC-Pad2)") (class "Default")
      (node (ref "U257") (pin "2") (pinfunction "1_NC_2") (pintype "passive"))
    )
    (net (code "577") (name "unconnected-(U257-2_NC-Pad4)") (class "Default")
      (node (ref "U257") (pin "4") (pinfunction "2_NC_4") (pintype "passive"))
    )
    (net (code "578") (name "unconnected-(U258-1_NC-Pad2)") (class "Default")
      (node (ref "U258") (pin "2") (pinfunction "1_NC_2") (pintype "passive"))
    )
    (net (code "579") (name "unconnected-(U258-2_NC-Pad4)") (class "Default")
      (node (ref "U258") (pin "4") (pinfunction "2_NC_4") (pintype "passive"))
    )
    (net (code "580") (name "unconnected-(U259-1_NC-Pad2)") (class "Default")
      (node (ref "U259") (pin "2") (pinfunction "1_NC_2") (pintype "passive"))
    )
    (net (code "581") (name "unconnected-(U259-2_NC-Pad4)") (class "Default")
      (node (ref "U259") (pin "4") (pinfunction "2_NC_4") (pintype "passive"))
    )
    (net (code "582") (name "unconnected-(U260-1_NC-Pad2)") (class "Default")
      (node (ref "U260") (pin "2") (pinfunction "1_NC_2") (pintype "passive"))
    )
    (net (code "583") (name "unconnected-(U260-2_NC-Pad4)") (class "Default")
      (node (ref "U260") (pin "4") (pinfunction "2_NC_4") (pintype "passive"))
    )
    (net (code "584") (name "unconnected-(U261-1_NC-Pad2)") (class "Default")
      (node (ref "U261") (pin "2") (pinfunction "1_NC_2") (pintype "passive"))
    )
    (net (code "585") (name "unconnected-(U261-2_NC-Pad4)") (class "Default")
      (node (ref "U261") (pin "4") (pinfunction "2_NC_4") (pintype "passive"))
    )
    (net (code "586") (name "unconnected-(U262-1_NC-Pad2)") (class "Default")
      (node (ref "U262") (pin "2") (pinfunction "1_NC_2") (pintype "passive"))
    )
    (net (code "587") (name "unconnected-(U262-2_NC-Pad4)") (class "Default")
      (node (ref "U262") (pin "4") (pinfunction "2_NC_4") (pintype "passive"))
    )
    (net (code "588") (name "unconnected-(U263-1_NC-Pad2)") (class "Default")
      (node (ref "U263") (pin "2") (pinfunction "1_NC_2") (pintype "passive"))
    )
    (net (code "589") (name "unconnected-(U263-2_NC-Pad4)") (class "Default")
      (node (ref "U263") (pin "4") (pinfunction "2_NC_4") (pintype "passive"))
    )
    (net (code "590") (name "unconnected-(U264-1_NC-Pad2)") (class "Default")
      (node (ref "U264") (pin "2") (pinfunction "1_NC_2") (pintype "passive"))
    )
    (net (code "591") (name "unconnected-(U264-2_NC-Pad4)") (class "Default")
      (node (ref "U264") (pin "4") (pinfunction "2_NC_4") (pintype "passive"))
    )
    (net (code "592") (name "unconnected-(U265-1_NC-Pad2)") (class "Default")
      (node (ref "U265") (pin "2") (pinfunction "1_NC_2") (pintype "passive"))
    )
    (net (code "593") (name "unconnected-(U265-2_NC-Pad4)") (class "Default")
      (node (ref "U265") (pin "4") (pinfunction "2_NC_4") (pintype "passive"))
    )
    (net (code "594") (name "unconnected-(U266-1_NC-Pad2)") (class "Default")
      (node (ref "U266") (pin "2") (pinfunction "1_NC_2") (pintype "passive"))
    )
    (net (code "595") (name "unconnected-(U266-2_NC-Pad4)") (class "Default")
      (node (ref "U266") (pin "4") (pinfunction "2_NC_4") (pintype "passive"))
    )
    (net (code "596") (name "unconnected-(U267-1_NC-Pad2)") (class "Default")
      (node (ref "U267") (pin "2") (pinfunction "1_NC_2") (pintype "passive"))
    )
    (net (code "597") (name "unconnected-(U267-2_NC-Pad4)") (class "Default")
      (node (ref "U267") (pin "4") (pinfunction "2_NC_4") (pintype "passive"))
    )
    (net (code "598") (name "unconnected-(U268-1_NC-Pad2)") (class "Default")
      (node (ref "U268") (pin "2") (pinfunction "1_NC_2") (pintype "passive"))
    )
    (net (code "599") (name "unconnected-(U268-2_NC-Pad4)") (class "Default")
      (node (ref "U268") (pin "4") (pinfunction "2_NC_4") (pintype "passive"))
    )
    (net (code "600") (name "unconnected-(U269-1_NC-Pad2)") (class "Default")
      (node (ref "U269") (pin "2") (pinfunction "1_NC_2") (pintype "passive"))
    )
    (net (code "601") (name "unconnected-(U269-2_NC-Pad4)") (class "Default")
      (node (ref "U269") (pin "4") (pinfunction "2_NC_4") (pintype "passive"))
    )
    (net (code "602") (name "unconnected-(U270-1_NC-Pad2)") (class "Default")
      (node (ref "U270") (pin "2") (pinfunction "1_NC_2") (pintype "passive"))
    )
    (net (code "603") (name "unconnected-(U270-2_NC-Pad4)") (class "Default")
      (node (ref "U270") (pin "4") (pinfunction "2_NC_4") (pintype "passive"))
    )
    (net (code "604") (name "unconnected-(U271-1_NC-Pad2)") (class "Default")
      (node (ref "U271") (pin "2") (pinfunction "1_NC_2") (pintype "passive"))
    )
    (net (code "605") (name "unconnected-(U271-2_NC-Pad4)") (class "Default")
      (node (ref "U271") (pin "4") (pinfunction "2_NC_4") (pintype "passive"))
    )
    (net (code "606") (name "unconnected-(U272-1_NC-Pad2)") (class "Default")
      (node (ref "U272") (pin "2") (pinfunction "1_NC_2") (pintype "passive"))
    )
    (net (code "607") (name "unconnected-(U272-2_NC-Pad4)") (class "Default")
      (node (ref "U272") (pin "4") (pinfunction "2_NC_4") (pintype "passive"))
    )
    (net (code "608") (name "unconnected-(U273-1_NC-Pad2)") (class "Default")
      (node (ref "U273") (pin "2") (pinfunction "1_NC_2") (pintype "passive"))
    )
    (net (code "609") (name "unconnected-(U273-2_NC-Pad4)") (class "Default")
      (node (ref "U273") (pin "4") (pinfunction "2_NC_4") (pintype "passive"))
    )
    (net (code "610") (name "unconnected-(U274-1_NC-Pad2)") (class "Default")
      (node (ref "U274") (pin "2") (pinfunction "1_NC_2") (pintype "passive"))
    )
    (net (code "611") (name "unconnected-(U274-2_NC-Pad4)") (class "Default")
      (node (ref "U274") (pin "4") (pinfunction "2_NC_4") (pintype "passive"))
    )
    (net (code "612") (name "unconnected-(U275-1_NC-Pad2)") (class "Default")
      (node (ref "U275") (pin "2") (pinfunction "1_NC_2") (pintype "passive"))
    )
    (net (code "613") (name "unconnected-(U275-2_NC-Pad4)") (class "Default")
      (node (ref "U275") (pin "4") (pinfunction "2_NC_4") (pintype "passive"))
    )
  )
)
